# ENERGIS_Rack-PDU_1_0_1.net
KiCad netlist of a schematic drawn in EAGLE
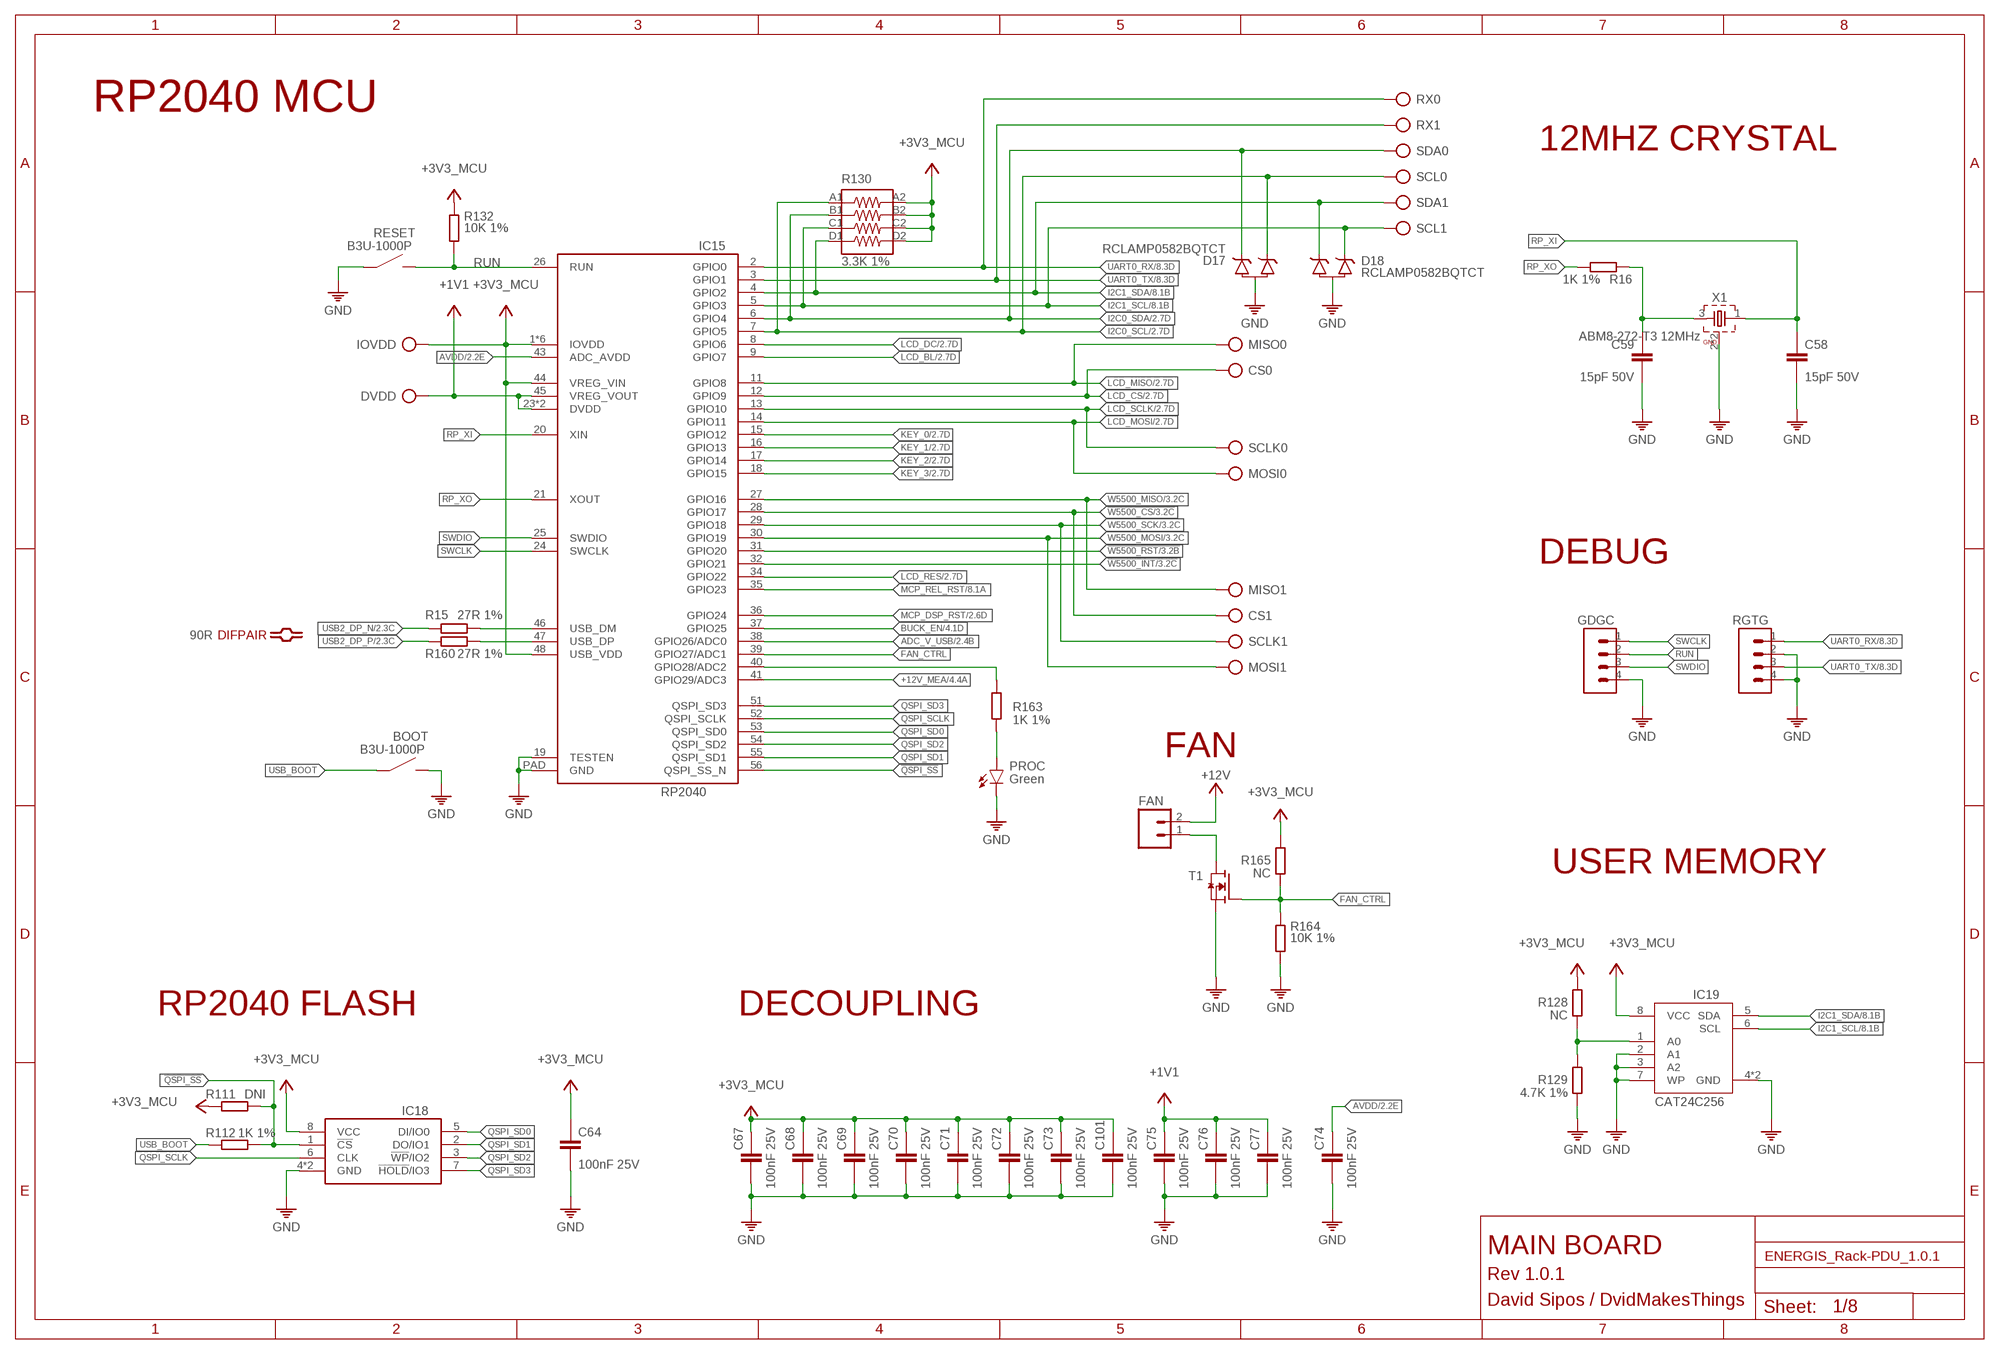
[diagram p0: schematic, sheet 1]
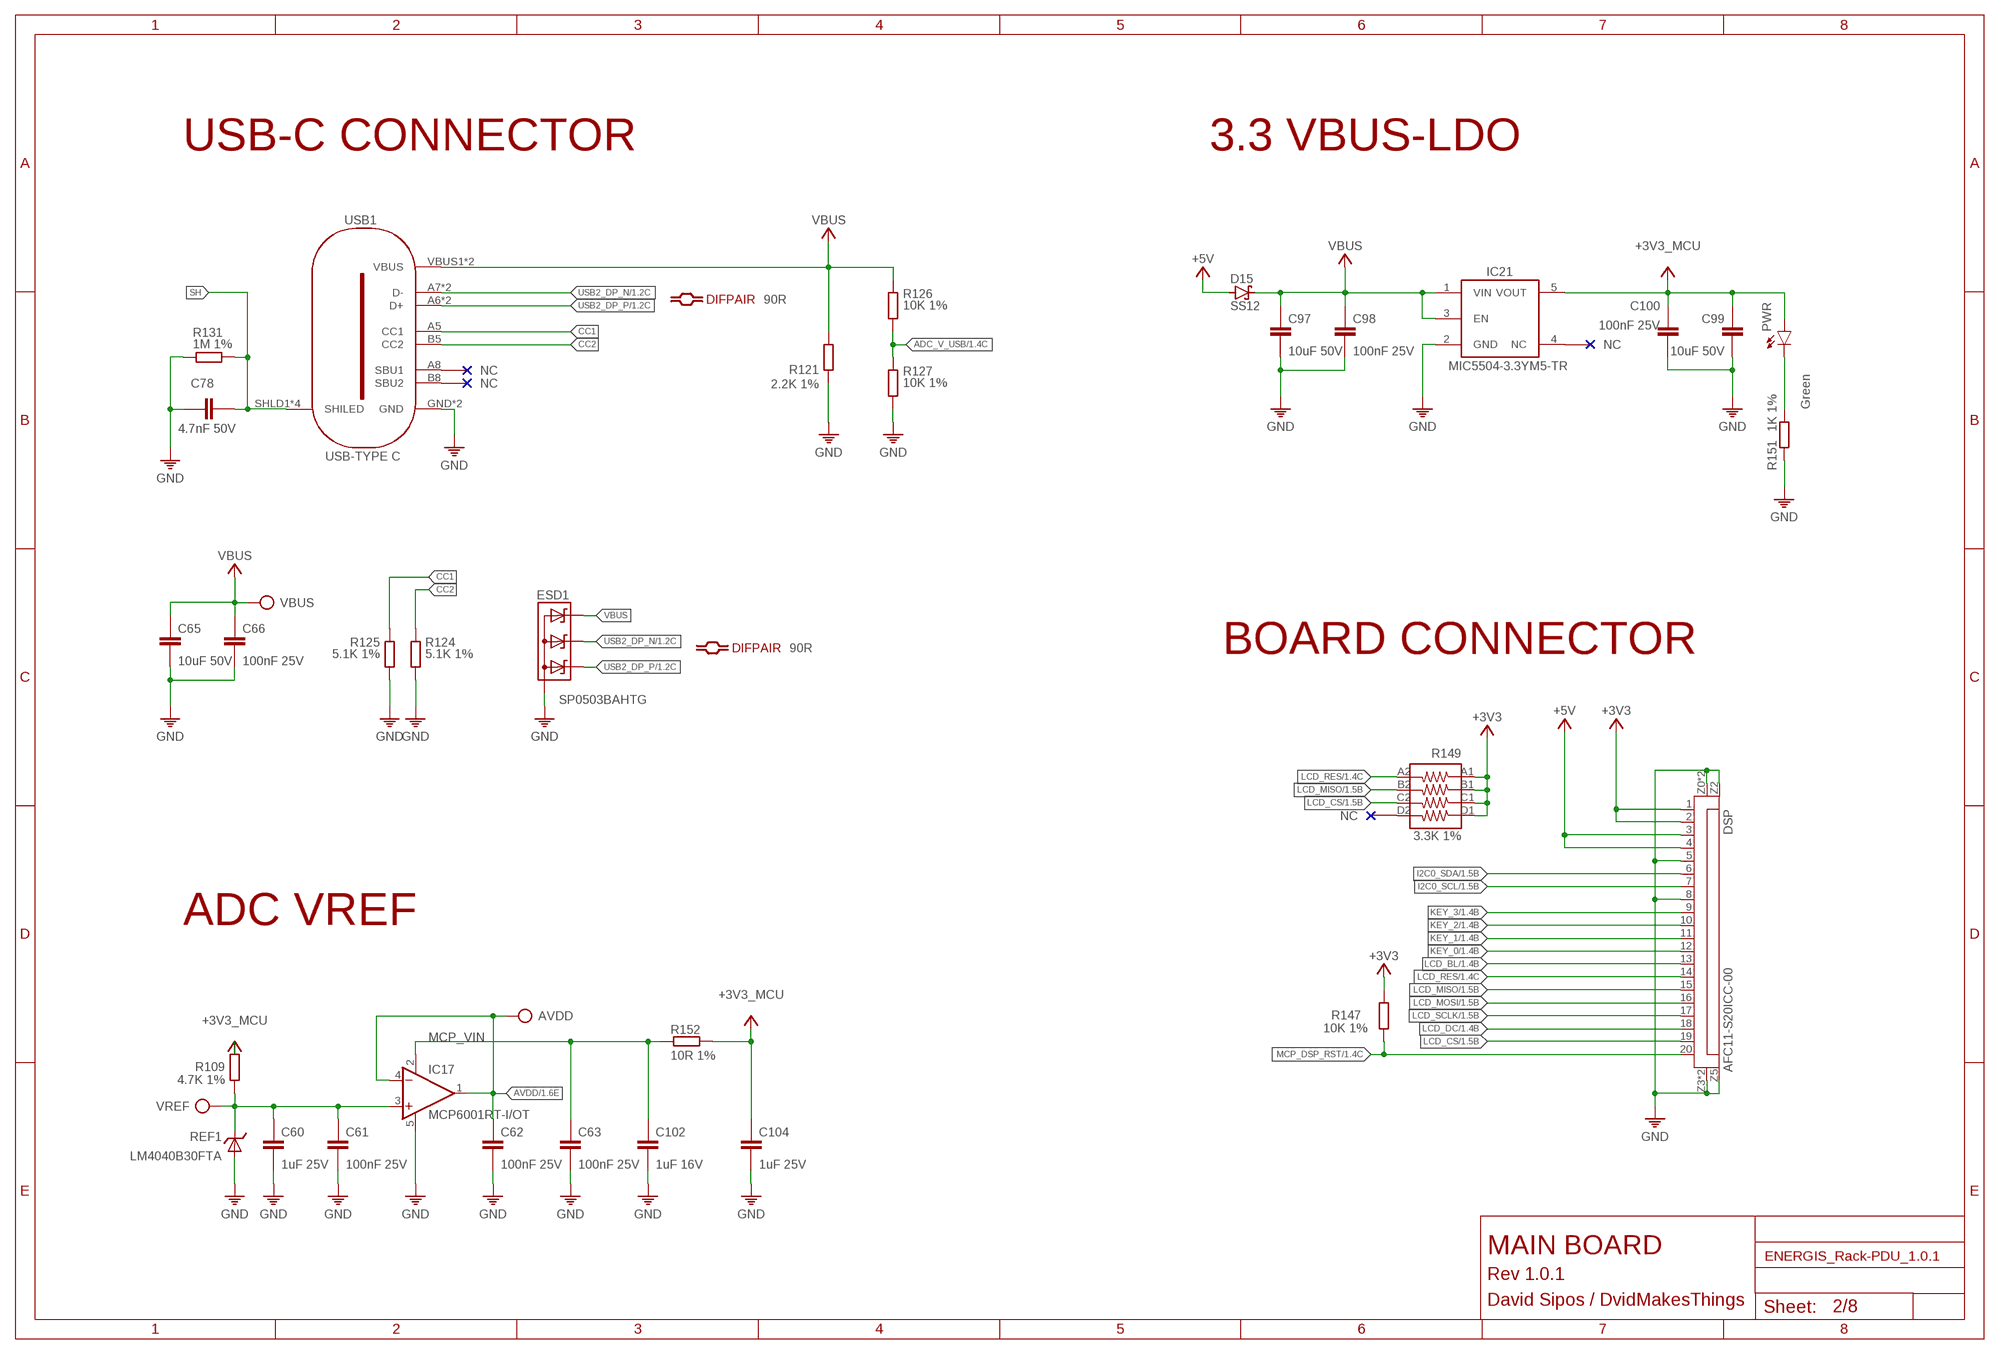
[diagram p1: schematic, sheet 2]
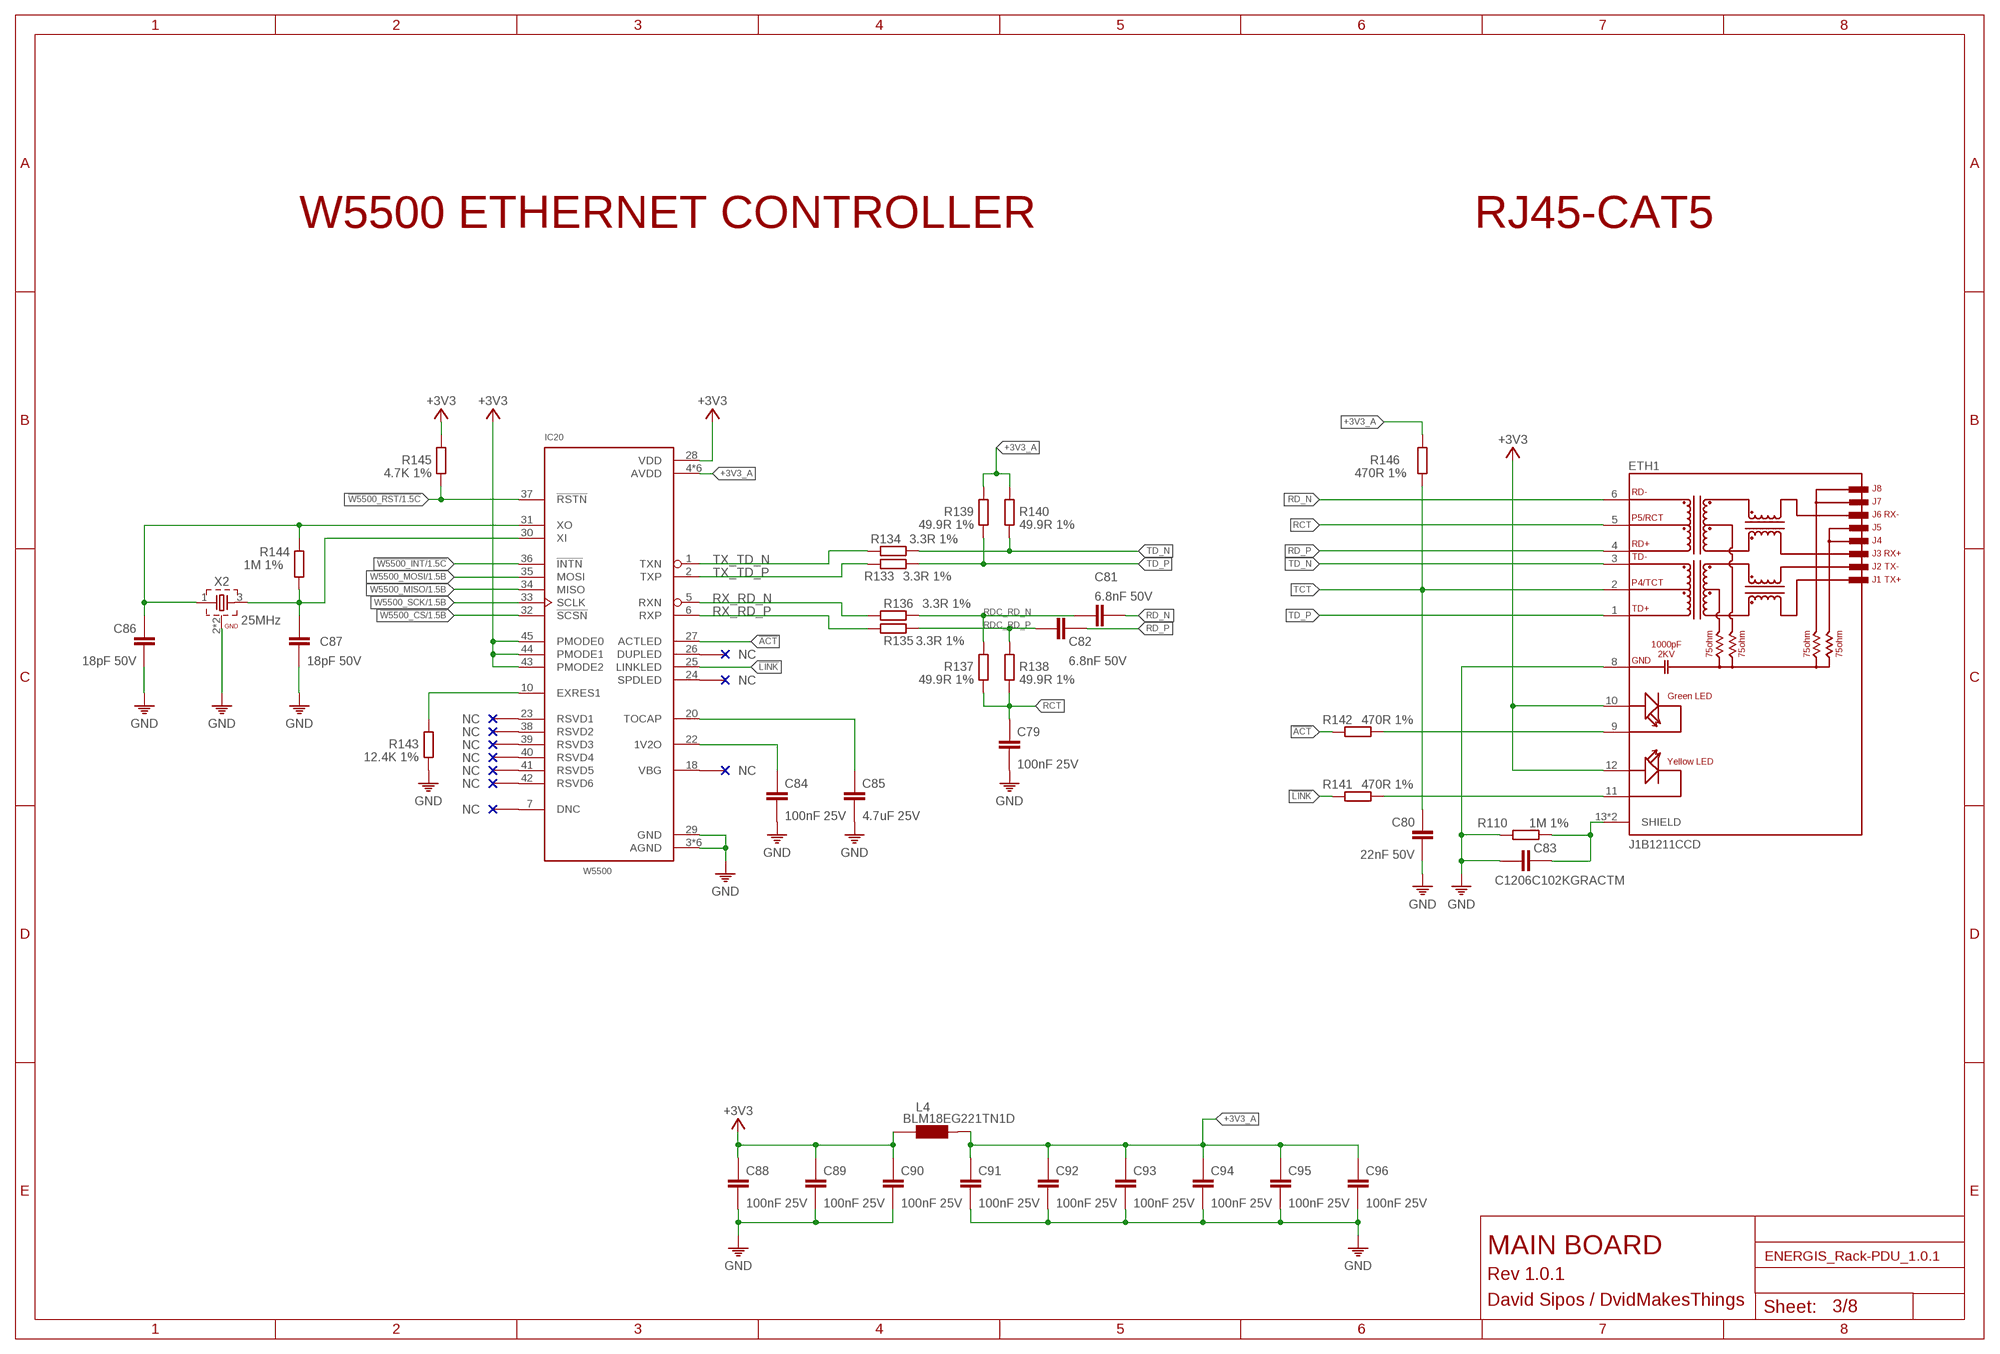
[diagram p2: schematic, sheet 3]
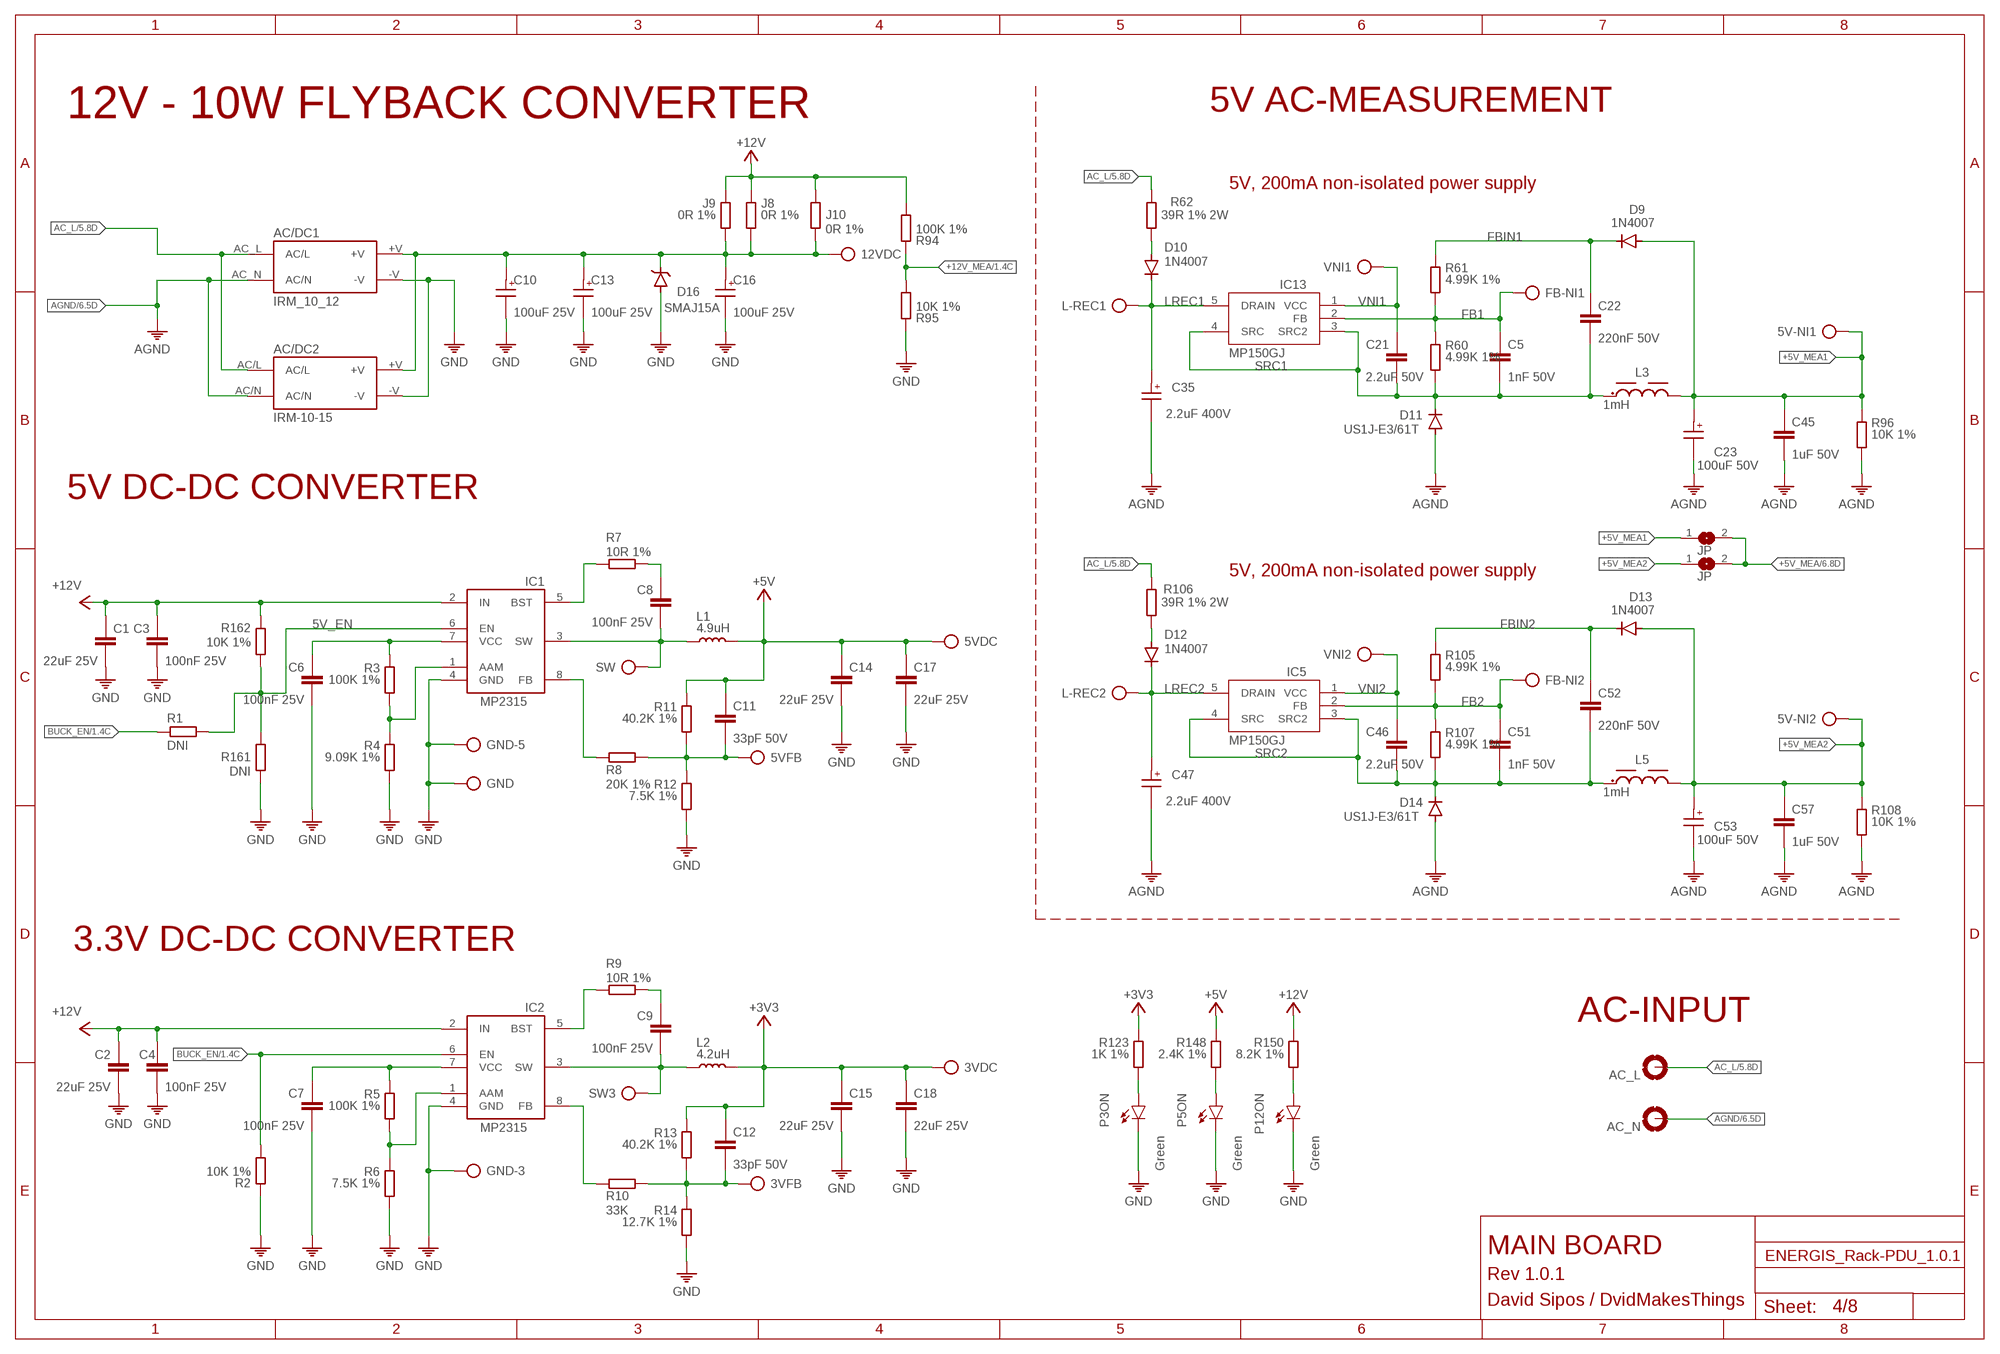
[diagram p3: schematic, sheet 4]
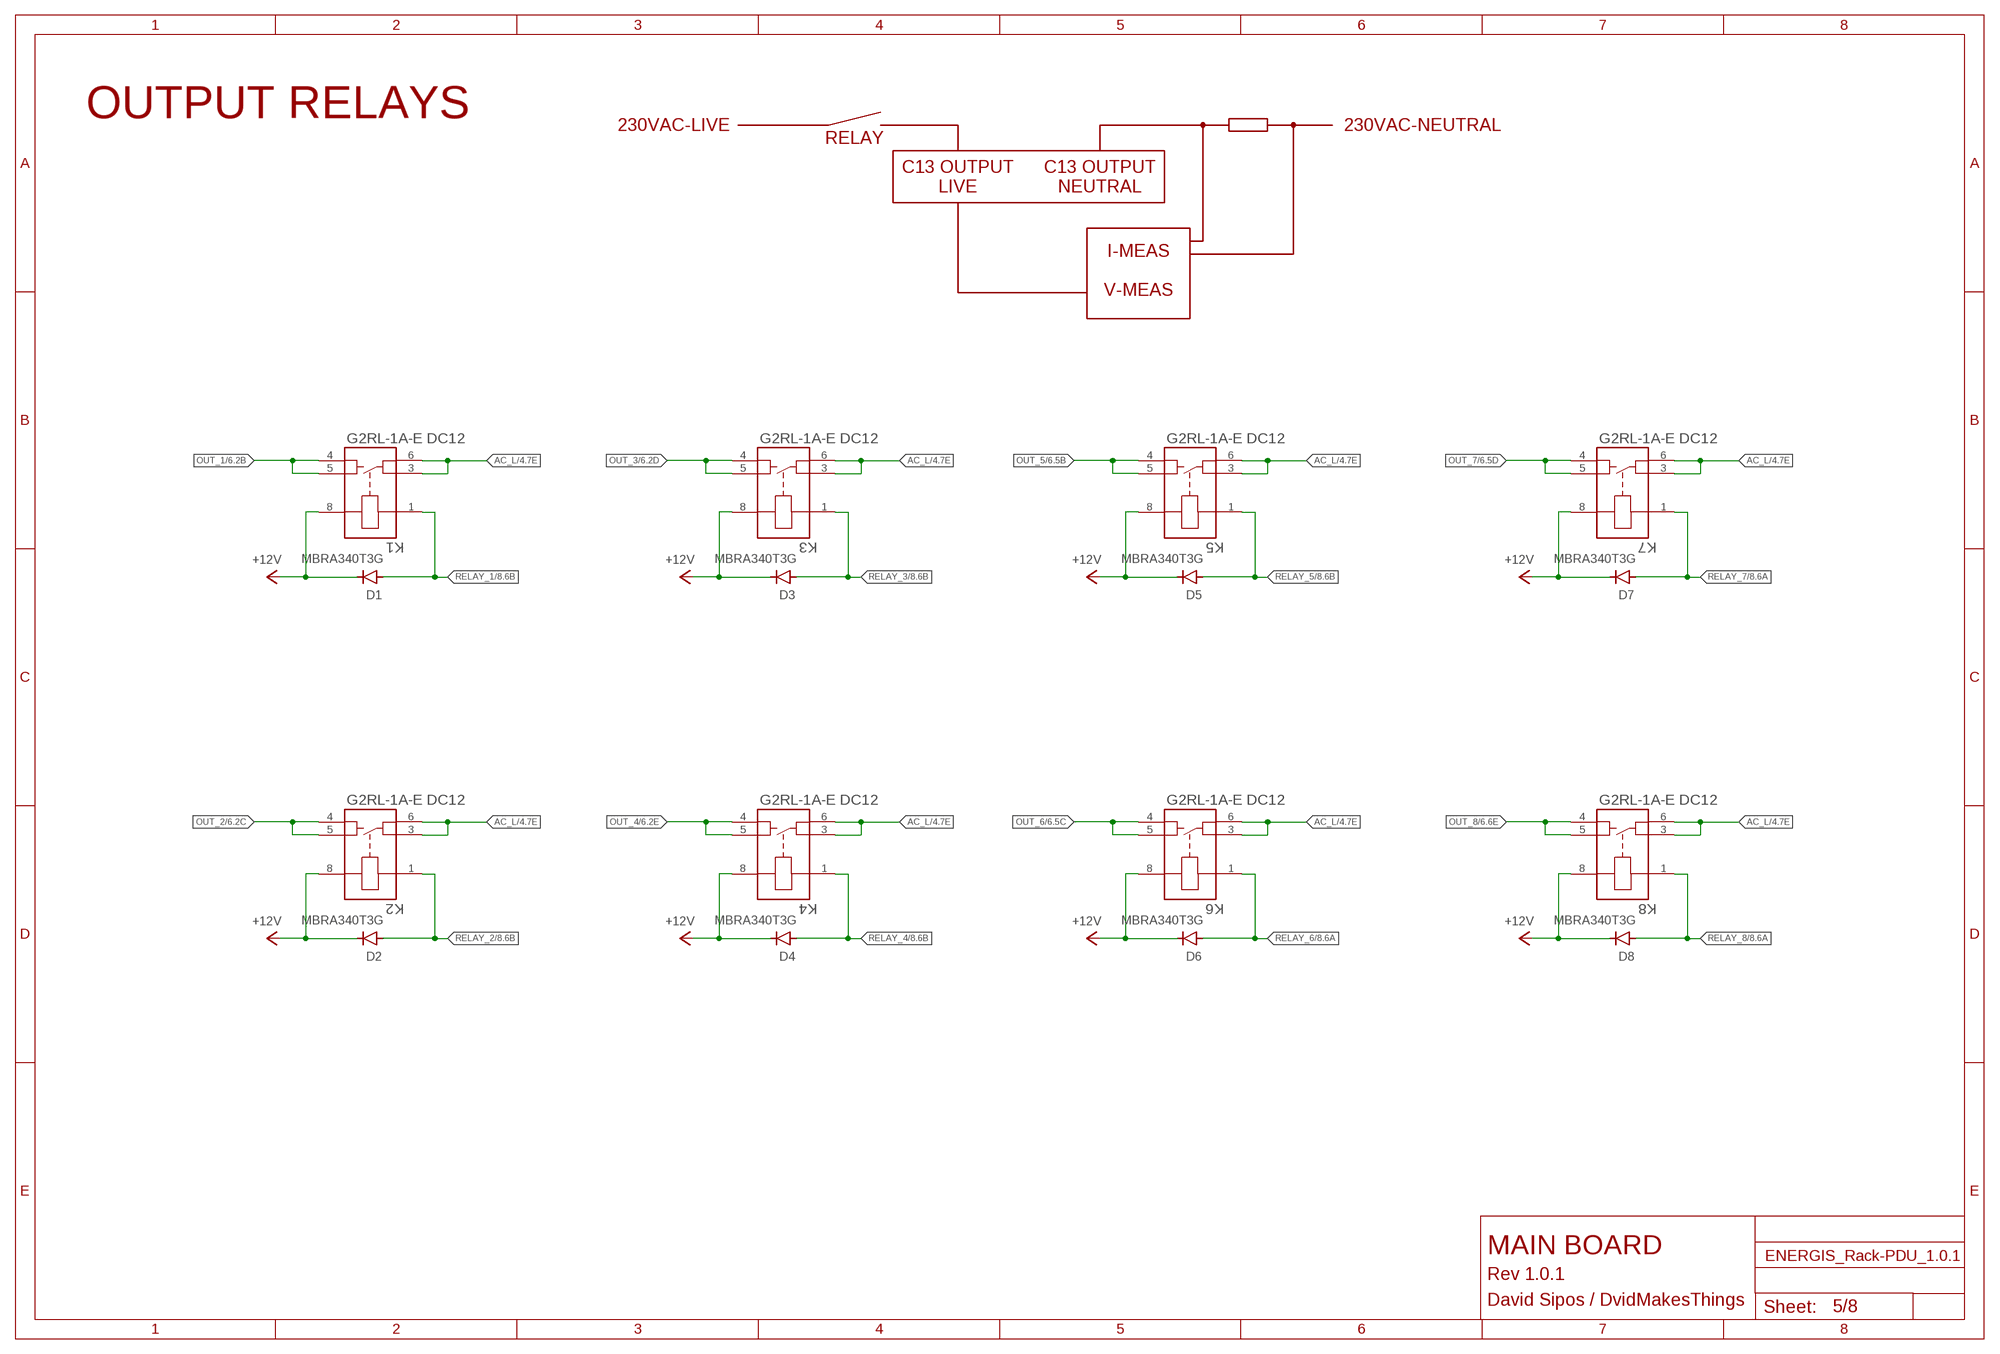
[diagram p4: schematic, sheet 5]
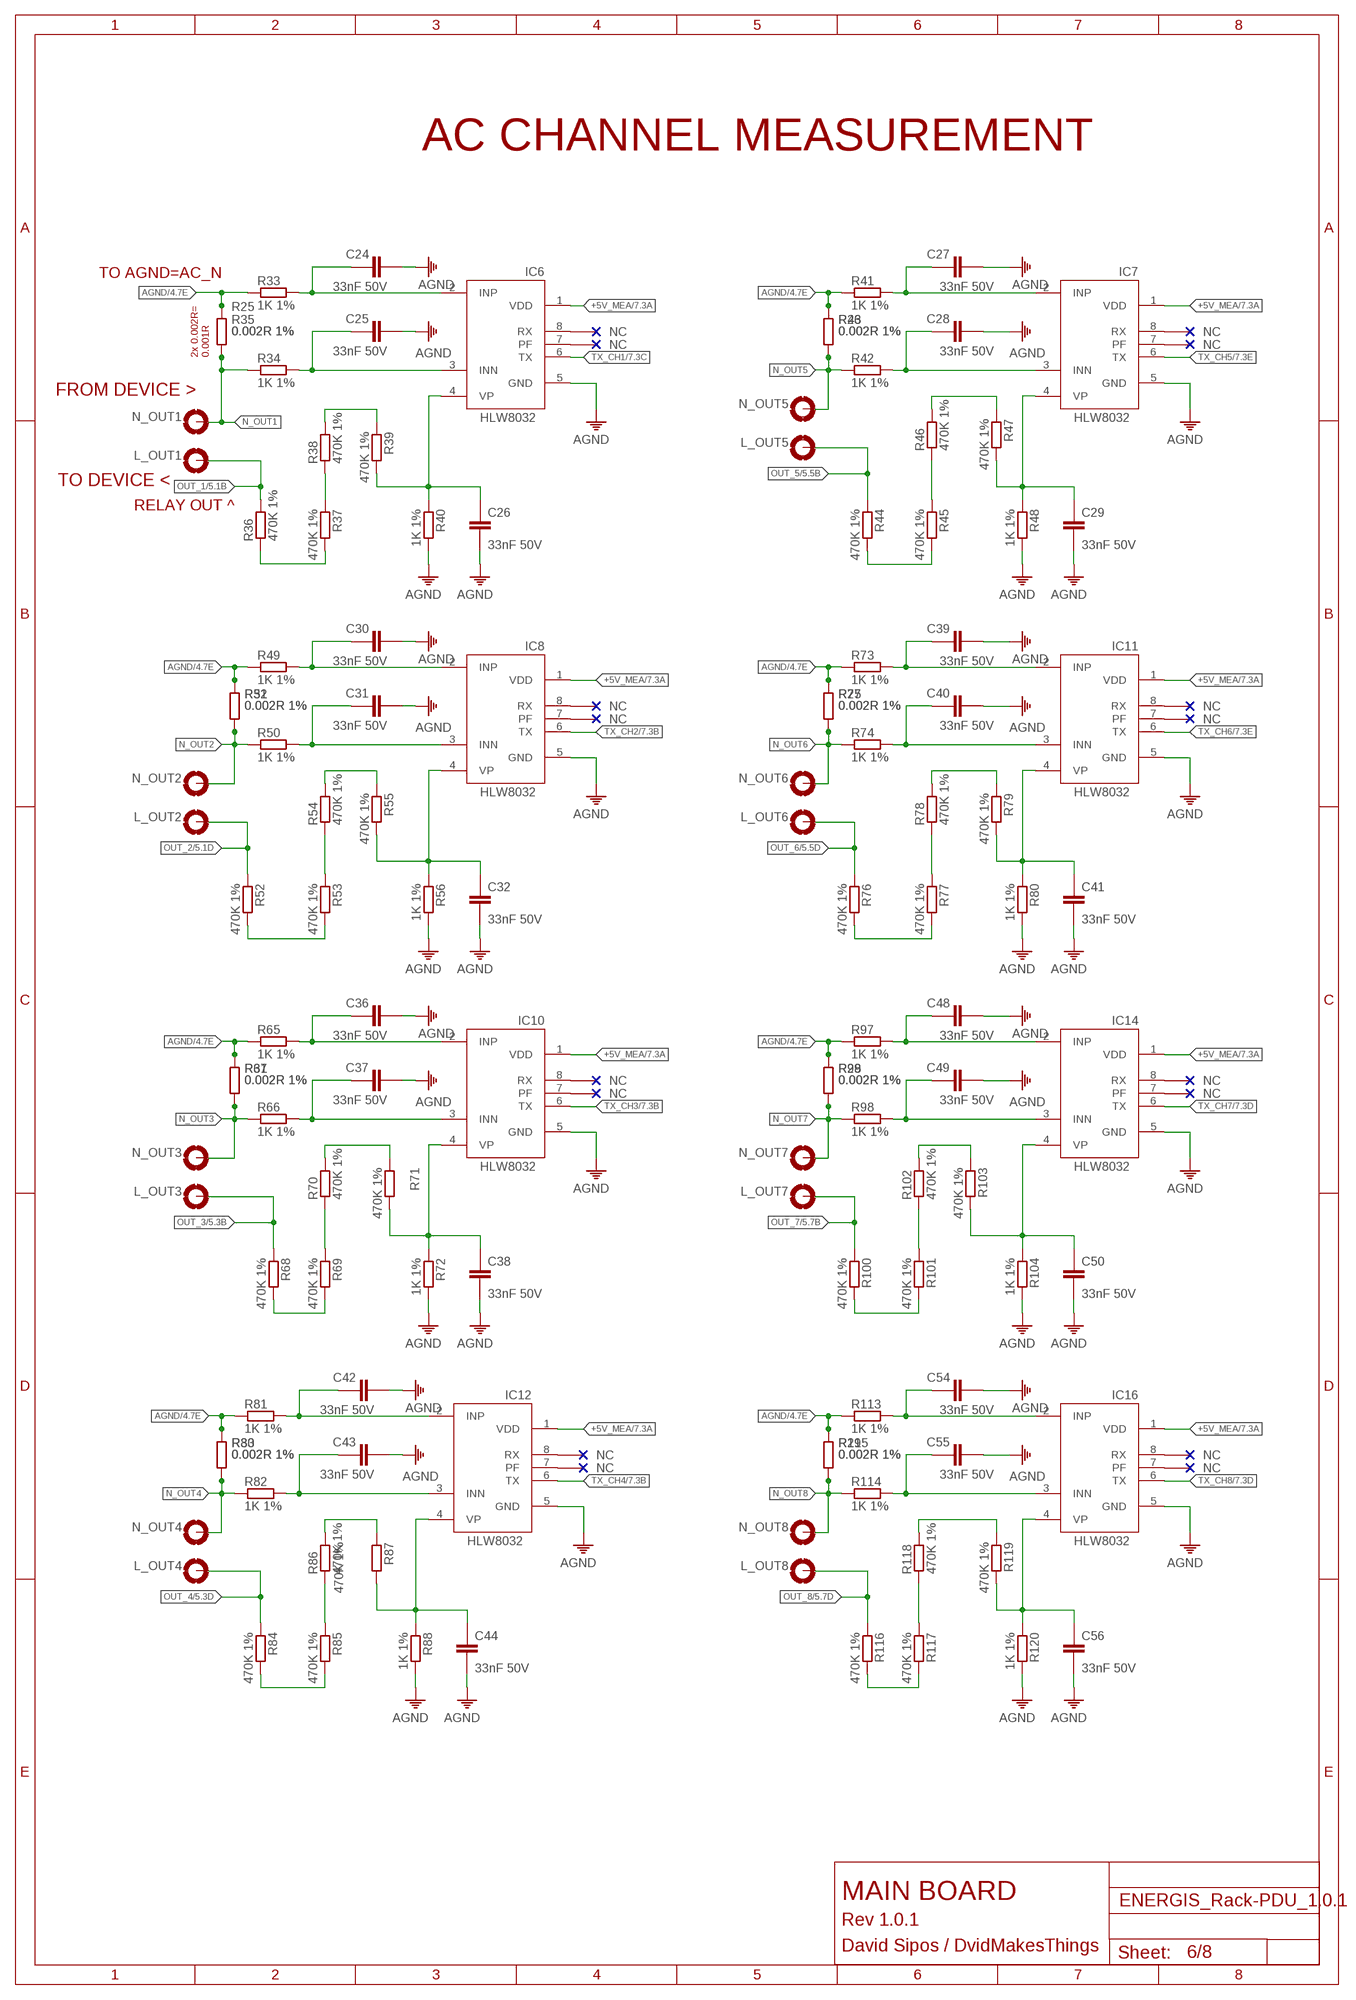
[diagram p5: schematic, sheet 6]
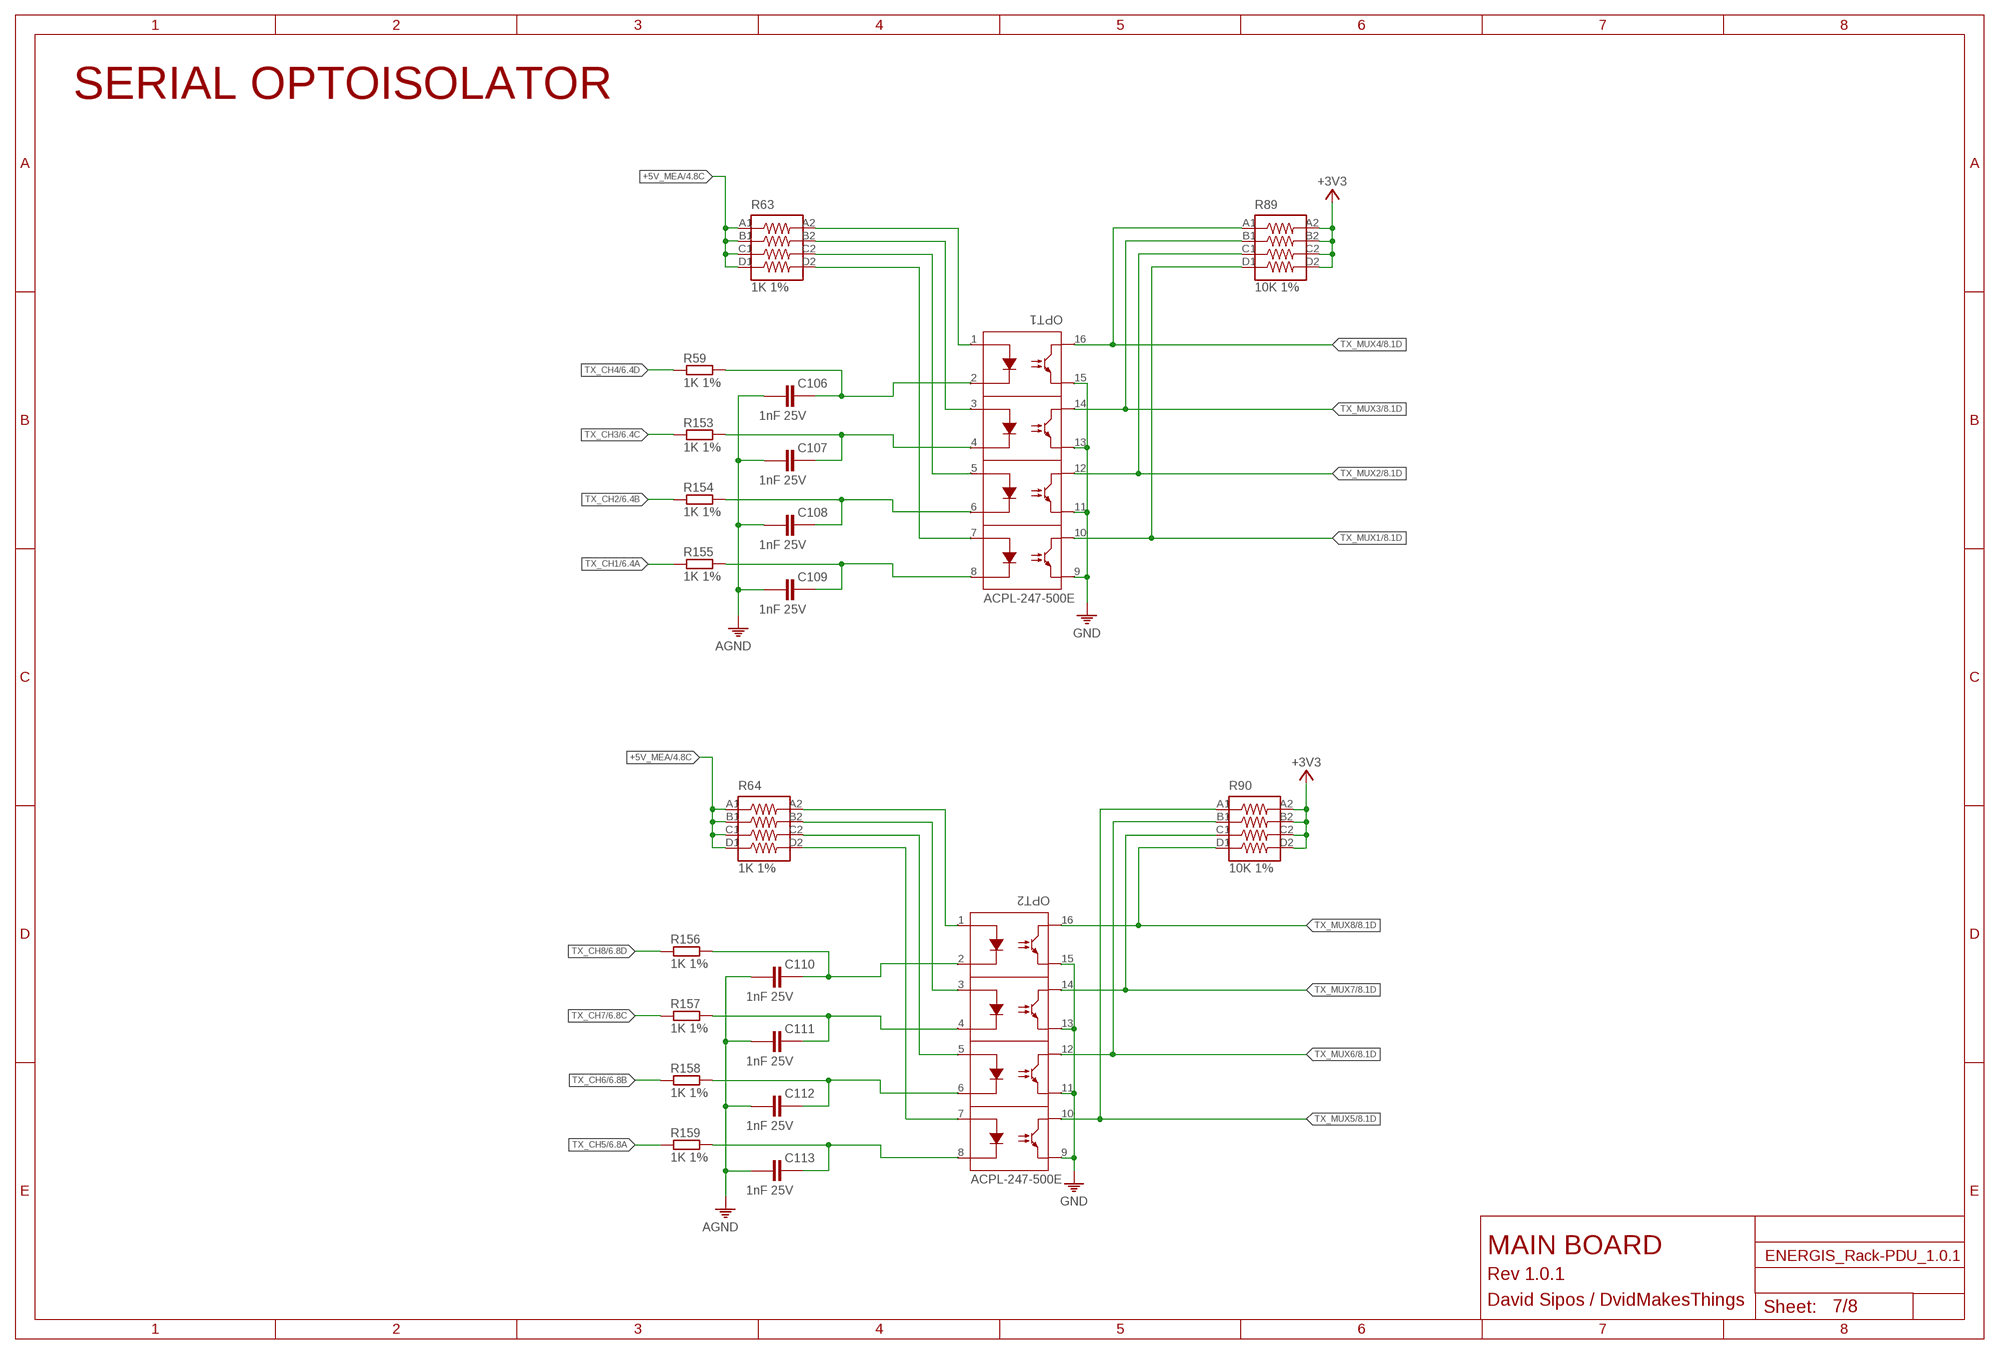
[diagram p6: schematic, sheet 7]
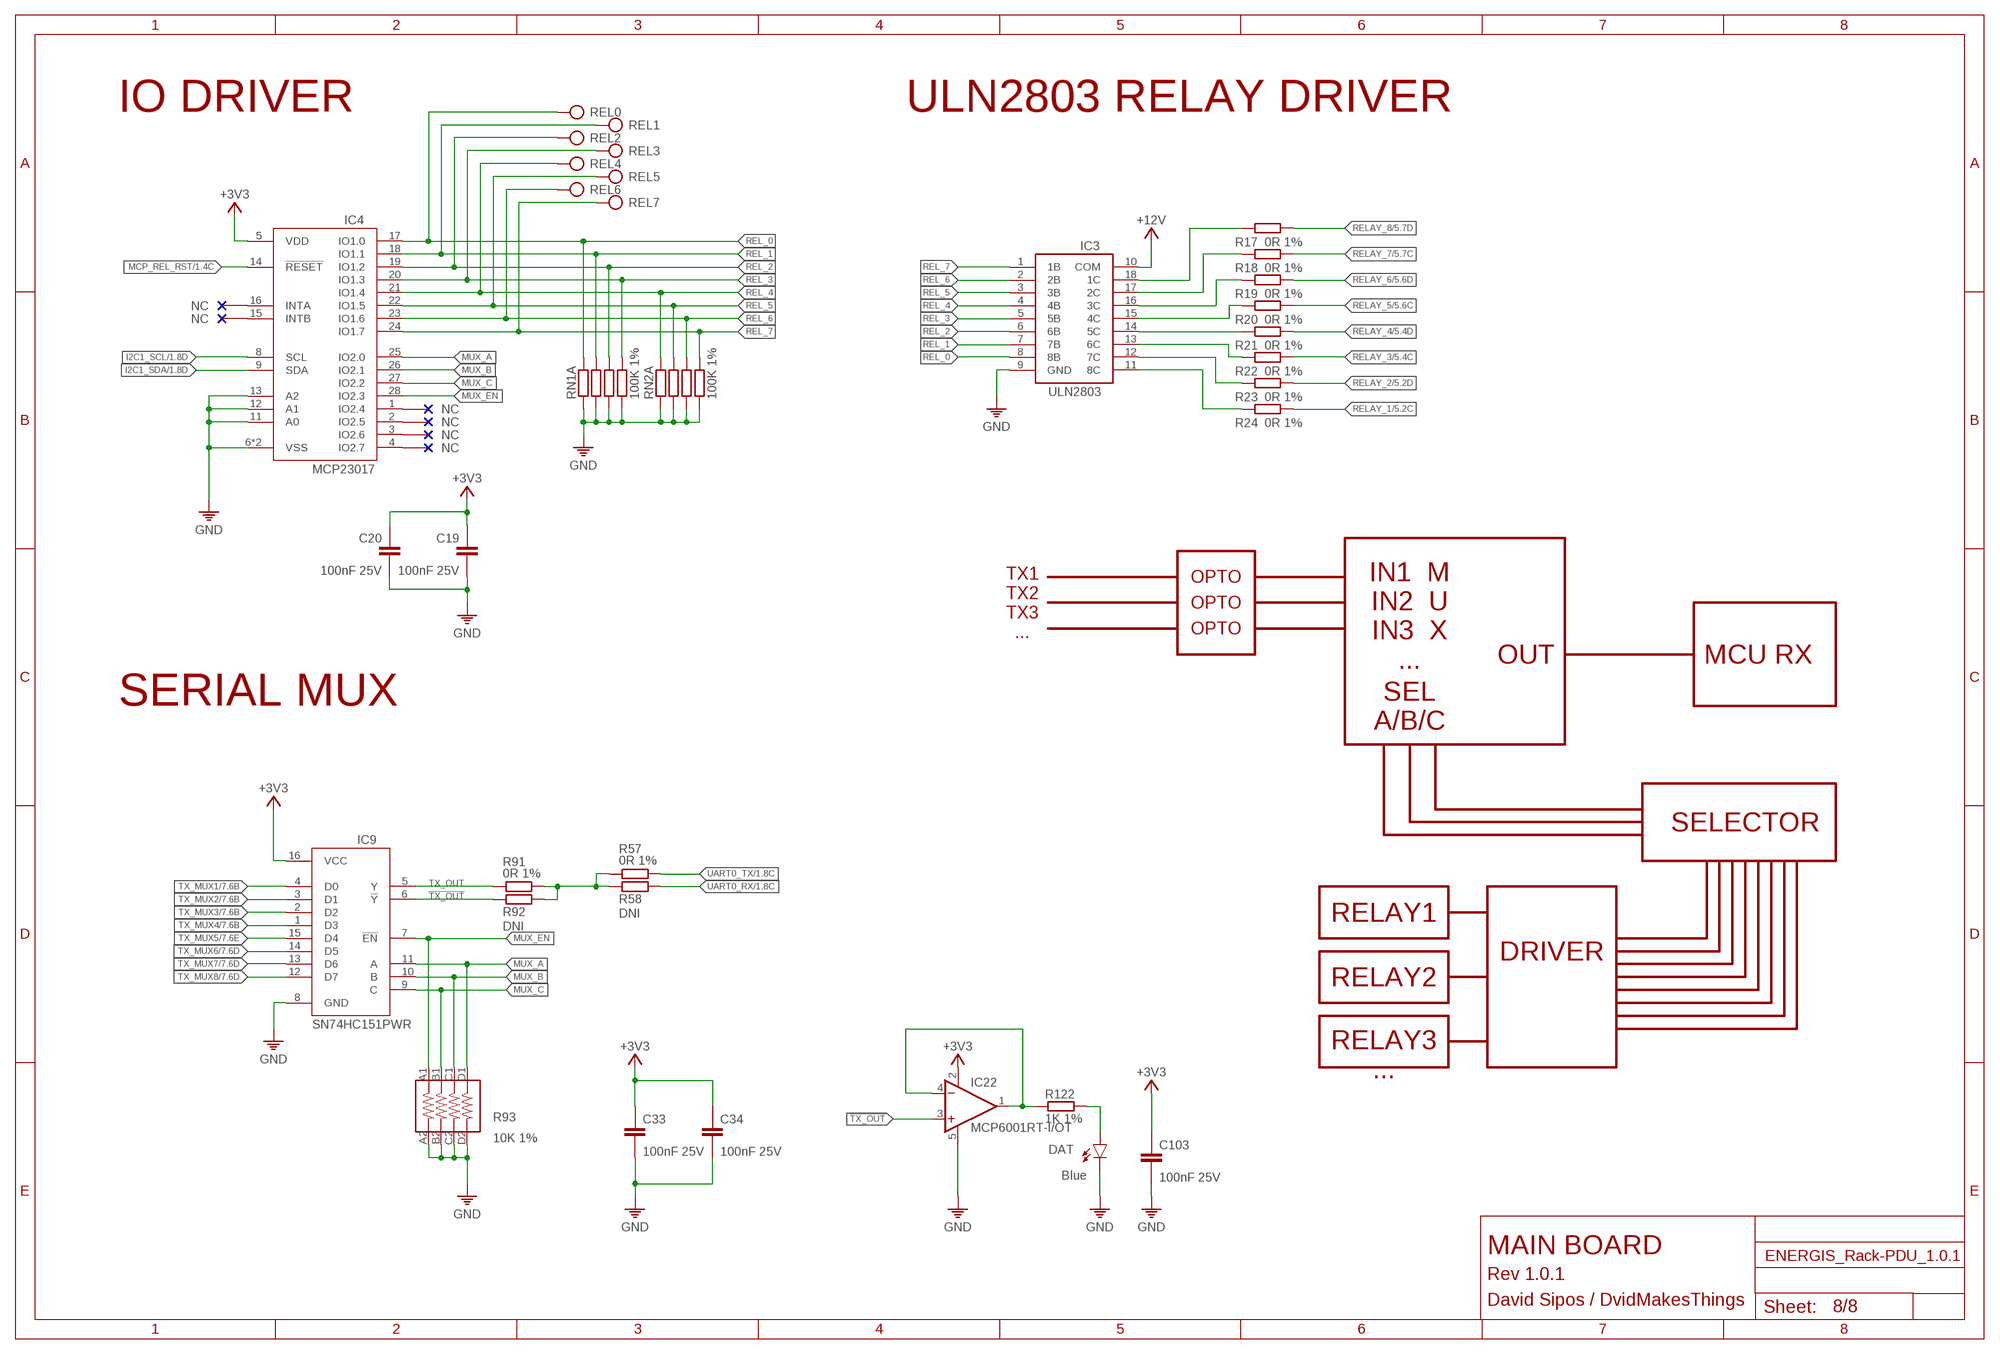
[diagram p7: schematic, sheet 8]

(export (version "E")
  (design (tool "Eeschema 10.0.6"))
  (components
    (comp (ref "BOOT")
      (value "B3U-1000P")
      (footprint "eagle-import:B3U-1000P")
      (fields (field (name "LCSC_PART") "C231329"))
      (libsource (lib "eagle-import") (part "B3U-1000P"))
    )
    (comp (ref "C58")
      (value "15pF 50V")
      (footprint "eagle-import:0201")
      (fields (field (name "LCSC_PART") "C22374851"))
      (libsource (lib "eagle-import") (part "15PF-50V0201"))
    )
    (comp (ref "C59")
      (value "15pF 50V")
      (footprint "eagle-import:0201")
      (fields (field (name "LCSC_PART") "C22374851"))
      (libsource (lib "eagle-import") (part "15PF-50V0201"))
    )
    (comp (ref "C64")
      (value "100nF 25V")
      (footprint "eagle-import:0201")
      (fields (field (name "LCSC_PART") "C76939"))
      (libsource (lib "eagle-import") (part "100NF-25V-0201"))
    )
    (comp (ref "C67")
      (value "100nF 25V")
      (footprint "eagle-import:0201")
      (fields (field (name "LCSC_PART") "C76939"))
      (libsource (lib "eagle-import") (part "100NF-25V-0201"))
    )
    (comp (ref "C68")
      (value "100nF 25V")
      (footprint "eagle-import:0201")
      (fields (field (name "LCSC_PART") "C76939"))
      (libsource (lib "eagle-import") (part "100NF-25V-0201"))
    )
    (comp (ref "C69")
      (value "100nF 25V")
      (footprint "eagle-import:0201")
      (fields (field (name "LCSC_PART") "C76939"))
      (libsource (lib "eagle-import") (part "100NF-25V-0201"))
    )
    (comp (ref "C70")
      (value "100nF 25V")
      (footprint "eagle-import:0201")
      (fields (field (name "LCSC_PART") "C76939"))
      (libsource (lib "eagle-import") (part "100NF-25V-0201"))
    )
    (comp (ref "C71")
      (value "100nF 25V")
      (footprint "eagle-import:0201")
      (fields (field (name "LCSC_PART") "C76939"))
      (libsource (lib "eagle-import") (part "100NF-25V-0201"))
    )
    (comp (ref "C72")
      (value "100nF 25V")
      (footprint "eagle-import:0201")
      (fields (field (name "LCSC_PART") "C76939"))
      (libsource (lib "eagle-import") (part "100NF-25V-0201"))
    )
    (comp (ref "C73")
      (value "100nF 25V")
      (footprint "eagle-import:0201")
      (fields (field (name "LCSC_PART") "C76939"))
      (libsource (lib "eagle-import") (part "100NF-25V-0201"))
    )
    (comp (ref "C74")
      (value "100nF 25V")
      (footprint "eagle-import:0201")
      (fields (field (name "LCSC_PART") "C76939"))
      (libsource (lib "eagle-import") (part "100NF-25V-0201"))
    )
    (comp (ref "C75")
      (value "100nF 25V")
      (footprint "eagle-import:0201")
      (fields (field (name "LCSC_PART") "C76939"))
      (libsource (lib "eagle-import") (part "100NF-25V-0201"))
    )
    (comp (ref "C76")
      (value "100nF 25V")
      (footprint "eagle-import:0201")
      (fields (field (name "LCSC_PART") "C76939"))
      (libsource (lib "eagle-import") (part "100NF-25V-0201"))
    )
    (comp (ref "C77")
      (value "100nF 25V")
      (footprint "eagle-import:0201")
      (fields (field (name "LCSC_PART") "C76939"))
      (libsource (lib "eagle-import") (part "100NF-25V-0201"))
    )
    (comp (ref "C101")
      (value "100nF 25V")
      (footprint "eagle-import:0201")
      (fields (field (name "LCSC_PART") "C76939"))
      (libsource (lib "eagle-import") (part "100NF-25V-0201"))
    )
    (comp (ref "CS0") (value "TP") (footprint "eagle-import:TP") (libsource (lib "eagle-import") (part "TP")))
    (comp (ref "CS1") (value "TP") (footprint "eagle-import:TP") (libsource (lib "eagle-import") (part "TP")))
    (comp (ref "D17")
      (value "RCLAMP0582BQTCT")
      (footprint "eagle-import:SOT-523")
      (fields (field (name "LCSC_PART") "C841193"))
      (libsource (lib "eagle-import") (part "RCLAMP0582BQTCT"))
    )
    (comp (ref "D18")
      (value "RCLAMP0582BQTCT")
      (footprint "eagle-import:SOT-523")
      (fields (field (name "LCSC_PART") "C841193"))
      (libsource (lib "eagle-import") (part "RCLAMP0582BQTCT"))
    )
    (comp (ref "DVDD")
      (value "TP")
      (footprint "eagle-import:TP")
      (libsource (lib "eagle-import") (part "TP"))
    )
    (comp (ref "FAN")
      (value "M02")
      (footprint "eagle-import:02P")
      (libsource (lib "eagle-import") (part "M02"))
    )
    (comp (ref "GDGC")
      (value "CON-1X4")
      (footprint "eagle-import:1X4")
      (libsource (lib "eagle-import") (part "CON-1X4"))
    )
    (comp (ref "IC15")
      (value "RP2040")
      (footprint "eagle-import:QFN56")
      (fields (field (name "LCSC_PART") "C2040"))
      (libsource (lib "eagle-import") (part "RP2040"))
    )
    (comp (ref "IC18")
      (value "W25Q128JVPIQ")
      (footprint "eagle-import:SON127P600X500X75-8N")
      (fields (field (name "LCSC_PART") "C190862"))
      (libsource (lib "eagle-import") (part "W25Q128JVP"))
    )
    (comp (ref "IC19")
      (value "CAT24C256HU4IGT3")
      (footprint "eagle-import:SON50P300X200X50-9T130X140N")
      (fields (field (name "LCSC_PART") "C233771"))
      (libsource (lib "eagle-import") (part "CAT24C256-HU4"))
    )
    (comp (ref "IOVDD")
      (value "TP")
      (footprint "eagle-import:TP")
      (libsource (lib "eagle-import") (part "TP"))
    )
    (comp (ref "MISO0")
      (value "TP")
      (footprint "eagle-import:TP")
      (libsource (lib "eagle-import") (part "TP"))
    )
    (comp (ref "MISO1")
      (value "TP")
      (footprint "eagle-import:TP")
      (libsource (lib "eagle-import") (part "TP"))
    )
    (comp (ref "MOSI0")
      (value "TP")
      (footprint "eagle-import:TP")
      (libsource (lib "eagle-import") (part "TP"))
    )
    (comp (ref "MOSI1")
      (value "TP")
      (footprint "eagle-import:TP")
      (libsource (lib "eagle-import") (part "TP"))
    )
    (comp (ref "PROC")
      (value "Green")
      (footprint "eagle-import:LED-0603")
      (fields (field (name "LCSC_PART") "C965804"))
      (libsource (lib "eagle-import") (part "LED-GREENLED-0603"))
    )
    (comp (ref "R15")
      (value "27R 1%")
      (footprint "eagle-import:0201")
      (fields (field (name "LCSC_PART") "C473051"))
      (libsource (lib "eagle-import") (part "27R-1%0201"))
    )
    (comp (ref "R16")
      (value "1K 1%")
      (footprint "eagle-import:0201")
      (fields (field (name "LCSC_PART") "C270365"))
      (libsource (lib "eagle-import") (part "1K-1%0201"))
    )
    (comp (ref "R111")
      (value "DNI")
      (footprint "eagle-import:R0201")
      (libsource (lib "eagle-import") (part "R0201"))
    )
    (comp (ref "R112")
      (value "1K 1%")
      (footprint "eagle-import:0402")
      (fields (field (name "LCSC_PART") "C11702"))
      (libsource (lib "eagle-import") (part "1K-1%0402"))
    )
    (comp (ref "R128")
      (value "NC")
      (footprint "eagle-import:R0201")
      (libsource (lib "eagle-import") (part "R0201"))
    )
    (comp (ref "R129")
      (value "4.7K 1%")
      (footprint "eagle-import:0201")
      (fields (field (name "LCSC_PART") "C270346"))
      (libsource (lib "eagle-import") (part "4.7K-1%0201"))
    )
    (comp (ref "R130")
      (value "3.3K 1%")
      (footprint "eagle-import:_0603X4-1206")
      (fields (field (name "LCSC_PART") "C1734380"))
      (libsource (lib "eagle-import") (part "3.3K-1%_ARRAY0603X4-1206"))
    )
    (comp (ref "R132")
      (value "10K 1%")
      (footprint "eagle-import:0402")
      (fields (field (name "LCSC_PART") "C25744"))
      (libsource (lib "eagle-import") (part "10K-1%0402"))
    )
    (comp (ref "R160")
      (value "27R 1%")
      (footprint "eagle-import:0201")
      (fields (field (name "LCSC_PART") "C473051"))
      (libsource (lib "eagle-import") (part "27R-1%0201"))
    )
    (comp (ref "R163")
      (value "1K 1%")
      (footprint "eagle-import:0402")
      (fields (field (name "LCSC_PART") "C11702"))
      (libsource (lib "eagle-import") (part "1K-1%0402"))
    )
    (comp (ref "R164")
      (value "10K 1%")
      (footprint "eagle-import:0402")
      (fields (field (name "LCSC_PART") "C25744"))
      (libsource (lib "eagle-import") (part "10K-1%0402"))
    )
    (comp (ref "R165")
      (value "NC")
      (footprint "eagle-import:R0201")
      (libsource (lib "eagle-import") (part "R0201"))
    )
    (comp (ref "RESET")
      (value "B3U-1000P")
      (footprint "eagle-import:B3U-1000P")
      (fields (field (name "LCSC_PART") "C231329"))
      (libsource (lib "eagle-import") (part "B3U-1000P"))
    )
    (comp (ref "RGTG")
      (value "CON-1X4")
      (footprint "eagle-import:1X4")
      (libsource (lib "eagle-import") (part "CON-1X4"))
    )
    (comp (ref "RX0") (value "TP") (footprint "eagle-import:TP") (libsource (lib "eagle-import") (part "TP")))
    (comp (ref "RX1") (value "TP") (footprint "eagle-import:TP") (libsource (lib "eagle-import") (part "TP")))
    (comp (ref "SCL0")
      (value "TP")
      (footprint "eagle-import:TP")
      (libsource (lib "eagle-import") (part "TP"))
    )
    (comp (ref "SCL1")
      (value "TP")
      (footprint "eagle-import:TP")
      (libsource (lib "eagle-import") (part "TP"))
    )
    (comp (ref "SCLK0")
      (value "TP")
      (footprint "eagle-import:TP")
      (libsource (lib "eagle-import") (part "TP"))
    )
    (comp (ref "SCLK1")
      (value "TP")
      (footprint "eagle-import:TP")
      (libsource (lib "eagle-import") (part "TP"))
    )
    (comp (ref "SDA0")
      (value "TP")
      (footprint "eagle-import:TP")
      (libsource (lib "eagle-import") (part "TP"))
    )
    (comp (ref "SDA1")
      (value "TP")
      (footprint "eagle-import:TP")
      (libsource (lib "eagle-import") (part "TP"))
    )
    (comp (ref "T1")
      (value "BSS138")
      (footprint "eagle-import:SOT23")
      (libsource (lib "eagle-import") (part "BSS138"))
    )
    (comp (ref "X1")
      (value "ABM8-272-T3 12MHz")
      (footprint "eagle-import:WE-XTAL_CFPX-180")
      (fields (field (name "LCSC_PART") "C20625731"))
      (libsource (lib "eagle-import") (part "CRYSTAL-3225X322512MSB4SI"))
    )
    (comp (ref "C106")
      (value "1nF 25V")
      (footprint "eagle-import:0201")
      (fields (field (name "LCSC_PART") "C7694325V"))
      (libsource (lib "eagle-import") (part "1NF-25V-0201"))
    )
    (comp (ref "C107")
      (value "1nF 25V")
      (footprint "eagle-import:0201")
      (fields (field (name "LCSC_PART") "C7694325V"))
      (libsource (lib "eagle-import") (part "1NF-25V-0201"))
    )
    (comp (ref "C108")
      (value "1nF 25V")
      (footprint "eagle-import:0201")
      (fields (field (name "LCSC_PART") "C7694325V"))
      (libsource (lib "eagle-import") (part "1NF-25V-0201"))
    )
    (comp (ref "C109")
      (value "1nF 25V")
      (footprint "eagle-import:0201")
      (fields (field (name "LCSC_PART") "C7694325V"))
      (libsource (lib "eagle-import") (part "1NF-25V-0201"))
    )
    (comp (ref "C110")
      (value "1nF 25V")
      (footprint "eagle-import:0201")
      (fields (field (name "LCSC_PART") "C7694325V"))
      (libsource (lib "eagle-import") (part "1NF-25V-0201"))
    )
    (comp (ref "C111")
      (value "1nF 25V")
      (footprint "eagle-import:0201")
      (fields (field (name "LCSC_PART") "C7694325V"))
      (libsource (lib "eagle-import") (part "1NF-25V-0201"))
    )
    (comp (ref "C112")
      (value "1nF 25V")
      (footprint "eagle-import:0201")
      (fields (field (name "LCSC_PART") "C7694325V"))
      (libsource (lib "eagle-import") (part "1NF-25V-0201"))
    )
    (comp (ref "C113")
      (value "1nF 25V")
      (footprint "eagle-import:0201")
      (fields (field (name "LCSC_PART") "C7694325V"))
      (libsource (lib "eagle-import") (part "1NF-25V-0201"))
    )
    (comp (ref "OPT1")
      (value "ACPL-247-500E")
      (footprint "eagle-import:SO16")
      (fields (field (name "LCSC_PART") "C188681"))
      (libsource (lib "eagle-import") (part "ACPL-2471"))
    )
    (comp (ref "OPT2")
      (value "ACPL-247-500E")
      (footprint "eagle-import:SO16")
      (fields (field (name "LCSC_PART") "C188681"))
      (libsource (lib "eagle-import") (part "ACPL-2471"))
    )
    (comp (ref "R59")
      (value "1K 1%")
      (footprint "eagle-import:0201")
      (fields (field (name "LCSC_PART") "C270365"))
      (libsource (lib "eagle-import") (part "1K-1%0201"))
    )
    (comp (ref "R63")
      (value "1K 1%")
      (footprint "eagle-import:_0603X4-1206")
      (fields (field (name "LCSC_PART") "C110021"))
      (libsource (lib "eagle-import") (part "1K-1%_ARRAY0603X4-1206"))
    )
    (comp (ref "R64")
      (value "1K 1%")
      (footprint "eagle-import:_0603X4-1206")
      (fields (field (name "LCSC_PART") "C110021"))
      (libsource (lib "eagle-import") (part "1K-1%_ARRAY0603X4-1206"))
    )
    (comp (ref "R89")
      (value "10K 1%")
      (footprint "eagle-import:_0603X4-1206")
      (fields (field (name "LCSC_PART") "C110924"))
      (libsource (lib "eagle-import") (part "10K-1%_ARRAY0603X4-1206"))
    )
    (comp (ref "R90")
      (value "10K 1%")
      (footprint "eagle-import:_0603X4-1206")
      (fields (field (name "LCSC_PART") "C110924"))
      (libsource (lib "eagle-import") (part "10K-1%_ARRAY0603X4-1206"))
    )
    (comp (ref "R153")
      (value "1K 1%")
      (footprint "eagle-import:0201")
      (fields (field (name "LCSC_PART") "C270365"))
      (libsource (lib "eagle-import") (part "1K-1%0201"))
    )
    (comp (ref "R154")
      (value "1K 1%")
      (footprint "eagle-import:0201")
      (fields (field (name "LCSC_PART") "C270365"))
      (libsource (lib "eagle-import") (part "1K-1%0201"))
    )
    (comp (ref "R155")
      (value "1K 1%")
      (footprint "eagle-import:0201")
      (fields (field (name "LCSC_PART") "C270365"))
      (libsource (lib "eagle-import") (part "1K-1%0201"))
    )
    (comp (ref "R156")
      (value "1K 1%")
      (footprint "eagle-import:0201")
      (fields (field (name "LCSC_PART") "C270365"))
      (libsource (lib "eagle-import") (part "1K-1%0201"))
    )
    (comp (ref "R157")
      (value "1K 1%")
      (footprint "eagle-import:0201")
      (fields (field (name "LCSC_PART") "C270365"))
      (libsource (lib "eagle-import") (part "1K-1%0201"))
    )
    (comp (ref "R158")
      (value "1K 1%")
      (footprint "eagle-import:0201")
      (fields (field (name "LCSC_PART") "C270365"))
      (libsource (lib "eagle-import") (part "1K-1%0201"))
    )
    (comp (ref "R159")
      (value "1K 1%")
      (footprint "eagle-import:0201")
      (fields (field (name "LCSC_PART") "C270365"))
      (libsource (lib "eagle-import") (part "1K-1%0201"))
    )
    (comp (ref "C79")
      (value "100nF 25V")
      (footprint "eagle-import:0402")
      (fields (field (name "LCSC_PART") "C56392"))
      (libsource (lib "eagle-import") (part "100NF-25V-0402"))
    )
    (comp (ref "C80")
      (value "22nF 50V")
      (footprint "eagle-import:0402")
      (fields (field (name "LCSC_PART") "C1532"))
      (libsource (lib "eagle-import") (part "22NF-50V0402"))
    )
    (comp (ref "C81")
      (value "6.8nF 50V")
      (footprint "eagle-import:0201")
      (fields (field (name "LCSC_PART") "C285015"))
      (libsource (lib "eagle-import") (part "6.8NF-50V0201"))
    )
    (comp (ref "C82")
      (value "6.8nF 50V")
      (footprint "eagle-import:0201")
      (fields (field (name "LCSC_PART") "C285015"))
      (libsource (lib "eagle-import") (part "6.8NF-50V0201"))
    )
    (comp (ref "C83")
      (value "C1206C102KGRACTM")
      (footprint "eagle-import:C1206")
      (libsource (lib "eagle-import") (part "C-1206"))
    )
    (comp (ref "C84")
      (value "100nF 25V")
      (footprint "eagle-import:0201")
      (fields (field (name "LCSC_PART") "C76939"))
      (libsource (lib "eagle-import") (part "100NF-25V-0201"))
    )
    (comp (ref "C85")
      (value "4.7uF 25V")
      (footprint "eagle-import:0402")
      (fields (field (name "LCSC_PART") "C22367824"))
      (libsource (lib "eagle-import") (part "4.7UF-25V0402"))
    )
    (comp (ref "C86")
      (value "18pF 50V")
      (footprint "eagle-import:0201")
      (fields (field (name "LCSC_PART") "C62164"))
      (libsource (lib "eagle-import") (part "18PF-50V-0201"))
    )
    (comp (ref "C87")
      (value "18pF 50V")
      (footprint "eagle-import:0201")
      (fields (field (name "LCSC_PART") "C62164"))
      (libsource (lib "eagle-import") (part "18PF-50V-0201"))
    )
    (comp (ref "C88")
      (value "100nF 25V")
      (footprint "eagle-import:0201")
      (fields (field (name "LCSC_PART") "C76939"))
      (libsource (lib "eagle-import") (part "100NF-25V-0201"))
    )
    (comp (ref "C89")
      (value "100nF 25V")
      (footprint "eagle-import:0201")
      (fields (field (name "LCSC_PART") "C76939"))
      (libsource (lib "eagle-import") (part "100NF-25V-0201"))
    )
    (comp (ref "C90")
      (value "100nF 25V")
      (footprint "eagle-import:0201")
      (fields (field (name "LCSC_PART") "C76939"))
      (libsource (lib "eagle-import") (part "100NF-25V-0201"))
    )
    (comp (ref "C91")
      (value "100nF 25V")
      (footprint "eagle-import:0201")
      (fields (field (name "LCSC_PART") "C76939"))
      (libsource (lib "eagle-import") (part "100NF-25V-0201"))
    )
    (comp (ref "C92")
      (value "100nF 25V")
      (footprint "eagle-import:0201")
      (fields (field (name "LCSC_PART") "C76939"))
      (libsource (lib "eagle-import") (part "100NF-25V-0201"))
    )
    (comp (ref "C93")
      (value "100nF 25V")
      (footprint "eagle-import:0201")
      (fields (field (name "LCSC_PART") "C76939"))
      (libsource (lib "eagle-import") (part "100NF-25V-0201"))
    )
    (comp (ref "C94")
      (value "100nF 25V")
      (footprint "eagle-import:0201")
      (fields (field (name "LCSC_PART") "C76939"))
      (libsource (lib "eagle-import") (part "100NF-25V-0201"))
    )
    (comp (ref "C95")
      (value "100nF 25V")
      (footprint "eagle-import:0201")
      (fields (field (name "LCSC_PART") "C76939"))
      (libsource (lib "eagle-import") (part "100NF-25V-0201"))
    )
    (comp (ref "C96")
      (value "100nF 25V")
      (footprint "eagle-import:0201")
      (fields (field (name "LCSC_PART") "C76939"))
      (libsource (lib "eagle-import") (part "100NF-25V-0201"))
    )
    (comp (ref "ETH1")
      (value "J1B1211CCD")
      (footprint "eagle-import:J1B1211CCD")
      (fields (field (name "LCSC_PART") "C910371"))
      (libsource (lib "eagle-import") (part "J1B1211CCD"))
    )
    (comp (ref "IC20")
      (value "W5500")
      (footprint "eagle-import:LQFP48")
      (fields (field (name "LCSC_PART") "C32843"))
      (libsource (lib "eagle-import") (part "W5500"))
    )
    (comp (ref "L4")
      (value "BLM18EG221TN1D")
      (footprint "eagle-import:0603")
      (fields (field (name "LCSC_PART") "C113025"))
      (libsource (lib "eagle-import") (part "BLM18EG221TN1D"))
    )
    (comp (ref "R110")
      (value "1M 1%")
      (footprint "eagle-import:1206")
      (fields (field (name "LCSC_PART") "C17927"))
      (libsource (lib "eagle-import") (part "1M-1%1206"))
    )
    (comp (ref "R133")
      (value "3.3R 1%")
      (footprint "eagle-import:0201")
      (fields (field (name "LCSC_PART") "C158547"))
      (libsource (lib "eagle-import") (part "3.3R-1%0201"))
    )
    (comp (ref "R134")
      (value "3.3R 1%")
      (footprint "eagle-import:0201")
      (fields (field (name "LCSC_PART") "C158547"))
      (libsource (lib "eagle-import") (part "3.3R-1%0201"))
    )
    (comp (ref "R135")
      (value "3.3R 1%")
      (footprint "eagle-import:0201")
      (fields (field (name "LCSC_PART") "C158547"))
      (libsource (lib "eagle-import") (part "3.3R-1%0201"))
    )
    (comp (ref "R136")
      (value "3.3R 1%")
      (footprint "eagle-import:0201")
      (fields (field (name "LCSC_PART") "C158547"))
      (libsource (lib "eagle-import") (part "3.3R-1%0201"))
    )
    (comp (ref "R137")
      (value "49.9R 1%")
      (footprint "eagle-import:0201")
      (fields (field (name "LCSC_PART") "C155744"))
      (libsource (lib "eagle-import") (part "49.9R-1%0201"))
    )
    (comp (ref "R138")
      (value "49.9R 1%")
      (footprint "eagle-import:0201")
      (fields (field (name "LCSC_PART") "C155744"))
      (libsource (lib "eagle-import") (part "49.9R-1%0201"))
    )
    (comp (ref "R139")
      (value "49.9R 1%")
      (footprint "eagle-import:0201")
      (fields (field (name "LCSC_PART") "C155744"))
      (libsource (lib "eagle-import") (part "49.9R-1%0201"))
    )
    (comp (ref "R140")
      (value "49.9R 1%")
      (footprint "eagle-import:0201")
      (fields (field (name "LCSC_PART") "C155744"))
      (libsource (lib "eagle-import") (part "49.9R-1%0201"))
    )
    (comp (ref "R141")
      (value "470R 1%")
      (footprint "eagle-import:0402")
      (fields (field (name "LCSC_PART") "C25117"))
      (libsource (lib "eagle-import") (part "470R-1%0402"))
    )
    (comp (ref "R142")
      (value "470R 1%")
      (footprint "eagle-import:0402")
      (fields (field (name "LCSC_PART") "C25117"))
      (libsource (lib "eagle-import") (part "470R-1%0402"))
    )
    (comp (ref "R143")
      (value "12.4K 1%")
      (footprint "eagle-import:R0201")
      (libsource (lib "eagle-import") (part "R0201"))
    )
    (comp (ref "R144")
      (value "1M 1%")
      (footprint "eagle-import:0201")
      (fields (field (name "LCSC_PART") "C295786"))
      (libsource (lib "eagle-import") (part "1M-1%0201"))
    )
    (comp (ref "R145")
      (value "4.7K 1%")
      (footprint "eagle-import:0201")
      (fields (field (name "LCSC_PART") "C270346"))
      (libsource (lib "eagle-import") (part "4.7K-1%0201"))
    )
    (comp (ref "R146")
      (value "470R 1%")
      (footprint "eagle-import:0402")
      (fields (field (name "LCSC_PART") "C25117"))
      (libsource (lib "eagle-import") (part "470R-1%0402"))
    )
    (comp (ref "X2")
      (value "25MHz")
      (footprint "eagle-import:WE-XTAL_CFPX-180")
      (fields (field (name "LCSC_PART") "C9006"))
      (libsource (lib "eagle-import") (part "CRYSTAL-3225X322525MOB4SI"))
    )
    (comp (ref "3VDC")
      (value "TP")
      (footprint "eagle-import:TP")
      (libsource (lib "eagle-import") (part "TP"))
    )
    (comp (ref "3VFB")
      (value "TP")
      (footprint "eagle-import:TP")
      (libsource (lib "eagle-import") (part "TP"))
    )
    (comp (ref "5V-NI1")
      (value "TP")
      (footprint "eagle-import:TP")
      (libsource (lib "eagle-import") (part "TP"))
    )
    (comp (ref "5V-NI2")
      (value "TP")
      (footprint "eagle-import:TP")
      (libsource (lib "eagle-import") (part "TP"))
    )
    (comp (ref "5VDC")
      (value "TP")
      (footprint "eagle-import:TP")
      (libsource (lib "eagle-import") (part "TP"))
    )
    (comp (ref "5VFB")
      (value "TP")
      (footprint "eagle-import:TP")
      (libsource (lib "eagle-import") (part "TP"))
    )
    (comp (ref "12VDC")
      (value "TP")
      (footprint "eagle-import:TP")
      (libsource (lib "eagle-import") (part "TP"))
    )
    (comp (ref "AC/DC1")
      (value "IRM_10_12")
      (footprint "eagle-import:IRM_10_12")
      (fields (field (name "LCSC_PART") "C20618065"))
      (libsource (lib "eagle-import") (part "IRM_10_12"))
    )
    (comp (ref "AC/DC2")
      (value "IRM-10-15")
      (footprint "eagle-import:IRM_15_12")
      (fields (field (name "LCSC_PART") "C5439799"))
      (libsource (lib "eagle-import") (part "IRM_10_12-2"))
    )
    (comp (ref "AC_L")
      (value "MOUNT-PAD-ROUND3.0")
      (footprint "eagle-import:3,0-PAD")
      (libsource (lib "eagle-import") (part "MOUNT-PAD-ROUND3.0"))
    )
    (comp (ref "AC_N")
      (value "MOUNT-PAD-ROUND3.0")
      (footprint "eagle-import:3,0-PAD")
      (libsource (lib "eagle-import") (part "MOUNT-PAD-ROUND3.0"))
    )
    (comp (ref "C1")
      (value "22uF 25V")
      (footprint "eagle-import:1206")
      (fields (field (name "LCSC_PART") "C12891"))
      (libsource (lib "eagle-import") (part "22UF-25V-1206"))
    )
    (comp (ref "C2")
      (value "22uF 25V")
      (footprint "eagle-import:1206")
      (fields (field (name "LCSC_PART") "C12891"))
      (libsource (lib "eagle-import") (part "22UF-25V-1206"))
    )
    (comp (ref "C3")
      (value "100nF 25V")
      (footprint "eagle-import:0402")
      (fields (field (name "LCSC_PART") "C56392"))
      (libsource (lib "eagle-import") (part "100NF-25V-0402"))
    )
    (comp (ref "C4")
      (value "100nF 25V")
      (footprint "eagle-import:0402")
      (fields (field (name "LCSC_PART") "C56392"))
      (libsource (lib "eagle-import") (part "100NF-25V-0402"))
    )
    (comp (ref "C5")
      (value "1nF 50V")
      (footprint "eagle-import:0603")
      (fields (field (name "LCSC_PART") "C1588"))
      (libsource (lib "eagle-import") (part "1NF-50V-0603"))
    )
    (comp (ref "C6")
      (value "100nF 25V")
      (footprint "eagle-import:0402")
      (fields (field (name "LCSC_PART") "C56392"))
      (libsource (lib "eagle-import") (part "100NF-25V-0402"))
    )
    (comp (ref "C7")
      (value "100nF 25V")
      (footprint "eagle-import:0402")
      (fields (field (name "LCSC_PART") "C56392"))
      (libsource (lib "eagle-import") (part "100NF-25V-0402"))
    )
    (comp (ref "C8")
      (value "100nF 25V")
      (footprint "eagle-import:0402")
      (fields (field (name "LCSC_PART") "C56392"))
      (libsource (lib "eagle-import") (part "100NF-25V-0402"))
    )
    (comp (ref "C9")
      (value "100nF 25V")
      (footprint "eagle-import:0402")
      (fields (field (name "LCSC_PART") "C56392"))
      (libsource (lib "eagle-import") (part "100NF-25V-0402"))
    )
    (comp (ref "C10")
      (value "100uF 25V")
      (footprint "eagle-import:6.3X7.7(DXL)")
      (fields (field (name "LCSC_PART") "C267469"))
      (libsource (lib "eagle-import") (part "100UF-25V6.3X7.7(DXL)"))
    )
    (comp (ref "C11")
      (value "33pF 50V")
      (footprint "eagle-import:0402")
      (fields (field (name "LCSC_PART") "C107005"))
      (libsource (lib "eagle-import") (part "33PF-50V0402"))
    )
    (comp (ref "C12")
      (value "33pF 50V")
      (footprint "eagle-import:0402")
      (fields (field (name "LCSC_PART") "C107005"))
      (libsource (lib "eagle-import") (part "33PF-50V0402"))
    )
    (comp (ref "C13")
      (value "100uF 25V")
      (footprint "eagle-import:6.3X7.7(DXL)")
      (fields (field (name "LCSC_PART") "C267469"))
      (libsource (lib "eagle-import") (part "100UF-25V6.3X7.7(DXL)"))
    )
    (comp (ref "C14")
      (value "22uF 25V")
      (footprint "eagle-import:1206")
      (fields (field (name "LCSC_PART") "C12891"))
      (libsource (lib "eagle-import") (part "22UF-25V-1206"))
    )
    (comp (ref "C15")
      (value "22uF 25V")
      (footprint "eagle-import:1206")
      (fields (field (name "LCSC_PART") "C12891"))
      (libsource (lib "eagle-import") (part "22UF-25V-1206"))
    )
    (comp (ref "C16")
      (value "100uF 25V")
      (footprint "eagle-import:6.3X7.7(DXL)")
      (fields (field (name "LCSC_PART") "C267469"))
      (libsource (lib "eagle-import") (part "100UF-25V6.3X7.7(DXL)"))
    )
    (comp (ref "C17")
      (value "22uF 25V")
      (footprint "eagle-import:1206")
      (fields (field (name "LCSC_PART") "C12891"))
      (libsource (lib "eagle-import") (part "22UF-25V-1206"))
    )
    (comp (ref "C18")
      (value "22uF 25V")
      (footprint "eagle-import:1206")
      (fields (field (name "LCSC_PART") "C12891"))
      (libsource (lib "eagle-import") (part "22UF-25V-1206"))
    )
    (comp (ref "C21")
      (value "2.2uF 50V")
      (footprint "eagle-import:0603")
      (fields (field (name "LCSC_PART") "C913904"))
      (libsource (lib "eagle-import") (part "2.2UF-50V0603"))
    )
    (comp (ref "C22")
      (value "220nF 50V")
      (footprint "eagle-import:0805")
      (fields (field (name "LCSC_PART") "C5378"))
      (libsource (lib "eagle-import") (part "220NF-50V0805"))
    )
    (comp (ref "C23")
      (value "100uF 50V")
      (footprint "eagle-import:6.3X7.7(DXL)")
      (fields (field (name "LCSC_PART") "C3151829"))
      (libsource (lib "eagle-import") (part "100UF-50V6.3X7.7(DXL)"))
    )
    (comp (ref "C35")
      (value "2.2uF 400V")
      (footprint "eagle-import:6.3X7.7(DXL)")
      (fields (field (name "LCSC_PART") "C3345109"))
      (libsource (lib "eagle-import") (part "2.2UF-400V6.3X7.7(DXL)"))
    )
    (comp (ref "C45")
      (value "1uF 50V")
      (footprint "eagle-import:0805")
      (fields (field (name "LCSC_PART") "C28323"))
      (libsource (lib "eagle-import") (part "1UF-50V0805"))
    )
    (comp (ref "C46")
      (value "2.2uF 50V")
      (footprint "eagle-import:0603")
      (fields (field (name "LCSC_PART") "C913904"))
      (libsource (lib "eagle-import") (part "2.2UF-50V0603"))
    )
    (comp (ref "C47")
      (value "2.2uF 400V")
      (footprint "eagle-import:6.3X7.7(DXL)")
      (fields (field (name "LCSC_PART") "C3345109"))
      (libsource (lib "eagle-import") (part "2.2UF-400V6.3X7.7(DXL)"))
    )
    (comp (ref "C51")
      (value "1nF 50V")
      (footprint "eagle-import:0603")
      (fields (field (name "LCSC_PART") "C1588"))
      (libsource (lib "eagle-import") (part "1NF-50V-0603"))
    )
    (comp (ref "C52")
      (value "220nF 50V")
      (footprint "eagle-import:0805")
      (fields (field (name "LCSC_PART") "C5378"))
      (libsource (lib "eagle-import") (part "220NF-50V0805"))
    )
    (comp (ref "C53")
      (value "100uF 50V")
      (footprint "eagle-import:6.3X7.7(DXL)")
      (fields (field (name "LCSC_PART") "C3151829"))
      (libsource (lib "eagle-import") (part "100UF-50V6.3X7.7(DXL)"))
    )
    (comp (ref "C57")
      (value "1uF 50V")
      (footprint "eagle-import:0805")
      (fields (field (name "LCSC_PART") "C28323"))
      (libsource (lib "eagle-import") (part "1UF-50V0805"))
    )
    (comp (ref "D9")
      (value "1N4007")
      (footprint "eagle-import:SMA_DO-214AC")
      (fields (field (name "LCSC_PART") "C727081"))
      (libsource (lib "eagle-import") (part "1N4007"))
    )
    (comp (ref "D10")
      (value "1N4007")
      (footprint "eagle-import:SMA_DO-214AC")
      (fields (field (name "LCSC_PART") "C727081"))
      (libsource (lib "eagle-import") (part "1N4007"))
    )
    (comp (ref "D11")
      (value "US1J-E3/61T")
      (footprint "eagle-import:SMA_DO-214AC")
      (fields (field (name "LCSC_PART") "C44763"))
      (libsource (lib "eagle-import") (part "US1J-E3/61T"))
    )
    (comp (ref "D12")
      (value "1N4007")
      (footprint "eagle-import:SMA_DO-214AC")
      (fields (field (name "LCSC_PART") "C727081"))
      (libsource (lib "eagle-import") (part "1N4007"))
    )
    (comp (ref "D13")
      (value "1N4007")
      (footprint "eagle-import:SMA_DO-214AC")
      (fields (field (name "LCSC_PART") "C727081"))
      (libsource (lib "eagle-import") (part "1N4007"))
    )
    (comp (ref "D14")
      (value "US1J-E3/61T")
      (footprint "eagle-import:SMA_DO-214AC")
      (fields (field (name "LCSC_PART") "C44763"))
      (libsource (lib "eagle-import") (part "US1J-E3/61T"))
    )
    (comp (ref "D16")
      (value "SMAJ15A")
      (footprint "eagle-import:SMA_DO-214AC")
      (fields (field (name "LCSC_PART") "C23424"))
      (libsource (lib "eagle-import") (part "SMAJ15A"))
    )
    (comp (ref "FB-NI1")
      (value "TP")
      (footprint "eagle-import:TP")
      (libsource (lib "eagle-import") (part "TP"))
    )
    (comp (ref "FB-NI2")
      (value "TP")
      (footprint "eagle-import:TP")
      (libsource (lib "eagle-import") (part "TP"))
    )
    (comp (ref "GND") (value "TP") (footprint "eagle-import:TP") (libsource (lib "eagle-import") (part "TP")))
    (comp (ref "GND-3")
      (value "TP")
      (footprint "eagle-import:TP")
      (libsource (lib "eagle-import") (part "TP"))
    )
    (comp (ref "GND-5")
      (value "TP")
      (footprint "eagle-import:TP")
      (libsource (lib "eagle-import") (part "TP"))
    )
    (comp (ref "IC1")
      (value "MP2315GJ-Z")
      (footprint "eagle-import:SOT65P280X110-8N")
      (fields (field (name "LCSC_PART") "C45889"))
      (libsource (lib "eagle-import") (part "MP2315TSOT23-8"))
    )
    (comp (ref "IC2")
      (value "MP2315GJ-Z")
      (footprint "eagle-import:SOT65P280X110-8N")
      (fields (field (name "LCSC_PART") "C45889"))
      (libsource (lib "eagle-import") (part "MP2315TSOT23-8"))
    )
    (comp (ref "IC5")
      (value "MP150GJ")
      (footprint "eagle-import:SOT23-5")
      (libsource (lib "eagle-import") (part "MP150GJ"))
    )
    (comp (ref "IC13")
      (value "MP150GJ")
      (footprint "eagle-import:SOT23-5")
      (libsource (lib "eagle-import") (part "MP150GJ"))
    )
    (comp (ref "J2") (value "JP") (footprint "eagle-import:SJ") (libsource (lib "eagle-import") (part "SJ")))
    (comp (ref "J7") (value "JP") (footprint "eagle-import:SJ") (libsource (lib "eagle-import") (part "SJ")))
    (comp (ref "J8")
      (value "0R 1%")
      (footprint "eagle-import:0805")
      (fields (field (name "LCSC_PART") "C17477"))
      (libsource (lib "eagle-import") (part "0R0805"))
    )
    (comp (ref "J9")
      (value "0R 1%")
      (footprint "eagle-import:0805")
      (fields (field (name "LCSC_PART") "C17477"))
      (libsource (lib "eagle-import") (part "0R0805"))
    )
    (comp (ref "J10")
      (value "0R 1%")
      (footprint "eagle-import:0805")
      (fields (field (name "LCSC_PART") "C17477"))
      (libsource (lib "eagle-import") (part "0R0805"))
    )
    (comp (ref "L-REC1")
      (value "TP")
      (footprint "eagle-import:TP")
      (libsource (lib "eagle-import") (part "TP"))
    )
    (comp (ref "L-REC2")
      (value "TP")
      (footprint "eagle-import:TP")
      (libsource (lib "eagle-import") (part "TP"))
    )
    (comp (ref "L1")
      (value "4.9uH")
      (footprint "eagle-import:SRR5228A")
      (libsource (lib "eagle-import") (part "L"))
    )
    (comp (ref "L2")
      (value "4.2uH")
      (footprint "eagle-import:SRR5228A")
      (libsource (lib "eagle-import") (part "L"))
    )
    (comp (ref "L3")
      (value "1mH")
      (footprint "eagle-import:L-6.6X6.6")
      (fields (field (name "LCSC_PART") "C168049"))
      (libsource (lib "eagle-import") (part "1MHL-6.6X6.6"))
    )
    (comp (ref "L5")
      (value "1mH")
      (footprint "eagle-import:L-6.6X6.6")
      (fields (field (name "LCSC_PART") "C168049"))
      (libsource (lib "eagle-import") (part "1MHL-6.6X6.6"))
    )
    (comp (ref "P3ON")
      (value "Green")
      (footprint "eagle-import:LED-0603")
      (fields (field (name "LCSC_PART") "C965804"))
      (libsource (lib "eagle-import") (part "LED-GREENLED-0603"))
    )
    (comp (ref "P5ON")
      (value "Green")
      (footprint "eagle-import:LED-0603")
      (fields (field (name "LCSC_PART") "C965804"))
      (libsource (lib "eagle-import") (part "LED-GREENLED-0603"))
    )
    (comp (ref "P12ON")
      (value "Green")
      (footprint "eagle-import:LED-0603")
      (fields (field (name "LCSC_PART") "C965804"))
      (libsource (lib "eagle-import") (part "LED-GREENLED-0603"))
    )
    (comp (ref "R1")
      (value "DNI")
      (footprint "eagle-import:0402")
      (libsource (lib "eagle-import") (part "R0402"))
    )
    (comp (ref "R2")
      (value "10K 1%")
      (footprint "eagle-import:0402")
      (fields (field (name "LCSC_PART") "C25744"))
      (libsource (lib "eagle-import") (part "10K-1%0402"))
    )
    (comp (ref "R3")
      (value "100K 1%")
      (footprint "eagle-import:0402")
      (fields (field (name "LCSC_PART") "C25741"))
      (libsource (lib "eagle-import") (part "100K-1%0402"))
    )
    (comp (ref "R4")
      (value "9.09K 1%")
      (footprint "eagle-import:0402")
      (fields (field (name "LCSC_PART") "C11549"))
      (libsource (lib "eagle-import") (part "9.09K-1%0402"))
    )
    (comp (ref "R5")
      (value "100K 1%")
      (footprint "eagle-import:0402")
      (fields (field (name "LCSC_PART") "C25741"))
      (libsource (lib "eagle-import") (part "100K-1%0402"))
    )
    (comp (ref "R6")
      (value "7.5K 1%")
      (footprint "eagle-import:0402")
      (fields (field (name "LCSC_PART") "C25918"))
      (libsource (lib "eagle-import") (part "7.5K-1%0402"))
    )
    (comp (ref "R7")
      (value "10R 1%")
      (footprint "eagle-import:0402")
      (fields (field (name "LCSC_PART") "C25077"))
      (libsource (lib "eagle-import") (part "10R-1%0402"))
    )
    (comp (ref "R8")
      (value "20K 1%")
      (footprint "eagle-import:0402")
      (fields (field (name "LCSC_PART") "C25765"))
      (libsource (lib "eagle-import") (part "20K-1%0402"))
    )
    (comp (ref "R9")
      (value "10R 1%")
      (footprint "eagle-import:0402")
      (fields (field (name "LCSC_PART") "C25077"))
      (libsource (lib "eagle-import") (part "10R-1%0402"))
    )
    (comp (ref "R10")
      (value "33K")
      (footprint "eagle-import:0402")
      (libsource (lib "eagle-import") (part "R0402"))
    )
    (comp (ref "R11")
      (value "40.2K 1%")
      (footprint "eagle-import:0402")
      (fields (field (name "LCSC_PART") "C25893"))
      (libsource (lib "eagle-import") (part "40.2K-1%0402"))
    )
    (comp (ref "R12")
      (value "7.5K 1%")
      (footprint "eagle-import:0402")
      (fields (field (name "LCSC_PART") "C25918"))
      (libsource (lib "eagle-import") (part "7.5K-1%0402"))
    )
    (comp (ref "R13")
      (value "40.2K 1%")
      (footprint "eagle-import:0402")
      (fields (field (name "LCSC_PART") "C25893"))
      (libsource (lib "eagle-import") (part "40.2K-1%0402"))
    )
    (comp (ref "R14")
      (value "12.7K 1%")
      (footprint "eagle-import:0402")
      (fields (field (name "LCSC_PART") "C25853"))
      (libsource (lib "eagle-import") (part "12.7K-1%0402"))
    )
    (comp (ref "R60")
      (value "4.99K 1%")
      (footprint "eagle-import:0603")
      (fields (field (name "LCSC_PART") "C23046"))
      (libsource (lib "eagle-import") (part "4.99K-1%0603"))
    )
    (comp (ref "R61")
      (value "4.99K 1%")
      (footprint "eagle-import:0603")
      (fields (field (name "LCSC_PART") "C23046"))
      (libsource (lib "eagle-import") (part "4.99K-1%0603"))
    )
    (comp (ref "R62")
      (value "39R 1% 2W")
      (footprint "eagle-import:2512")
      (fields (field (name "LCSC_PART") "C175263"))
      (libsource (lib "eagle-import") (part "39R-1%2512"))
    )
    (comp (ref "R94")
      (value "100K 1%")
      (footprint "eagle-import:0402")
      (fields (field (name "LCSC_PART") "C25741"))
      (libsource (lib "eagle-import") (part "100K-1%0402"))
    )
    (comp (ref "R95")
      (value "10K 1%")
      (footprint "eagle-import:0402")
      (fields (field (name "LCSC_PART") "C25744"))
      (libsource (lib "eagle-import") (part "10K-1%0402"))
    )
    (comp (ref "R96")
      (value "10K 1%")
      (footprint "eagle-import:0805")
      (fields (field (name "LCSC_PART") "C17414"))
      (libsource (lib "eagle-import") (part "10K-1%0805"))
    )
    (comp (ref "R105")
      (value "4.99K 1%")
      (footprint "eagle-import:0603")
      (fields (field (name "LCSC_PART") "C23046"))
      (libsource (lib "eagle-import") (part "4.99K-1%0603"))
    )
    (comp (ref "R106")
      (value "39R 1% 2W")
      (footprint "eagle-import:2512")
      (fields (field (name "LCSC_PART") "C175263"))
      (libsource (lib "eagle-import") (part "39R-1%2512"))
    )
    (comp (ref "R107")
      (value "4.99K 1%")
      (footprint "eagle-import:0603")
      (fields (field (name "LCSC_PART") "C23046"))
      (libsource (lib "eagle-import") (part "4.99K-1%0603"))
    )
    (comp (ref "R108")
      (value "10K 1%")
      (footprint "eagle-import:0805")
      (fields (field (name "LCSC_PART") "C17414"))
      (libsource (lib "eagle-import") (part "10K-1%0805"))
    )
    (comp (ref "R123")
      (value "1K 1%")
      (footprint "eagle-import:0402")
      (fields (field (name "LCSC_PART") "C11702"))
      (libsource (lib "eagle-import") (part "1K-1%0402"))
    )
    (comp (ref "R148")
      (value "2.4K 1%")
      (footprint "eagle-import:0402")
      (fields (field (name "LCSC_PART") "C25882"))
      (libsource (lib "eagle-import") (part "2.4K-1%0402"))
    )
    (comp (ref "R150")
      (value "8.2K 1%")
      (footprint "eagle-import:0402")
      (fields (field (name "LCSC_PART") "C25924"))
      (libsource (lib "eagle-import") (part "8.2K-1%0402"))
    )
    (comp (ref "R161")
      (value "DNI")
      (footprint "eagle-import:0402")
      (libsource (lib "eagle-import") (part "R0402"))
    )
    (comp (ref "R162")
      (value "10K 1%")
      (footprint "eagle-import:0402")
      (fields (field (name "LCSC_PART") "C25744"))
      (libsource (lib "eagle-import") (part "10K-1%0402"))
    )
    (comp (ref "SW") (value "TP") (footprint "eagle-import:TP") (libsource (lib "eagle-import") (part "TP")))
    (comp (ref "SW3") (value "TP") (footprint "eagle-import:TP") (libsource (lib "eagle-import") (part "TP")))
    (comp (ref "VNI1")
      (value "TP")
      (footprint "eagle-import:TP")
      (libsource (lib "eagle-import") (part "TP"))
    )
    (comp (ref "VNI2")
      (value "TP")
      (footprint "eagle-import:TP")
      (libsource (lib "eagle-import") (part "TP"))
    )
    (comp (ref "D1")
      (value "MBRA340T3G")
      (footprint "eagle-import:SMA_DO-214AC")
      (fields (field (name "LCSC_PART") "C26178"))
      (libsource (lib "eagle-import") (part "MBRA340T3G"))
    )
    (comp (ref "D2")
      (value "MBRA340T3G")
      (footprint "eagle-import:SMA_DO-214AC")
      (fields (field (name "LCSC_PART") "C26178"))
      (libsource (lib "eagle-import") (part "MBRA340T3G"))
    )
    (comp (ref "D3")
      (value "MBRA340T3G")
      (footprint "eagle-import:SMA_DO-214AC")
      (fields (field (name "LCSC_PART") "C26178"))
      (libsource (lib "eagle-import") (part "MBRA340T3G"))
    )
    (comp (ref "D4")
      (value "MBRA340T3G")
      (footprint "eagle-import:SMA_DO-214AC")
      (fields (field (name "LCSC_PART") "C26178"))
      (libsource (lib "eagle-import") (part "MBRA340T3G"))
    )
    (comp (ref "D5")
      (value "MBRA340T3G")
      (footprint "eagle-import:SMA_DO-214AC")
      (fields (field (name "LCSC_PART") "C26178"))
      (libsource (lib "eagle-import") (part "MBRA340T3G"))
    )
    (comp (ref "D6")
      (value "MBRA340T3G")
      (footprint "eagle-import:SMA_DO-214AC")
      (fields (field (name "LCSC_PART") "C26178"))
      (libsource (lib "eagle-import") (part "MBRA340T3G"))
    )
    (comp (ref "D7")
      (value "MBRA340T3G")
      (footprint "eagle-import:SMA_DO-214AC")
      (fields (field (name "LCSC_PART") "C26178"))
      (libsource (lib "eagle-import") (part "MBRA340T3G"))
    )
    (comp (ref "D8")
      (value "MBRA340T3G")
      (footprint "eagle-import:SMA_DO-214AC")
      (fields (field (name "LCSC_PART") "C26178"))
      (libsource (lib "eagle-import") (part "MBRA340T3G"))
    )
    (comp (ref "K1")
      (value "G2RL-1A-E DC12")
      (footprint "eagle-import:RELAY_G2RL-1A-E_DC5_OMR")
      (fields (field (name "LCSC_PART") "C1564126"))
      (libsource (lib "eagle-import") (part "G2RL-1A-E_DC12"))
    )
    (comp (ref "K2")
      (value "G2RL-1A-E DC12")
      (footprint "eagle-import:RELAY_G2RL-1A-E_DC5_OMR")
      (fields (field (name "LCSC_PART") "C1564126"))
      (libsource (lib "eagle-import") (part "G2RL-1A-E_DC12"))
    )
    (comp (ref "K3")
      (value "G2RL-1A-E DC12")
      (footprint "eagle-import:RELAY_G2RL-1A-E_DC5_OMR")
      (fields (field (name "LCSC_PART") "C1564126"))
      (libsource (lib "eagle-import") (part "G2RL-1A-E_DC12"))
    )
    (comp (ref "K4")
      (value "G2RL-1A-E DC12")
      (footprint "eagle-import:RELAY_G2RL-1A-E_DC5_OMR")
      (fields (field (name "LCSC_PART") "C1564126"))
      (libsource (lib "eagle-import") (part "G2RL-1A-E_DC12"))
    )
    (comp (ref "K5")
      (value "G2RL-1A-E DC12")
      (footprint "eagle-import:RELAY_G2RL-1A-E_DC5_OMR")
      (fields (field (name "LCSC_PART") "C1564126"))
      (libsource (lib "eagle-import") (part "G2RL-1A-E_DC12"))
    )
    (comp (ref "K6")
      (value "G2RL-1A-E DC12")
      (footprint "eagle-import:RELAY_G2RL-1A-E_DC5_OMR")
      (fields (field (name "LCSC_PART") "C1564126"))
      (libsource (lib "eagle-import") (part "G2RL-1A-E_DC12"))
    )
    (comp (ref "K7")
      (value "G2RL-1A-E DC12")
      (footprint "eagle-import:RELAY_G2RL-1A-E_DC5_OMR")
      (fields (field (name "LCSC_PART") "C1564126"))
      (libsource (lib "eagle-import") (part "G2RL-1A-E_DC12"))
    )
    (comp (ref "K8")
      (value "G2RL-1A-E DC12")
      (footprint "eagle-import:RELAY_G2RL-1A-E_DC5_OMR")
      (fields (field (name "LCSC_PART") "C1564126"))
      (libsource (lib "eagle-import") (part "G2RL-1A-E_DC12"))
    )
    (comp (ref "C19")
      (value "100nF 25V")
      (footprint "eagle-import:0402")
      (fields (field (name "LCSC_PART") "C56392"))
      (libsource (lib "eagle-import") (part "100NF-25V-0402"))
    )
    (comp (ref "C20")
      (value "100nF 25V")
      (footprint "eagle-import:0402")
      (fields (field (name "LCSC_PART") "C56392"))
      (libsource (lib "eagle-import") (part "100NF-25V-0402"))
    )
    (comp (ref "C33")
      (value "100nF 25V")
      (footprint "eagle-import:0402")
      (fields (field (name "LCSC_PART") "C56392"))
      (libsource (lib "eagle-import") (part "100NF-25V-0402"))
    )
    (comp (ref "C34")
      (value "100nF 25V")
      (footprint "eagle-import:0402")
      (fields (field (name "LCSC_PART") "C56392"))
      (libsource (lib "eagle-import") (part "100NF-25V-0402"))
    )
    (comp (ref "C103")
      (value "100nF 25V")
      (footprint "eagle-import:0201")
      (fields (field (name "LCSC_PART") "C76939"))
      (libsource (lib "eagle-import") (part "100NF-25V-0201"))
    )
    (comp (ref "DAT")
      (value "Blue")
      (footprint "eagle-import:LED-0603")
      (fields (field (name "LCSC_PART") "C965807"))
      (libsource (lib "eagle-import") (part "LED-BLUELED-0603"))
    )
    (comp (ref "IC3")
      (value "ULN2803AFWG")
      (footprint "eagle-import:SO18")
      (fields (field (name "LCSC_PART") "C845537"))
      (libsource (lib "eagle-import") (part "ULN2803"))
    )
    (comp (ref "IC4")
      (value "MCP23017T-E/ML")
      (footprint "eagle-import:QFN28[6X6]ML")
      (fields (field (name "LCSC_PART") "C629439"))
      (libsource (lib "eagle-import") (part "MCP23017-E/ML"))
    )
    (comp (ref "IC9")
      (value "SN74HC151PWR")
      (footprint "eagle-import:TSSOP16")
      (fields (field (name "LCSC_PART") "C2653837"))
      (libsource (lib "eagle-import") (part "SN74HC151PWR"))
    )
    (comp (ref "IC22")
      (value "MCP6001RT-I/OT")
      (footprint "eagle-import:SOT23-5")
      (fields (field (name "LCSC_PART") "C154973"))
      (libsource (lib "eagle-import") (part "MCP6001RT"))
    )
    (comp (ref "R17")
      (value "0R 1%")
      (footprint "eagle-import:2512")
      (fields (field (name "LCSC_PART") "C25469"))
      (libsource (lib "eagle-import") (part "0R2512"))
    )
    (comp (ref "R18")
      (value "0R 1%")
      (footprint "eagle-import:2512")
      (fields (field (name "LCSC_PART") "C25469"))
      (libsource (lib "eagle-import") (part "0R2512"))
    )
    (comp (ref "R19")
      (value "0R 1%")
      (footprint "eagle-import:2512")
      (fields (field (name "LCSC_PART") "C25469"))
      (libsource (lib "eagle-import") (part "0R2512"))
    )
    (comp (ref "R20")
      (value "0R 1%")
      (footprint "eagle-import:2512")
      (fields (field (name "LCSC_PART") "C25469"))
      (libsource (lib "eagle-import") (part "0R2512"))
    )
    (comp (ref "R21")
      (value "0R 1%")
      (footprint "eagle-import:2512")
      (fields (field (name "LCSC_PART") "C25469"))
      (libsource (lib "eagle-import") (part "0R2512"))
    )
    (comp (ref "R22")
      (value "0R 1%")
      (footprint "eagle-import:2512")
      (fields (field (name "LCSC_PART") "C25469"))
      (libsource (lib "eagle-import") (part "0R2512"))
    )
    (comp (ref "R23")
      (value "0R 1%")
      (footprint "eagle-import:2512")
      (fields (field (name "LCSC_PART") "C25469"))
      (libsource (lib "eagle-import") (part "0R2512"))
    )
    (comp (ref "R24")
      (value "0R 1%")
      (footprint "eagle-import:2512")
      (fields (field (name "LCSC_PART") "C25469"))
      (libsource (lib "eagle-import") (part "0R2512"))
    )
    (comp (ref "R57")
      (value "0R 1%")
      (footprint "eagle-import:0402")
      (fields (field (name "LCSC_PART") "C17168"))
      (libsource (lib "eagle-import") (part "0R0402"))
    )
    (comp (ref "R58")
      (value "DNI")
      (footprint "eagle-import:0402")
      (libsource (lib "eagle-import") (part "R0402"))
    )
    (comp (ref "R91")
      (value "0R 1%")
      (footprint "eagle-import:0402")
      (fields (field (name "LCSC_PART") "C17168"))
      (libsource (lib "eagle-import") (part "0R0402"))
    )
    (comp (ref "R92")
      (value "DNI")
      (footprint "eagle-import:0402")
      (libsource (lib "eagle-import") (part "R0402"))
    )
    (comp (ref "R93")
      (value "10K 1%")
      (footprint "eagle-import:_0603X4-1206")
      (fields (field (name "LCSC_PART") "C110924"))
      (libsource (lib "eagle-import") (part "10K-1%_ARRAY0603X4-1206"))
    )
    (comp (ref "R122")
      (value "1K 1%")
      (footprint "eagle-import:0402")
      (fields (field (name "LCSC_PART") "C11702"))
      (libsource (lib "eagle-import") (part "1K-1%0402"))
    )
    (comp (ref "REL0")
      (value "TP")
      (footprint "eagle-import:TP")
      (libsource (lib "eagle-import") (part "TP"))
    )
    (comp (ref "REL1")
      (value "TP")
      (footprint "eagle-import:TP")
      (libsource (lib "eagle-import") (part "TP"))
    )
    (comp (ref "REL2")
      (value "TP")
      (footprint "eagle-import:TP")
      (libsource (lib "eagle-import") (part "TP"))
    )
    (comp (ref "REL3")
      (value "TP")
      (footprint "eagle-import:TP")
      (libsource (lib "eagle-import") (part "TP"))
    )
    (comp (ref "REL4")
      (value "TP")
      (footprint "eagle-import:TP")
      (libsource (lib "eagle-import") (part "TP"))
    )
    (comp (ref "REL5")
      (value "TP")
      (footprint "eagle-import:TP")
      (libsource (lib "eagle-import") (part "TP"))
    )
    (comp (ref "REL6")
      (value "TP")
      (footprint "eagle-import:TP")
      (libsource (lib "eagle-import") (part "TP"))
    )
    (comp (ref "REL7")
      (value "TP")
      (footprint "eagle-import:TP")
      (libsource (lib "eagle-import") (part "TP"))
    )
    (comp (ref "RN1")
      (value "100K 1%")
      (footprint "eagle-import:_0603X4-1206")
      (fields (field (name "LCSC_PART") "C110374"))
      (libsource (lib "eagle-import") (part "100K-1%_ARRAY0603X4-1206"))
    )
    (comp (ref "RN2")
      (value "100K 1%")
      (footprint "eagle-import:_0603X4-1206")
      (fields (field (name "LCSC_PART") "C110374"))
      (libsource (lib "eagle-import") (part "100K-1%_ARRAY0603X4-1206"))
    )
    (comp (ref "C24")
      (value "33nF 50V")
      (footprint "eagle-import:0805")
      (fields (field (name "LCSC_PART") "C107150"))
      (libsource (lib "eagle-import") (part "33NF-50V0805"))
    )
    (comp (ref "C25")
      (value "33nF 50V")
      (footprint "eagle-import:0805")
      (fields (field (name "LCSC_PART") "C107150"))
      (libsource (lib "eagle-import") (part "33NF-50V0805"))
    )
    (comp (ref "C26")
      (value "33nF 50V")
      (footprint "eagle-import:0805")
      (fields (field (name "LCSC_PART") "C107150"))
      (libsource (lib "eagle-import") (part "33NF-50V0805"))
    )
    (comp (ref "C27")
      (value "33nF 50V")
      (footprint "eagle-import:0805")
      (fields (field (name "LCSC_PART") "C107150"))
      (libsource (lib "eagle-import") (part "33NF-50V0805"))
    )
    (comp (ref "C28")
      (value "33nF 50V")
      (footprint "eagle-import:0805")
      (fields (field (name "LCSC_PART") "C107150"))
      (libsource (lib "eagle-import") (part "33NF-50V0805"))
    )
    (comp (ref "C29")
      (value "33nF 50V")
      (footprint "eagle-import:0805")
      (fields (field (name "LCSC_PART") "C107150"))
      (libsource (lib "eagle-import") (part "33NF-50V0805"))
    )
    (comp (ref "C30")
      (value "33nF 50V")
      (footprint "eagle-import:0805")
      (fields (field (name "LCSC_PART") "C107150"))
      (libsource (lib "eagle-import") (part "33NF-50V0805"))
    )
    (comp (ref "C31")
      (value "33nF 50V")
      (footprint "eagle-import:0805")
      (fields (field (name "LCSC_PART") "C107150"))
      (libsource (lib "eagle-import") (part "33NF-50V0805"))
    )
    (comp (ref "C32")
      (value "33nF 50V")
      (footprint "eagle-import:0805")
      (fields (field (name "LCSC_PART") "C107150"))
      (libsource (lib "eagle-import") (part "33NF-50V0805"))
    )
    (comp (ref "C36")
      (value "33nF 50V")
      (footprint "eagle-import:0805")
      (fields (field (name "LCSC_PART") "C107150"))
      (libsource (lib "eagle-import") (part "33NF-50V0805"))
    )
    (comp (ref "C37")
      (value "33nF 50V")
      (footprint "eagle-import:0805")
      (fields (field (name "LCSC_PART") "C107150"))
      (libsource (lib "eagle-import") (part "33NF-50V0805"))
    )
    (comp (ref "C38")
      (value "33nF 50V")
      (footprint "eagle-import:0805")
      (fields (field (name "LCSC_PART") "C107150"))
      (libsource (lib "eagle-import") (part "33NF-50V0805"))
    )
    (comp (ref "C39")
      (value "33nF 50V")
      (footprint "eagle-import:0805")
      (fields (field (name "LCSC_PART") "C107150"))
      (libsource (lib "eagle-import") (part "33NF-50V0805"))
    )
    (comp (ref "C40")
      (value "33nF 50V")
      (footprint "eagle-import:0805")
      (fields (field (name "LCSC_PART") "C107150"))
      (libsource (lib "eagle-import") (part "33NF-50V0805"))
    )
    (comp (ref "C41")
      (value "33nF 50V")
      (footprint "eagle-import:0805")
      (fields (field (name "LCSC_PART") "C107150"))
      (libsource (lib "eagle-import") (part "33NF-50V0805"))
    )
    (comp (ref "C42")
      (value "33nF 50V")
      (footprint "eagle-import:0805")
      (fields (field (name "LCSC_PART") "C107150"))
      (libsource (lib "eagle-import") (part "33NF-50V0805"))
    )
    (comp (ref "C43")
      (value "33nF 50V")
      (footprint "eagle-import:0805")
      (fields (field (name "LCSC_PART") "C107150"))
      (libsource (lib "eagle-import") (part "33NF-50V0805"))
    )
    (comp (ref "C44")
      (value "33nF 50V")
      (footprint "eagle-import:0805")
      (fields (field (name "LCSC_PART") "C107150"))
      (libsource (lib "eagle-import") (part "33NF-50V0805"))
    )
    (comp (ref "C48")
      (value "33nF 50V")
      (footprint "eagle-import:0805")
      (fields (field (name "LCSC_PART") "C107150"))
      (libsource (lib "eagle-import") (part "33NF-50V0805"))
    )
    (comp (ref "C49")
      (value "33nF 50V")
      (footprint "eagle-import:0805")
      (fields (field (name "LCSC_PART") "C107150"))
      (libsource (lib "eagle-import") (part "33NF-50V0805"))
    )
    (comp (ref "C50")
      (value "33nF 50V")
      (footprint "eagle-import:0805")
      (fields (field (name "LCSC_PART") "C107150"))
      (libsource (lib "eagle-import") (part "33NF-50V0805"))
    )
    (comp (ref "C54")
      (value "33nF 50V")
      (footprint "eagle-import:0805")
      (fields (field (name "LCSC_PART") "C107150"))
      (libsource (lib "eagle-import") (part "33NF-50V0805"))
    )
    (comp (ref "C55")
      (value "33nF 50V")
      (footprint "eagle-import:0805")
      (fields (field (name "LCSC_PART") "C107150"))
      (libsource (lib "eagle-import") (part "33NF-50V0805"))
    )
    (comp (ref "C56")
      (value "33nF 50V")
      (footprint "eagle-import:0805")
      (fields (field (name "LCSC_PART") "C107150"))
      (libsource (lib "eagle-import") (part "33NF-50V0805"))
    )
    (comp (ref "IC6")
      (value "HLW8032")
      (footprint "eagle-import:SO8")
      (fields (field (name "LCSC_PART") "C128023"))
      (libsource (lib "eagle-import") (part "HLW8032"))
    )
    (comp (ref "IC7")
      (value "HLW8032")
      (footprint "eagle-import:SO8")
      (fields (field (name "LCSC_PART") "C128023"))
      (libsource (lib "eagle-import") (part "HLW8032"))
    )
    (comp (ref "IC8")
      (value "HLW8032")
      (footprint "eagle-import:SO8")
      (fields (field (name "LCSC_PART") "C128023"))
      (libsource (lib "eagle-import") (part "HLW8032"))
    )
    (comp (ref "IC10")
      (value "HLW8032")
      (footprint "eagle-import:SO8")
      (fields (field (name "LCSC_PART") "C128023"))
      (libsource (lib "eagle-import") (part "HLW8032"))
    )
    (comp (ref "IC11")
      (value "HLW8032")
      (footprint "eagle-import:SO8")
      (fields (field (name "LCSC_PART") "C128023"))
      (libsource (lib "eagle-import") (part "HLW8032"))
    )
    (comp (ref "IC12")
      (value "HLW8032")
      (footprint "eagle-import:SO8")
      (fields (field (name "LCSC_PART") "C128023"))
      (libsource (lib "eagle-import") (part "HLW8032"))
    )
    (comp (ref "IC14")
      (value "HLW8032")
      (footprint "eagle-import:SO8")
      (fields (field (name "LCSC_PART") "C128023"))
      (libsource (lib "eagle-import") (part "HLW8032"))
    )
    (comp (ref "IC16")
      (value "HLW8032")
      (footprint "eagle-import:SO8")
      (fields (field (name "LCSC_PART") "C128023"))
      (libsource (lib "eagle-import") (part "HLW8032"))
    )
    (comp (ref "L_OUT1")
      (value "MOUNT-PAD-ROUND2.8")
      (footprint "eagle-import:2,8-PAD")
      (libsource (lib "eagle-import") (part "MOUNT-PAD-ROUND2.8"))
    )
    (comp (ref "L_OUT2")
      (value "MOUNT-PAD-ROUND2.8")
      (footprint "eagle-import:2,8-PAD")
      (libsource (lib "eagle-import") (part "MOUNT-PAD-ROUND2.8"))
    )
    (comp (ref "L_OUT3")
      (value "MOUNT-PAD-ROUND2.8")
      (footprint "eagle-import:2,8-PAD")
      (libsource (lib "eagle-import") (part "MOUNT-PAD-ROUND2.8"))
    )
    (comp (ref "L_OUT4")
      (value "MOUNT-PAD-ROUND2.8")
      (footprint "eagle-import:2,8-PAD")
      (libsource (lib "eagle-import") (part "MOUNT-PAD-ROUND2.8"))
    )
    (comp (ref "L_OUT5")
      (value "MOUNT-PAD-ROUND2.8")
      (footprint "eagle-import:2,8-PAD")
      (libsource (lib "eagle-import") (part "MOUNT-PAD-ROUND2.8"))
    )
    (comp (ref "L_OUT6")
      (value "MOUNT-PAD-ROUND2.8")
      (footprint "eagle-import:2,8-PAD")
      (libsource (lib "eagle-import") (part "MOUNT-PAD-ROUND2.8"))
    )
    (comp (ref "L_OUT7")
      (value "MOUNT-PAD-ROUND2.8")
      (footprint "eagle-import:2,8-PAD")
      (libsource (lib "eagle-import") (part "MOUNT-PAD-ROUND2.8"))
    )
    (comp (ref "L_OUT8")
      (value "MOUNT-PAD-ROUND2.8")
      (footprint "eagle-import:2,8-PAD")
      (libsource (lib "eagle-import") (part "MOUNT-PAD-ROUND2.8"))
    )
    (comp (ref "N_OUT1")
      (value "MOUNT-PAD-ROUND2.8")
      (footprint "eagle-import:2,8-PAD")
      (libsource (lib "eagle-import") (part "MOUNT-PAD-ROUND2.8"))
    )
    (comp (ref "N_OUT2")
      (value "MOUNT-PAD-ROUND2.8")
      (footprint "eagle-import:2,8-PAD")
      (libsource (lib "eagle-import") (part "MOUNT-PAD-ROUND2.8"))
    )
    (comp (ref "N_OUT3")
      (value "MOUNT-PAD-ROUND2.8")
      (footprint "eagle-import:2,8-PAD")
      (libsource (lib "eagle-import") (part "MOUNT-PAD-ROUND2.8"))
    )
    (comp (ref "N_OUT4")
      (value "MOUNT-PAD-ROUND2.8")
      (footprint "eagle-import:2,8-PAD")
      (libsource (lib "eagle-import") (part "MOUNT-PAD-ROUND2.8"))
    )
    (comp (ref "N_OUT5")
      (value "MOUNT-PAD-ROUND2.8")
      (footprint "eagle-import:2,8-PAD")
      (libsource (lib "eagle-import") (part "MOUNT-PAD-ROUND2.8"))
    )
    (comp (ref "N_OUT6")
      (value "MOUNT-PAD-ROUND2.8")
      (footprint "eagle-import:2,8-PAD")
      (libsource (lib "eagle-import") (part "MOUNT-PAD-ROUND2.8"))
    )
    (comp (ref "N_OUT7")
      (value "MOUNT-PAD-ROUND2.8")
      (footprint "eagle-import:2,8-PAD")
      (libsource (lib "eagle-import") (part "MOUNT-PAD-ROUND2.8"))
    )
    (comp (ref "N_OUT8")
      (value "MOUNT-PAD-ROUND2.8")
      (footprint "eagle-import:2,8-PAD")
      (libsource (lib "eagle-import") (part "MOUNT-PAD-ROUND2.8"))
    )
    (comp (ref "R25")
      (value "0.002R 1%")
      (footprint "eagle-import:2512")
      (fields (field (name "LCSC_PART") "C728320"))
      (libsource (lib "eagle-import") (part "0.002R-1%2512"))
    )
    (comp (ref "R26")
      (value "0.002R 1%")
      (footprint "eagle-import:2512")
      (fields (field (name "LCSC_PART") "C728320"))
      (libsource (lib "eagle-import") (part "0.002R-1%2512"))
    )
    (comp (ref "R27")
      (value "0.002R 1%")
      (footprint "eagle-import:2512")
      (fields (field (name "LCSC_PART") "C728320"))
      (libsource (lib "eagle-import") (part "0.002R-1%2512"))
    )
    (comp (ref "R28")
      (value "0.002R 1%")
      (footprint "eagle-import:2512")
      (fields (field (name "LCSC_PART") "C728320"))
      (libsource (lib "eagle-import") (part "0.002R-1%2512"))
    )
    (comp (ref "R29")
      (value "0.002R 1%")
      (footprint "eagle-import:2512")
      (fields (field (name "LCSC_PART") "C728320"))
      (libsource (lib "eagle-import") (part "0.002R-1%2512"))
    )
    (comp (ref "R30")
      (value "0.002R 1%")
      (footprint "eagle-import:2512")
      (fields (field (name "LCSC_PART") "C728320"))
      (libsource (lib "eagle-import") (part "0.002R-1%2512"))
    )
    (comp (ref "R31")
      (value "0.002R 1%")
      (footprint "eagle-import:2512")
      (fields (field (name "LCSC_PART") "C728320"))
      (libsource (lib "eagle-import") (part "0.002R-1%2512"))
    )
    (comp (ref "R32")
      (value "0.002R 1%")
      (footprint "eagle-import:2512")
      (fields (field (name "LCSC_PART") "C728320"))
      (libsource (lib "eagle-import") (part "0.002R-1%2512"))
    )
    (comp (ref "R33")
      (value "1K 1%")
      (footprint "eagle-import:0805")
      (fields (field (name "LCSC_PART") "C17513"))
      (libsource (lib "eagle-import") (part "1K-1%0805"))
    )
    (comp (ref "R34")
      (value "1K 1%")
      (footprint "eagle-import:0805")
      (fields (field (name "LCSC_PART") "C17513"))
      (libsource (lib "eagle-import") (part "1K-1%0805"))
    )
    (comp (ref "R35")
      (value "0.002R 1%")
      (footprint "eagle-import:2512")
      (fields (field (name "LCSC_PART") "C728320"))
      (libsource (lib "eagle-import") (part "0.002R-1%2512"))
    )
    (comp (ref "R36")
      (value "470K 1%")
      (footprint "eagle-import:0805")
      (fields (field (name "LCSC_PART") "C17709"))
      (libsource (lib "eagle-import") (part "470K-1%0805"))
    )
    (comp (ref "R37")
      (value "470K 1%")
      (footprint "eagle-import:0805")
      (fields (field (name "LCSC_PART") "C17709"))
      (libsource (lib "eagle-import") (part "470K-1%0805"))
    )
    (comp (ref "R38")
      (value "470K 1%")
      (footprint "eagle-import:0805")
      (fields (field (name "LCSC_PART") "C17709"))
      (libsource (lib "eagle-import") (part "470K-1%0805"))
    )
    (comp (ref "R39")
      (value "470K 1%")
      (footprint "eagle-import:0805")
      (fields (field (name "LCSC_PART") "C17709"))
      (libsource (lib "eagle-import") (part "470K-1%0805"))
    )
    (comp (ref "R40")
      (value "1K 1%")
      (footprint "eagle-import:0805")
      (fields (field (name "LCSC_PART") "C17513"))
      (libsource (lib "eagle-import") (part "1K-1%0805"))
    )
    (comp (ref "R41")
      (value "1K 1%")
      (footprint "eagle-import:0805")
      (fields (field (name "LCSC_PART") "C17513"))
      (libsource (lib "eagle-import") (part "1K-1%0805"))
    )
    (comp (ref "R42")
      (value "1K 1%")
      (footprint "eagle-import:0805")
      (fields (field (name "LCSC_PART") "C17513"))
      (libsource (lib "eagle-import") (part "1K-1%0805"))
    )
    (comp (ref "R43")
      (value "0.002R 1%")
      (footprint "eagle-import:2512")
      (fields (field (name "LCSC_PART") "C728320"))
      (libsource (lib "eagle-import") (part "0.002R-1%2512"))
    )
    (comp (ref "R44")
      (value "470K 1%")
      (footprint "eagle-import:0805")
      (fields (field (name "LCSC_PART") "C17709"))
      (libsource (lib "eagle-import") (part "470K-1%0805"))
    )
    (comp (ref "R45")
      (value "470K 1%")
      (footprint "eagle-import:0805")
      (fields (field (name "LCSC_PART") "C17709"))
      (libsource (lib "eagle-import") (part "470K-1%0805"))
    )
    (comp (ref "R46")
      (value "470K 1%")
      (footprint "eagle-import:0805")
      (fields (field (name "LCSC_PART") "C17709"))
      (libsource (lib "eagle-import") (part "470K-1%0805"))
    )
    (comp (ref "R47")
      (value "470K 1%")
      (footprint "eagle-import:0805")
      (fields (field (name "LCSC_PART") "C17709"))
      (libsource (lib "eagle-import") (part "470K-1%0805"))
    )
    (comp (ref "R48")
      (value "1K 1%")
      (footprint "eagle-import:0805")
      (fields (field (name "LCSC_PART") "C17513"))
      (libsource (lib "eagle-import") (part "1K-1%0805"))
    )
    (comp (ref "R49")
      (value "1K 1%")
      (footprint "eagle-import:0805")
      (fields (field (name "LCSC_PART") "C17513"))
      (libsource (lib "eagle-import") (part "1K-1%0805"))
    )
    (comp (ref "R50")
      (value "1K 1%")
      (footprint "eagle-import:0805")
      (fields (field (name "LCSC_PART") "C17513"))
      (libsource (lib "eagle-import") (part "1K-1%0805"))
    )
    (comp (ref "R51")
      (value "0.002R 1%")
      (footprint "eagle-import:2512")
      (fields (field (name "LCSC_PART") "C728320"))
      (libsource (lib "eagle-import") (part "0.002R-1%2512"))
    )
    (comp (ref "R52")
      (value "470K 1%")
      (footprint "eagle-import:0805")
      (fields (field (name "LCSC_PART") "C17709"))
      (libsource (lib "eagle-import") (part "470K-1%0805"))
    )
    (comp (ref "R53")
      (value "470K 1%")
      (footprint "eagle-import:0805")
      (fields (field (name "LCSC_PART") "C17709"))
      (libsource (lib "eagle-import") (part "470K-1%0805"))
    )
    (comp (ref "R54")
      (value "470K 1%")
      (footprint "eagle-import:0805")
      (fields (field (name "LCSC_PART") "C17709"))
      (libsource (lib "eagle-import") (part "470K-1%0805"))
    )
    (comp (ref "R55")
      (value "470K 1%")
      (footprint "eagle-import:0805")
      (fields (field (name "LCSC_PART") "C17709"))
      (libsource (lib "eagle-import") (part "470K-1%0805"))
    )
    (comp (ref "R56")
      (value "1K 1%")
      (footprint "eagle-import:0805")
      (fields (field (name "LCSC_PART") "C17513"))
      (libsource (lib "eagle-import") (part "1K-1%0805"))
    )
    (comp (ref "R65")
      (value "1K 1%")
      (footprint "eagle-import:0805")
      (fields (field (name "LCSC_PART") "C17513"))
      (libsource (lib "eagle-import") (part "1K-1%0805"))
    )
    (comp (ref "R66")
      (value "1K 1%")
      (footprint "eagle-import:0805")
      (fields (field (name "LCSC_PART") "C17513"))
      (libsource (lib "eagle-import") (part "1K-1%0805"))
    )
    (comp (ref "R67")
      (value "0.002R 1%")
      (footprint "eagle-import:2512")
      (fields (field (name "LCSC_PART") "C728320"))
      (libsource (lib "eagle-import") (part "0.002R-1%2512"))
    )
    (comp (ref "R68")
      (value "470K 1%")
      (footprint "eagle-import:0805")
      (fields (field (name "LCSC_PART") "C17709"))
      (libsource (lib "eagle-import") (part "470K-1%0805"))
    )
    (comp (ref "R69")
      (value "470K 1%")
      (footprint "eagle-import:0805")
      (fields (field (name "LCSC_PART") "C17709"))
      (libsource (lib "eagle-import") (part "470K-1%0805"))
    )
    (comp (ref "R70")
      (value "470K 1%")
      (footprint "eagle-import:0805")
      (fields (field (name "LCSC_PART") "C17709"))
      (libsource (lib "eagle-import") (part "470K-1%0805"))
    )
    (comp (ref "R71")
      (value "470K 1%")
      (footprint "eagle-import:0805")
      (fields (field (name "LCSC_PART") "C17709"))
      (libsource (lib "eagle-import") (part "470K-1%0805"))
    )
    (comp (ref "R72")
      (value "1K 1%")
      (footprint "eagle-import:0805")
      (fields (field (name "LCSC_PART") "C17513"))
      (libsource (lib "eagle-import") (part "1K-1%0805"))
    )
    (comp (ref "R73")
      (value "1K 1%")
      (footprint "eagle-import:0805")
      (fields (field (name "LCSC_PART") "C17513"))
      (libsource (lib "eagle-import") (part "1K-1%0805"))
    )
    (comp (ref "R74")
      (value "1K 1%")
      (footprint "eagle-import:0805")
      (fields (field (name "LCSC_PART") "C17513"))
      (libsource (lib "eagle-import") (part "1K-1%0805"))
    )
    (comp (ref "R75")
      (value "0.002R 1%")
      (footprint "eagle-import:2512")
      (fields (field (name "LCSC_PART") "C728320"))
      (libsource (lib "eagle-import") (part "0.002R-1%2512"))
    )
    (comp (ref "R76")
      (value "470K 1%")
      (footprint "eagle-import:0805")
      (fields (field (name "LCSC_PART") "C17709"))
      (libsource (lib "eagle-import") (part "470K-1%0805"))
    )
    (comp (ref "R77")
      (value "470K 1%")
      (footprint "eagle-import:0805")
      (fields (field (name "LCSC_PART") "C17709"))
      (libsource (lib "eagle-import") (part "470K-1%0805"))
    )
    (comp (ref "R78")
      (value "470K 1%")
      (footprint "eagle-import:0805")
      (fields (field (name "LCSC_PART") "C17709"))
      (libsource (lib "eagle-import") (part "470K-1%0805"))
    )
    (comp (ref "R79")
      (value "470K 1%")
      (footprint "eagle-import:0805")
      (fields (field (name "LCSC_PART") "C17709"))
      (libsource (lib "eagle-import") (part "470K-1%0805"))
    )
    (comp (ref "R80")
      (value "1K 1%")
      (footprint "eagle-import:0805")
      (fields (field (name "LCSC_PART") "C17513"))
      (libsource (lib "eagle-import") (part "1K-1%0805"))
    )
    (comp (ref "R81")
      (value "1K 1%")
      (footprint "eagle-import:0805")
      (fields (field (name "LCSC_PART") "C17513"))
      (libsource (lib "eagle-import") (part "1K-1%0805"))
    )
    (comp (ref "R82")
      (value "1K 1%")
      (footprint "eagle-import:0805")
      (fields (field (name "LCSC_PART") "C17513"))
      (libsource (lib "eagle-import") (part "1K-1%0805"))
    )
    (comp (ref "R83")
      (value "0.002R 1%")
      (footprint "eagle-import:2512")
      (fields (field (name "LCSC_PART") "C728320"))
      (libsource (lib "eagle-import") (part "0.002R-1%2512"))
    )
    (comp (ref "R84")
      (value "470K 1%")
      (footprint "eagle-import:0805")
      (fields (field (name "LCSC_PART") "C17709"))
      (libsource (lib "eagle-import") (part "470K-1%0805"))
    )
    (comp (ref "R85")
      (value "470K 1%")
      (footprint "eagle-import:0805")
      (fields (field (name "LCSC_PART") "C17709"))
      (libsource (lib "eagle-import") (part "470K-1%0805"))
    )
    (comp (ref "R86")
      (value "470K 1%")
      (footprint "eagle-import:0805")
      (fields (field (name "LCSC_PART") "C17709"))
      (libsource (lib "eagle-import") (part "470K-1%0805"))
    )
    (comp (ref "R87")
      (value "470K 1%")
      (footprint "eagle-import:0805")
      (fields (field (name "LCSC_PART") "C17709"))
      (libsource (lib "eagle-import") (part "470K-1%0805"))
    )
    (comp (ref "R88")
      (value "1K 1%")
      (footprint "eagle-import:0805")
      (fields (field (name "LCSC_PART") "C17513"))
      (libsource (lib "eagle-import") (part "1K-1%0805"))
    )
    (comp (ref "R97")
      (value "1K 1%")
      (footprint "eagle-import:0805")
      (fields (field (name "LCSC_PART") "C17513"))
      (libsource (lib "eagle-import") (part "1K-1%0805"))
    )
    (comp (ref "R98")
      (value "1K 1%")
      (footprint "eagle-import:0805")
      (fields (field (name "LCSC_PART") "C17513"))
      (libsource (lib "eagle-import") (part "1K-1%0805"))
    )
    (comp (ref "R99")
      (value "0.002R 1%")
      (footprint "eagle-import:2512")
      (fields (field (name "LCSC_PART") "C728320"))
      (libsource (lib "eagle-import") (part "0.002R-1%2512"))
    )
    (comp (ref "R100")
      (value "470K 1%")
      (footprint "eagle-import:0805")
      (fields (field (name "LCSC_PART") "C17709"))
      (libsource (lib "eagle-import") (part "470K-1%0805"))
    )
    (comp (ref "R101")
      (value "470K 1%")
      (footprint "eagle-import:0805")
      (fields (field (name "LCSC_PART") "C17709"))
      (libsource (lib "eagle-import") (part "470K-1%0805"))
    )
    (comp (ref "R102")
      (value "470K 1%")
      (footprint "eagle-import:0805")
      (fields (field (name "LCSC_PART") "C17709"))
      (libsource (lib "eagle-import") (part "470K-1%0805"))
    )
    (comp (ref "R103")
      (value "470K 1%")
      (footprint "eagle-import:0805")
      (fields (field (name "LCSC_PART") "C17709"))
      (libsource (lib "eagle-import") (part "470K-1%0805"))
    )
    (comp (ref "R104")
      (value "1K 1%")
      (footprint "eagle-import:0805")
      (fields (field (name "LCSC_PART") "C17513"))
      (libsource (lib "eagle-import") (part "1K-1%0805"))
    )
    (comp (ref "R113")
      (value "1K 1%")
      (footprint "eagle-import:0805")
      (fields (field (name "LCSC_PART") "C17513"))
      (libsource (lib "eagle-import") (part "1K-1%0805"))
    )
    (comp (ref "R114")
      (value "1K 1%")
      (footprint "eagle-import:0805")
      (fields (field (name "LCSC_PART") "C17513"))
      (libsource (lib "eagle-import") (part "1K-1%0805"))
    )
    (comp (ref "R115")
      (value "0.002R 1%")
      (footprint "eagle-import:2512")
      (fields (field (name "LCSC_PART") "C728320"))
      (libsource (lib "eagle-import") (part "0.002R-1%2512"))
    )
    (comp (ref "R116")
      (value "470K 1%")
      (footprint "eagle-import:0805")
      (fields (field (name "LCSC_PART") "C17709"))
      (libsource (lib "eagle-import") (part "470K-1%0805"))
    )
    (comp (ref "R117")
      (value "470K 1%")
      (footprint "eagle-import:0805")
      (fields (field (name "LCSC_PART") "C17709"))
      (libsource (lib "eagle-import") (part "470K-1%0805"))
    )
    (comp (ref "R118")
      (value "470K 1%")
      (footprint "eagle-import:0805")
      (fields (field (name "LCSC_PART") "C17709"))
      (libsource (lib "eagle-import") (part "470K-1%0805"))
    )
    (comp (ref "R119")
      (value "470K 1%")
      (footprint "eagle-import:0805")
      (fields (field (name "LCSC_PART") "C17709"))
      (libsource (lib "eagle-import") (part "470K-1%0805"))
    )
    (comp (ref "R120")
      (value "1K 1%")
      (footprint "eagle-import:0805")
      (fields (field (name "LCSC_PART") "C17513"))
      (libsource (lib "eagle-import") (part "1K-1%0805"))
    )
    (comp (ref "AVDD")
      (value "TP")
      (footprint "eagle-import:TP")
      (libsource (lib "eagle-import") (part "TP"))
    )
    (comp (ref "C60")
      (value "1uF 25V")
      (footprint "eagle-import:0402")
      (fields (field (name "LCSC_PART") "C52923"))
      (libsource (lib "eagle-import") (part "1UF-25V0402"))
    )
    (comp (ref "C61")
      (value "100nF 25V")
      (footprint "eagle-import:0201")
      (fields (field (name "LCSC_PART") "C76939"))
      (libsource (lib "eagle-import") (part "100NF-25V-0201"))
    )
    (comp (ref "C62")
      (value "100nF 25V")
      (footprint "eagle-import:0201")
      (fields (field (name "LCSC_PART") "C76939"))
      (libsource (lib "eagle-import") (part "100NF-25V-0201"))
    )
    (comp (ref "C63")
      (value "100nF 25V")
      (footprint "eagle-import:0201")
      (fields (field (name "LCSC_PART") "C76939"))
      (libsource (lib "eagle-import") (part "100NF-25V-0201"))
    )
    (comp (ref "C65")
      (value "10uF 50V")
      (footprint "eagle-import:0805")
      (fields (field (name "LCSC_PART") "C440198"))
      (libsource (lib "eagle-import") (part "10UF-50V-0805"))
    )
    (comp (ref "C66")
      (value "100nF 25V")
      (footprint "eagle-import:0402")
      (fields (field (name "LCSC_PART") "C56392"))
      (libsource (lib "eagle-import") (part "100NF-25V-0402"))
    )
    (comp (ref "C78")
      (value "4.7nF 50V")
      (footprint "eagle-import:0402")
      (fields (field (name "LCSC_PART") "C1538"))
      (libsource (lib "eagle-import") (part "4.7NF-50V0402"))
    )
    (comp (ref "C97")
      (value "10uF 50V")
      (footprint "eagle-import:0805")
      (fields (field (name "LCSC_PART") "C440198"))
      (libsource (lib "eagle-import") (part "10UF-50V-0805"))
    )
    (comp (ref "C98")
      (value "100nF 25V")
      (footprint "eagle-import:0201")
      (fields (field (name "LCSC_PART") "C76939"))
      (libsource (lib "eagle-import") (part "100NF-25V-0201"))
    )
    (comp (ref "C99")
      (value "10uF 50V")
      (footprint "eagle-import:0805")
      (fields (field (name "LCSC_PART") "C440198"))
      (libsource (lib "eagle-import") (part "10UF-50V-0805"))
    )
    (comp (ref "C100")
      (value "100nF 25V")
      (footprint "eagle-import:0201")
      (fields (field (name "LCSC_PART") "C76939"))
      (libsource (lib "eagle-import") (part "100NF-25V-0201"))
    )
    (comp (ref "C102")
      (value "1uF 16V")
      (footprint "eagle-import:0201")
      (fields (field (name "LCSC_PART") "C307385"))
      (libsource (lib "eagle-import") (part "1UF-16V0201"))
    )
    (comp (ref "C104")
      (value "1uF 25V")
      (footprint "eagle-import:0402")
      (fields (field (name "LCSC_PART") "C52923"))
      (libsource (lib "eagle-import") (part "1UF-25V0402"))
    )
    (comp (ref "D15")
      (value "SS12")
      (footprint "eagle-import:SMA_DO-214AC")
      (fields (field (name "LCSC_PART") "C727049"))
      (libsource (lib "eagle-import") (part "SS12"))
    )
    (comp (ref "DSP")
      (value "AFC11-S20ICC-00")
      (footprint "eagle-import:FPC20")
      (fields (field (name "LCSC_PART") "C11073"))
      (libsource (lib "eagle-import") (part "AFC11-S20ICC-00"))
    )
    (comp (ref "ESD1")
      (value "SP0503BAHTG")
      (footprint "eagle-import:SOT143")
      (fields (field (name "LCSC_PART") "C3040626"))
      (libsource (lib "eagle-import") (part "SP0503BAHT"))
    )
    (comp (ref "IC17")
      (value "MCP6001RT-I/OT")
      (footprint "eagle-import:SOT23-5")
      (fields (field (name "LCSC_PART") "C154973"))
      (libsource (lib "eagle-import") (part "MCP6001RT"))
    )
    (comp (ref "IC21")
      (value "MIC5504-3.3YM5")
      (footprint "eagle-import:SOT23-5")
      (fields (field (name "LCSC_PART") "C41348078"))
      (libsource (lib "eagle-import") (part "MIC5504-3.3YM5-TR"))
    )
    (comp (ref "PWR")
      (value "Green")
      (footprint "eagle-import:LED-0603")
      (fields (field (name "LCSC_PART") "C965804"))
      (libsource (lib "eagle-import") (part "LED-GREENLED-0603"))
    )
    (comp (ref "R109")
      (value "4.7K 1%")
      (footprint "eagle-import:0201")
      (fields (field (name "LCSC_PART") "C270346"))
      (libsource (lib "eagle-import") (part "4.7K-1%0201"))
    )
    (comp (ref "R121")
      (value "2.2K 1%")
      (footprint "eagle-import:0201")
      (fields (field (name "LCSC_PART") "C473508"))
      (libsource (lib "eagle-import") (part "2.2K-1%0201"))
    )
    (comp (ref "R124")
      (value "5.1K 1%")
      (footprint "eagle-import:0201")
      (fields (field (name "LCSC_PART") "C274341"))
      (libsource (lib "eagle-import") (part "5.1K-1%0201"))
    )
    (comp (ref "R125")
      (value "5.1K 1%")
      (footprint "eagle-import:0201")
      (fields (field (name "LCSC_PART") "C274341"))
      (libsource (lib "eagle-import") (part "5.1K-1%0201"))
    )
    (comp (ref "R126")
      (value "10K 1%")
      (footprint "eagle-import:0201")
      (fields (field (name "LCSC_PART") "C473048"))
      (libsource (lib "eagle-import") (part "10K-1%0201"))
    )
    (comp (ref "R127")
      (value "10K 1%")
      (footprint "eagle-import:0201")
      (fields (field (name "LCSC_PART") "C473048"))
      (libsource (lib "eagle-import") (part "10K-1%0201"))
    )
    (comp (ref "R131")
      (value "1M 1%")
      (footprint "eagle-import:0402")
      (fields (field (name "LCSC_PART") "C26083"))
      (libsource (lib "eagle-import") (part "1M-1%0402"))
    )
    (comp (ref "R147")
      (value "10K 1%")
      (footprint "eagle-import:0402")
      (fields (field (name "LCSC_PART") "C25744"))
      (libsource (lib "eagle-import") (part "10K-1%0402"))
    )
    (comp (ref "R149")
      (value "3.3K 1%")
      (footprint "eagle-import:_0603X4-1206")
      (fields (field (name "LCSC_PART") "C1734380"))
      (libsource (lib "eagle-import") (part "3.3K-1%_ARRAY0603X4-1206"))
    )
    (comp (ref "R151")
      (value "1K 1%")
      (footprint "eagle-import:0402")
      (fields (field (name "LCSC_PART") "C11702"))
      (libsource (lib "eagle-import") (part "1K-1%0402"))
    )
    (comp (ref "R152")
      (value "10R 1%")
      (footprint "eagle-import:0201")
      (fields (field (name "LCSC_PART") "C270817"))
      (libsource (lib "eagle-import") (part "10R-1%0201"))
    )
    (comp (ref "REF1")
      (value "LM4040B30FTA")
      (footprint "eagle-import:SOT23")
      (fields (field (name "LCSC_PART") "C460604"))
      (libsource (lib "eagle-import") (part "LM4040BXX"))
    )
    (comp (ref "USB1")
      (value "USB-TYPE-C-018")
      (footprint "eagle-import:USB-C")
      (fields (field (name "LCSC_PART") "C2927038"))
      (libsource (lib "eagle-import") (part "USB_C-THT"))
    )
    (comp (ref "VBUS")
      (value "TP")
      (footprint "eagle-import:TP")
      (libsource (lib "eagle-import") (part "TP"))
    )
    (comp (ref "VREF")
      (value "TP")
      (footprint "eagle-import:TP")
      (libsource (lib "eagle-import") (part "TP"))
    )
  )
  (nets
    (net (code "1") (name "+1V1") (class "Default")
      (node (ref "C75") (pin "1") (pinfunction "1_1") (pintype "passive"))
      (node (ref "C76") (pin "1") (pinfunction "1_1") (pintype "passive"))
      (node (ref "C77") (pin "1") (pinfunction "1_1") (pintype "passive"))
      (node (ref "DVDD") (pin "TP") (pinfunction "P$1_TP") (pintype "bidirectional"))
      (node (ref "IC15") (pin "23") (pinfunction "DVDD_23") (pintype "bidirectional"))
      (node (ref "IC15") (pin "45") (pinfunction "VREG_VOUT_45") (pintype "bidirectional"))
      (node (ref "IC15") (pin "50") (pinfunction "DVDD_50") (pintype "bidirectional"))
    )
    (net (code "2") (name "+3V3") (class "Default")
      (node (ref "3VDC") (pin "TP") (pinfunction "P$1_TP") (pintype "bidirectional"))
      (node (ref "C103") (pin "1") (pinfunction "1_1") (pintype "passive"))
      (node (ref "C12") (pin "1") (pinfunction "1_1") (pintype "passive"))
      (node (ref "C15") (pin "1") (pinfunction "1_1") (pintype "passive"))
      (node (ref "C18") (pin "1") (pinfunction "1_1") (pintype "passive"))
      (node (ref "C19") (pin "1") (pinfunction "1_1") (pintype "passive"))
      (node (ref "C20") (pin "1") (pinfunction "1_1") (pintype "passive"))
      (node (ref "C33") (pin "1") (pinfunction "1_1") (pintype "passive"))
      (node (ref "C34") (pin "1") (pinfunction "1_1") (pintype "passive"))
      (node (ref "C88") (pin "1") (pinfunction "1_1") (pintype "passive"))
      (node (ref "C89") (pin "1") (pinfunction "1_1") (pintype "passive"))
      (node (ref "C90") (pin "1") (pinfunction "1_1") (pintype "passive"))
      (node (ref "DSP") (pin "1") (pinfunction "1_1") (pintype "bidirectional"))
      (node (ref "DSP") (pin "2") (pinfunction "2_2") (pintype "bidirectional"))
      (node (ref "ETH1") (pin "10") (pinfunction "GREEN+_10") (pintype "passive"))
      (node (ref "ETH1") (pin "12") (pinfunction "YELLOW+_12") (pintype "passive"))
      (node (ref "IC20") (pin "28") (pinfunction "VDD_28") (pintype "power_in"))
      (node (ref "IC20") (pin "43") (pinfunction "PMODE2_43") (pintype "input"))
      (node (ref "IC20") (pin "44") (pinfunction "PMODE1_44") (pintype "input"))
      (node (ref "IC20") (pin "45") (pinfunction "PMODE0_45") (pintype "input"))
      (node (ref "IC22") (pin "2") (pinfunction "V+_2") (pintype "power_in"))
      (node (ref "IC4") (pin "5") (pinfunction "VDD_5") (pintype "bidirectional"))
      (node (ref "IC9") (pin "16") (pinfunction "VCC_16") (pintype "power_in"))
      (node (ref "L2") (pin "2") (pinfunction "2_2") (pintype "passive"))
      (node (ref "L4") (pin "1") (pinfunction "1_1") (pintype "passive"))
      (node (ref "R123") (pin "1") (pinfunction "1_1") (pintype "passive"))
      (node (ref "R13") (pin "1") (pinfunction "1_1") (pintype "passive"))
      (node (ref "R145") (pin "2") (pinfunction "2_2") (pintype "passive"))
      (node (ref "R147") (pin "2") (pinfunction "2_2") (pintype "passive"))
      (node (ref "R149") (pin "A1") (pinfunction "1_A1") (pintype "passive"))
      (node (ref "R149") (pin "B1") (pinfunction "2_B1") (pintype "passive"))
      (node (ref "R149") (pin "C1") (pinfunction "3_C1") (pintype "passive"))
      (node (ref "R149") (pin "D1") (pinfunction "4_D1") (pintype "passive"))
      (node (ref "R89") (pin "A2") (pinfunction "8_A2") (pintype "passive"))
      (node (ref "R89") (pin "B2") (pinfunction "7_B2") (pintype "passive"))
      (node (ref "R89") (pin "C2") (pinfunction "6_C2") (pintype "passive"))
      (node (ref "R89") (pin "D2") (pinfunction "5_D2") (pintype "passive"))
      (node (ref "R90") (pin "A2") (pinfunction "8_A2") (pintype "passive"))
      (node (ref "R90") (pin "B2") (pinfunction "7_B2") (pintype "passive"))
      (node (ref "R90") (pin "C2") (pinfunction "6_C2") (pintype "passive"))
      (node (ref "R90") (pin "D2") (pinfunction "5_D2") (pintype "passive"))
    )
    (net (code "3") (name "+3V3_A") (class "Default")
      (node (ref "C91") (pin "1") (pinfunction "1_1") (pintype "passive"))
      (node (ref "C92") (pin "1") (pinfunction "1_1") (pintype "passive"))
      (node (ref "C93") (pin "1") (pinfunction "1_1") (pintype "passive"))
      (node (ref "C94") (pin "1") (pinfunction "1_1") (pintype "passive"))
      (node (ref "C95") (pin "1") (pinfunction "1_1") (pintype "passive"))
      (node (ref "C96") (pin "1") (pinfunction "1_1") (pintype "passive"))
      (node (ref "IC20") (pin "11") (pinfunction "AVDD_11") (pintype "power_in"))
      (node (ref "IC20") (pin "15") (pinfunction "AVDD_15") (pintype "power_in"))
      (node (ref "IC20") (pin "17") (pinfunction "AVDD_17") (pintype "power_in"))
      (node (ref "IC20") (pin "21") (pinfunction "AVDD_21") (pintype "power_in"))
      (node (ref "IC20") (pin "4") (pinfunction "AVDD_4") (pintype "power_in"))
      (node (ref "IC20") (pin "8") (pinfunction "AVDD_8") (pintype "power_in"))
      (node (ref "L4") (pin "2") (pinfunction "2_2") (pintype "passive"))
      (node (ref "R139") (pin "2") (pinfunction "2_2") (pintype "passive"))
      (node (ref "R140") (pin "2") (pinfunction "2_2") (pintype "passive"))
      (node (ref "R146") (pin "2") (pinfunction "2_2") (pintype "passive"))
    )
    (net (code "4") (name "+3V3_MCU") (class "Default")
      (node (ref "C100") (pin "1") (pinfunction "1_1") (pintype "passive"))
      (node (ref "C101") (pin "1") (pinfunction "1_1") (pintype "passive"))
      (node (ref "C104") (pin "1") (pinfunction "1_1") (pintype "passive"))
      (node (ref "C64") (pin "1") (pinfunction "1_1") (pintype "passive"))
      (node (ref "C67") (pin "1") (pinfunction "1_1") (pintype "passive"))
      (node (ref "C68") (pin "1") (pinfunction "1_1") (pintype "passive"))
      (node (ref "C69") (pin "1") (pinfunction "1_1") (pintype "passive"))
      (node (ref "C70") (pin "1") (pinfunction "1_1") (pintype "passive"))
      (node (ref "C71") (pin "1") (pinfunction "1_1") (pintype "passive"))
      (node (ref "C72") (pin "1") (pinfunction "1_1") (pintype "passive"))
      (node (ref "C73") (pin "1") (pinfunction "1_1") (pintype "passive"))
      (node (ref "C99") (pin "1") (pinfunction "1_1") (pintype "passive"))
      (node (ref "IC15") (pin "1") (pinfunction "IOVDD_1") (pintype "bidirectional"))
      (node (ref "IC15") (pin "10") (pinfunction "IOVDD_10") (pintype "bidirectional"))
      (node (ref "IC15") (pin "22") (pinfunction "IOVDD_22") (pintype "bidirectional"))
      (node (ref "IC15") (pin "33") (pinfunction "IOVDD_33") (pintype "bidirectional"))
      (node (ref "IC15") (pin "42") (pinfunction "IOVDD_42") (pintype "bidirectional"))
      (node (ref "IC15") (pin "44") (pinfunction "VREG_VIN_44") (pintype "bidirectional"))
      (node (ref "IC15") (pin "48") (pinfunction "USB_VDD_48") (pintype "bidirectional"))
      (node (ref "IC15") (pin "49") (pinfunction "IOVDD_49") (pintype "bidirectional"))
      (node (ref "IC18") (pin "8") (pinfunction "VCC_8") (pintype "power_in"))
      (node (ref "IC19") (pin "8") (pinfunction "VCC_8") (pintype "power_in"))
      (node (ref "IC21") (pin "5") (pinfunction "VOUT_5") (pintype "bidirectional"))
      (node (ref "IOVDD") (pin "TP") (pinfunction "P$1_TP") (pintype "bidirectional"))
      (node (ref "PWR") (pin "A") (pinfunction "A_A") (pintype "passive"))
      (node (ref "R109") (pin "2") (pinfunction "2_2") (pintype "passive"))
      (node (ref "R111") (pin "2") (pinfunction "2_2") (pintype "passive"))
      (node (ref "R128") (pin "2") (pinfunction "2_2") (pintype "passive"))
      (node (ref "R130") (pin "A2") (pinfunction "8_A2") (pintype "passive"))
      (node (ref "R130") (pin "B2") (pinfunction "7_B2") (pintype "passive"))
      (node (ref "R130") (pin "C2") (pinfunction "6_C2") (pintype "passive"))
      (node (ref "R130") (pin "D2") (pinfunction "5_D2") (pintype "passive"))
      (node (ref "R132") (pin "1") (pinfunction "1_1") (pintype "passive"))
      (node (ref "R152") (pin "1") (pinfunction "1_1") (pintype "passive"))
      (node (ref "R165") (pin "2") (pinfunction "2_2") (pintype "passive"))
    )
    (net (code "5") (name "+5V") (class "Default")
      (node (ref "5VDC") (pin "TP") (pinfunction "P$1_TP") (pintype "bidirectional"))
      (node (ref "C11") (pin "1") (pinfunction "1_1") (pintype "passive"))
      (node (ref "C14") (pin "1") (pinfunction "1_1") (pintype "passive"))
      (node (ref "C17") (pin "1") (pinfunction "1_1") (pintype "passive"))
      (node (ref "D15") (pin "A") (pinfunction "A_A") (pintype "passive"))
      (node (ref "DSP") (pin "3") (pinfunction "3_3") (pintype "bidirectional"))
      (node (ref "DSP") (pin "4") (pinfunction "4_4") (pintype "bidirectional"))
      (node (ref "L1") (pin "2") (pinfunction "2_2") (pintype "passive"))
      (node (ref "R11") (pin "1") (pinfunction "1_1") (pintype "passive"))
      (node (ref "R148") (pin "1") (pinfunction "1_1") (pintype "passive"))
    )
    (net (code "6") (name "+5V_MEA") (class "Default")
      (node (ref "IC10") (pin "1") (pinfunction "VDD_1") (pintype "power_in"))
      (node (ref "IC11") (pin "1") (pinfunction "VDD_1") (pintype "power_in"))
      (node (ref "IC12") (pin "1") (pinfunction "VDD_1") (pintype "power_in"))
      (node (ref "IC14") (pin "1") (pinfunction "VDD_1") (pintype "power_in"))
      (node (ref "IC16") (pin "1") (pinfunction "VDD_1") (pintype "power_in"))
      (node (ref "IC6") (pin "1") (pinfunction "VDD_1") (pintype "power_in"))
      (node (ref "IC7") (pin "1") (pinfunction "VDD_1") (pintype "power_in"))
      (node (ref "IC8") (pin "1") (pinfunction "VDD_1") (pintype "power_in"))
      (node (ref "J2") (pin "2") (pinfunction "2_2") (pintype "passive"))
      (node (ref "J7") (pin "2") (pinfunction "2_2") (pintype "passive"))
      (node (ref "R63") (pin "A1") (pinfunction "1_A1") (pintype "passive"))
      (node (ref "R63") (pin "B1") (pinfunction "2_B1") (pintype "passive"))
      (node (ref "R63") (pin "C1") (pinfunction "3_C1") (pintype "passive"))
      (node (ref "R63") (pin "D1") (pinfunction "4_D1") (pintype "passive"))
      (node (ref "R64") (pin "A1") (pinfunction "1_A1") (pintype "passive"))
      (node (ref "R64") (pin "B1") (pinfunction "2_B1") (pintype "passive"))
      (node (ref "R64") (pin "C1") (pinfunction "3_C1") (pintype "passive"))
      (node (ref "R64") (pin "D1") (pinfunction "4_D1") (pintype "passive"))
    )
    (net (code "7") (name "+5V_MEA1") (class "Default")
      (node (ref "5V-NI1") (pin "TP") (pinfunction "P$1_TP") (pintype "bidirectional"))
      (node (ref "C23") (pin "1") (pinfunction "+_1") (pintype "passive"))
      (node (ref "C45") (pin "2") (pinfunction "2_2") (pintype "passive"))
      (node (ref "D9") (pin "A") (pinfunction "A_A") (pintype "passive"))
      (node (ref "J2") (pin "1") (pinfunction "1_1") (pintype "passive"))
      (node (ref "L3") (pin "2") (pinfunction "2_2") (pintype "passive"))
      (node (ref "R96") (pin "1") (pinfunction "1_1") (pintype "passive"))
    )
    (net (code "8") (name "+5V_MEA2") (class "Default")
      (node (ref "5V-NI2") (pin "TP") (pinfunction "P$1_TP") (pintype "bidirectional"))
      (node (ref "C53") (pin "1") (pinfunction "+_1") (pintype "passive"))
      (node (ref "C57") (pin "2") (pinfunction "2_2") (pintype "passive"))
      (node (ref "D13") (pin "A") (pinfunction "A_A") (pintype "passive"))
      (node (ref "J7") (pin "1") (pinfunction "1_1") (pintype "passive"))
      (node (ref "L5") (pin "2") (pinfunction "2_2") (pintype "passive"))
      (node (ref "R108") (pin "1") (pinfunction "1_1") (pintype "passive"))
    )
    (net (code "9") (name "+12V") (class "Default")
      (node (ref "C1") (pin "1") (pinfunction "1_1") (pintype "passive"))
      (node (ref "C2") (pin "1") (pinfunction "1_1") (pintype "passive"))
      (node (ref "C3") (pin "1") (pinfunction "1_1") (pintype "passive"))
      (node (ref "C4") (pin "1") (pinfunction "1_1") (pintype "passive"))
      (node (ref "D1") (pin "C") (pinfunction "C_C") (pintype "passive"))
      (node (ref "D2") (pin "C") (pinfunction "C_C") (pintype "passive"))
      (node (ref "D3") (pin "C") (pinfunction "C_C") (pintype "passive"))
      (node (ref "D4") (pin "C") (pinfunction "C_C") (pintype "passive"))
      (node (ref "D5") (pin "C") (pinfunction "C_C") (pintype "passive"))
      (node (ref "D6") (pin "C") (pinfunction "C_C") (pintype "passive"))
      (node (ref "D7") (pin "C") (pinfunction "C_C") (pintype "passive"))
      (node (ref "D8") (pin "C") (pinfunction "C_C") (pintype "passive"))
      (node (ref "FAN") (pin "2") (pinfunction "2_2") (pintype "passive"))
      (node (ref "IC1") (pin "2") (pinfunction "IN_2") (pintype "bidirectional"))
      (node (ref "IC2") (pin "2") (pinfunction "IN_2") (pintype "bidirectional"))
      (node (ref "IC3") (pin "10") (pinfunction "COM_10") (pintype "bidirectional"))
      (node (ref "J10") (pin "1") (pinfunction "1_1") (pintype "passive"))
      (node (ref "J8") (pin "1") (pinfunction "1_1") (pintype "passive"))
      (node (ref "J9") (pin "1") (pinfunction "1_1") (pintype "passive"))
      (node (ref "K1") (pin "8") (pinfunction "8_8") (pintype "passive"))
      (node (ref "K2") (pin "8") (pinfunction "8_8") (pintype "passive"))
      (node (ref "K3") (pin "8") (pinfunction "8_8") (pintype "passive"))
      (node (ref "K4") (pin "8") (pinfunction "8_8") (pintype "passive"))
      (node (ref "K5") (pin "8") (pinfunction "8_8") (pintype "passive"))
      (node (ref "K6") (pin "8") (pinfunction "8_8") (pintype "passive"))
      (node (ref "K7") (pin "8") (pinfunction "8_8") (pintype "passive"))
      (node (ref "K8") (pin "8") (pinfunction "8_8") (pintype "passive"))
      (node (ref "R150") (pin "1") (pinfunction "1_1") (pintype "passive"))
      (node (ref "R162") (pin "2") (pinfunction "2_2") (pintype "passive"))
      (node (ref "R94") (pin "2") (pinfunction "2_2") (pintype "passive"))
    )
    (net (code "10") (name "+12V_MEA") (class "Default")
      (node (ref "IC15") (pin "41") (pinfunction "GPIO29/ADC3_41") (pintype "bidirectional"))
      (node (ref "R94") (pin "1") (pinfunction "1_1") (pintype "passive"))
      (node (ref "R95") (pin "2") (pinfunction "2_2") (pintype "passive"))
    )
    (net (code "11") (name "5V_EN") (class "Default")
      (node (ref "IC1") (pin "6") (pinfunction "EN_6") (pintype "bidirectional"))
      (node (ref "R1") (pin "1") (pinfunction "1_1") (pintype "passive"))
      (node (ref "R161") (pin "2") (pinfunction "2_2") (pintype "passive"))
      (node (ref "R162") (pin "1") (pinfunction "1_1") (pintype "passive"))
    )
    (net (code "12") (name "AC_L") (class "Default")
      (node (ref "AC/DC1") (pin "AC_L") (pinfunction "AC/L_AC_L") (pintype "input"))
      (node (ref "AC/DC2") (pin "AC/L") (pinfunction "AC/L_AC/L") (pintype "input"))
      (node (ref "AC_L") (pin "B3,0") (pinfunction "MOUNT_B3,0") (pintype "passive"))
      (node (ref "K1") (pin "3") (pinfunction "3_3") (pintype "passive"))
      (node (ref "K1") (pin "6") (pinfunction "6_6") (pintype "passive"))
      (node (ref "K2") (pin "3") (pinfunction "3_3") (pintype "passive"))
      (node (ref "K2") (pin "6") (pinfunction "6_6") (pintype "passive"))
      (node (ref "K3") (pin "3") (pinfunction "3_3") (pintype "passive"))
      (node (ref "K3") (pin "6") (pinfunction "6_6") (pintype "passive"))
      (node (ref "K4") (pin "3") (pinfunction "3_3") (pintype "passive"))
      (node (ref "K4") (pin "6") (pinfunction "6_6") (pintype "passive"))
      (node (ref "K5") (pin "3") (pinfunction "3_3") (pintype "passive"))
      (node (ref "K5") (pin "6") (pinfunction "6_6") (pintype "passive"))
      (node (ref "K6") (pin "3") (pinfunction "3_3") (pintype "passive"))
      (node (ref "K6") (pin "6") (pinfunction "6_6") (pintype "passive"))
      (node (ref "K7") (pin "3") (pinfunction "3_3") (pintype "passive"))
      (node (ref "K7") (pin "6") (pinfunction "6_6") (pintype "passive"))
      (node (ref "K8") (pin "3") (pinfunction "3_3") (pintype "passive"))
      (node (ref "K8") (pin "6") (pinfunction "6_6") (pintype "passive"))
      (node (ref "R106") (pin "1") (pinfunction "1_1") (pintype "passive"))
      (node (ref "R62") (pin "1") (pinfunction "1_1") (pintype "passive"))
    )
    (net (code "13") (name "ADC_V_USB") (class "Default")
      (node (ref "IC15") (pin "38") (pinfunction "GPIO26/ADC0_38") (pintype "bidirectional"))
      (node (ref "R126") (pin "2") (pinfunction "2_2") (pintype "passive"))
      (node (ref "R127") (pin "1") (pinfunction "1_1") (pintype "passive"))
    )
    (net (code "14") (name "AGND") (class "Default")
      (node (ref "AC/DC1") (pin "AC_N") (pinfunction "AC/N_AC_N") (pintype "input"))
      (node (ref "AC/DC2") (pin "AC/N") (pinfunction "AC/N_AC/N") (pintype "input"))
      (node (ref "AC_N") (pin "B3,0") (pinfunction "MOUNT_B3,0") (pintype "passive"))
      (node (ref "C106") (pin "2") (pinfunction "2_2") (pintype "passive"))
      (node (ref "C107") (pin "2") (pinfunction "2_2") (pintype "passive"))
      (node (ref "C108") (pin "2") (pinfunction "2_2") (pintype "passive"))
      (node (ref "C109") (pin "2") (pinfunction "2_2") (pintype "passive"))
      (node (ref "C110") (pin "2") (pinfunction "2_2") (pintype "passive"))
      (node (ref "C111") (pin "2") (pinfunction "2_2") (pintype "passive"))
      (node (ref "C112") (pin "2") (pinfunction "2_2") (pintype "passive"))
      (node (ref "C113") (pin "2") (pinfunction "2_2") (pintype "passive"))
      (node (ref "C23") (pin "2") (pinfunction "-_2") (pintype "passive"))
      (node (ref "C24") (pin "2") (pinfunction "2_2") (pintype "passive"))
      (node (ref "C25") (pin "2") (pinfunction "2_2") (pintype "passive"))
      (node (ref "C26") (pin "2") (pinfunction "2_2") (pintype "passive"))
      (node (ref "C27") (pin "2") (pinfunction "2_2") (pintype "passive"))
      (node (ref "C28") (pin "2") (pinfunction "2_2") (pintype "passive"))
      (node (ref "C29") (pin "2") (pinfunction "2_2") (pintype "passive"))
      (node (ref "C30") (pin "2") (pinfunction "2_2") (pintype "passive"))
      (node (ref "C31") (pin "2") (pinfunction "2_2") (pintype "passive"))
      (node (ref "C32") (pin "2") (pinfunction "2_2") (pintype "passive"))
      (node (ref "C35") (pin "2") (pinfunction "-_2") (pintype "passive"))
      (node (ref "C36") (pin "2") (pinfunction "2_2") (pintype "passive"))
      (node (ref "C37") (pin "2") (pinfunction "2_2") (pintype "passive"))
      (node (ref "C38") (pin "2") (pinfunction "2_2") (pintype "passive"))
      (node (ref "C39") (pin "2") (pinfunction "2_2") (pintype "passive"))
      (node (ref "C40") (pin "2") (pinfunction "2_2") (pintype "passive"))
      (node (ref "C41") (pin "2") (pinfunction "2_2") (pintype "passive"))
      (node (ref "C42") (pin "2") (pinfunction "2_2") (pintype "passive"))
      (node (ref "C43") (pin "2") (pinfunction "2_2") (pintype "passive"))
      (node (ref "C44") (pin "2") (pinfunction "2_2") (pintype "passive"))
      (node (ref "C45") (pin "1") (pinfunction "1_1") (pintype "passive"))
      (node (ref "C47") (pin "2") (pinfunction "-_2") (pintype "passive"))
      (node (ref "C48") (pin "2") (pinfunction "2_2") (pintype "passive"))
      (node (ref "C49") (pin "2") (pinfunction "2_2") (pintype "passive"))
      (node (ref "C50") (pin "2") (pinfunction "2_2") (pintype "passive"))
      (node (ref "C53") (pin "2") (pinfunction "-_2") (pintype "passive"))
      (node (ref "C54") (pin "2") (pinfunction "2_2") (pintype "passive"))
      (node (ref "C55") (pin "2") (pinfunction "2_2") (pintype "passive"))
      (node (ref "C56") (pin "2") (pinfunction "2_2") (pintype "passive"))
      (node (ref "C57") (pin "1") (pinfunction "1_1") (pintype "passive"))
      (node (ref "D11") (pin "A") (pinfunction "A_A") (pintype "passive"))
      (node (ref "D14") (pin "A") (pinfunction "A_A") (pintype "passive"))
      (node (ref "IC10") (pin "5") (pinfunction "GND_5") (pintype "power_in"))
      (node (ref "IC11") (pin "5") (pinfunction "GND_5") (pintype "power_in"))
      (node (ref "IC12") (pin "5") (pinfunction "GND_5") (pintype "power_in"))
      (node (ref "IC14") (pin "5") (pinfunction "GND_5") (pintype "power_in"))
      (node (ref "IC16") (pin "5") (pinfunction "GND_5") (pintype "power_in"))
      (node (ref "IC6") (pin "5") (pinfunction "GND_5") (pintype "power_in"))
      (node (ref "IC7") (pin "5") (pinfunction "GND_5") (pintype "power_in"))
      (node (ref "IC8") (pin "5") (pinfunction "GND_5") (pintype "power_in"))
      (node (ref "R104") (pin "2") (pinfunction "2_2") (pintype "passive"))
      (node (ref "R108") (pin "2") (pinfunction "2_2") (pintype "passive"))
      (node (ref "R113") (pin "1") (pinfunction "1_1") (pintype "passive"))
      (node (ref "R115") (pin "2") (pinfunction "2_2") (pintype "passive"))
      (node (ref "R120") (pin "2") (pinfunction "2_2") (pintype "passive"))
      (node (ref "R25") (pin "2") (pinfunction "2_2") (pintype "passive"))
      (node (ref "R26") (pin "2") (pinfunction "2_2") (pintype "passive"))
      (node (ref "R27") (pin "2") (pinfunction "2_2") (pintype "passive"))
      (node (ref "R28") (pin "2") (pinfunction "2_2") (pintype "passive"))
      (node (ref "R29") (pin "2") (pinfunction "2_2") (pintype "passive"))
      (node (ref "R30") (pin "2") (pinfunction "2_2") (pintype "passive"))
      (node (ref "R31") (pin "2") (pinfunction "2_2") (pintype "passive"))
      (node (ref "R32") (pin "2") (pinfunction "2_2") (pintype "passive"))
      (node (ref "R33") (pin "1") (pinfunction "1_1") (pintype "passive"))
      (node (ref "R35") (pin "2") (pinfunction "2_2") (pintype "passive"))
      (node (ref "R40") (pin "2") (pinfunction "2_2") (pintype "passive"))
      (node (ref "R41") (pin "1") (pinfunction "1_1") (pintype "passive"))
      (node (ref "R43") (pin "2") (pinfunction "2_2") (pintype "passive"))
      (node (ref "R48") (pin "2") (pinfunction "2_2") (pintype "passive"))
      (node (ref "R49") (pin "1") (pinfunction "1_1") (pintype "passive"))
      (node (ref "R51") (pin "2") (pinfunction "2_2") (pintype "passive"))
      (node (ref "R56") (pin "2") (pinfunction "2_2") (pintype "passive"))
      (node (ref "R65") (pin "1") (pinfunction "1_1") (pintype "passive"))
      (node (ref "R67") (pin "2") (pinfunction "2_2") (pintype "passive"))
      (node (ref "R72") (pin "2") (pinfunction "2_2") (pintype "passive"))
      (node (ref "R73") (pin "1") (pinfunction "1_1") (pintype "passive"))
      (node (ref "R75") (pin "2") (pinfunction "2_2") (pintype "passive"))
      (node (ref "R80") (pin "2") (pinfunction "2_2") (pintype "passive"))
      (node (ref "R81") (pin "1") (pinfunction "1_1") (pintype "passive"))
      (node (ref "R83") (pin "2") (pinfunction "2_2") (pintype "passive"))
      (node (ref "R88") (pin "2") (pinfunction "2_2") (pintype "passive"))
      (node (ref "R96") (pin "2") (pinfunction "2_2") (pintype "passive"))
      (node (ref "R97") (pin "1") (pinfunction "1_1") (pintype "passive"))
      (node (ref "R99") (pin "2") (pinfunction "2_2") (pintype "passive"))
    )
    (net (code "15") (name "AVDD") (class "Default")
      (node (ref "AVDD") (pin "TP") (pinfunction "P$1_TP") (pintype "bidirectional"))
      (node (ref "C62") (pin "1") (pinfunction "1_1") (pintype "passive"))
      (node (ref "C74") (pin "1") (pinfunction "1_1") (pintype "passive"))
      (node (ref "IC15") (pin "43") (pinfunction "ADC_AVDD_43") (pintype "bidirectional"))
      (node (ref "IC17") (pin "1") (pinfunction "OUT_1") (pintype "output"))
      (node (ref "IC17") (pin "4") (pinfunction "-IN_4") (pintype "input"))
    )
    (net (code "16") (name "BUCK_EN") (class "Default")
      (node (ref "IC15") (pin "37") (pinfunction "GPIO25_37") (pintype "bidirectional"))
      (node (ref "IC2") (pin "6") (pinfunction "EN_6") (pintype "bidirectional"))
      (node (ref "R1") (pin "2") (pinfunction "2_2") (pintype "passive"))
      (node (ref "R2") (pin "2") (pinfunction "2_2") (pintype "passive"))
    )
    (net (code "17") (name "CC1") (class "Default")
      (node (ref "R125") (pin "1") (pinfunction "1_1") (pintype "passive"))
      (node (ref "USB1") (pin "A5") (pinfunction "CC1_A5") (pintype "bidirectional"))
    )
    (net (code "18") (name "CC2") (class "Default")
      (node (ref "R124") (pin "1") (pinfunction "1_1") (pintype "passive"))
      (node (ref "USB1") (pin "B5") (pinfunction "CC2_B5") (pintype "bidirectional"))
    )
    (net (code "19") (name "FAN_CTRL") (class "Default")
      (node (ref "IC15") (pin "39") (pinfunction "GPIO27/ADC1_39") (pintype "bidirectional"))
      (node (ref "R164") (pin "1") (pinfunction "1_1") (pintype "passive"))
      (node (ref "R165") (pin "1") (pinfunction "1_1") (pintype "passive"))
      (node (ref "T1") (pin "1") (pinfunction "G_1") (pintype "passive"))
    )
    (net (code "20") (name "FB1") (class "Default")
      (node (ref "C5") (pin "2") (pinfunction "2_2") (pintype "passive"))
      (node (ref "FB-NI1") (pin "TP") (pinfunction "P$1_TP") (pintype "bidirectional"))
      (node (ref "IC13") (pin "2") (pinfunction "FB_2") (pintype "input"))
      (node (ref "R60") (pin "1") (pinfunction "1_1") (pintype "passive"))
      (node (ref "R61") (pin "2") (pinfunction "2_2") (pintype "passive"))
    )
    (net (code "21") (name "FB2") (class "Default")
      (node (ref "C51") (pin "2") (pinfunction "2_2") (pintype "passive"))
      (node (ref "FB-NI2") (pin "TP") (pinfunction "P$1_TP") (pintype "bidirectional"))
      (node (ref "IC5") (pin "2") (pinfunction "FB_2") (pintype "input"))
      (node (ref "R105") (pin "2") (pinfunction "2_2") (pintype "passive"))
      (node (ref "R107") (pin "1") (pinfunction "1_1") (pintype "passive"))
    )
    (net (code "22") (name "FBIN1") (class "Default")
      (node (ref "C22") (pin "2") (pinfunction "2_2") (pintype "passive"))
      (node (ref "D9") (pin "C") (pinfunction "C_C") (pintype "passive"))
      (node (ref "R61") (pin "1") (pinfunction "1_1") (pintype "passive"))
    )
    (net (code "23") (name "FBIN2") (class "Default")
      (node (ref "C52") (pin "2") (pinfunction "2_2") (pintype "passive"))
      (node (ref "D13") (pin "C") (pinfunction "C_C") (pintype "passive"))
      (node (ref "R105") (pin "1") (pinfunction "1_1") (pintype "passive"))
    )
    (net (code "24") (name "GND") (class "Default")
      (node (ref "AC/DC1") (pin "-V") (pinfunction "-V_-V") (pintype "output"))
      (node (ref "AC/DC2") (pin "-V") (pinfunction "-V_-V") (pintype "output"))
      (node (ref "BOOT") (pin "2") (pinfunction "P$2_2") (pintype "bidirectional"))
      (node (ref "C1") (pin "2") (pinfunction "2_2") (pintype "passive"))
      (node (ref "C10") (pin "2") (pinfunction "-_2") (pintype "passive"))
      (node (ref "C100") (pin "2") (pinfunction "2_2") (pintype "passive"))
      (node (ref "C101") (pin "2") (pinfunction "2_2") (pintype "passive"))
      (node (ref "C102") (pin "2") (pinfunction "2_2") (pintype "passive"))
      (node (ref "C103") (pin "2") (pinfunction "2_2") (pintype "passive"))
      (node (ref "C104") (pin "2") (pinfunction "2_2") (pintype "passive"))
      (node (ref "C13") (pin "2") (pinfunction "-_2") (pintype "passive"))
      (node (ref "C14") (pin "2") (pinfunction "2_2") (pintype "passive"))
      (node (ref "C15") (pin "2") (pinfunction "2_2") (pintype "passive"))
      (node (ref "C16") (pin "2") (pinfunction "-_2") (pintype "passive"))
      (node (ref "C17") (pin "2") (pinfunction "2_2") (pintype "passive"))
      (node (ref "C18") (pin "2") (pinfunction "2_2") (pintype "passive"))
      (node (ref "C19") (pin "2") (pinfunction "2_2") (pintype "passive"))
      (node (ref "C2") (pin "2") (pinfunction "2_2") (pintype "passive"))
      (node (ref "C20") (pin "2") (pinfunction "2_2") (pintype "passive"))
      (node (ref "C3") (pin "2") (pinfunction "2_2") (pintype "passive"))
      (node (ref "C33") (pin "2") (pinfunction "2_2") (pintype "passive"))
      (node (ref "C34") (pin "2") (pinfunction "2_2") (pintype "passive"))
      (node (ref "C4") (pin "2") (pinfunction "2_2") (pintype "passive"))
      (node (ref "C58") (pin "2") (pinfunction "2_2") (pintype "passive"))
      (node (ref "C59") (pin "2") (pinfunction "2_2") (pintype "passive"))
      (node (ref "C6") (pin "2") (pinfunction "2_2") (pintype "passive"))
      (node (ref "C60") (pin "2") (pinfunction "2_2") (pintype "passive"))
      (node (ref "C61") (pin "2") (pinfunction "2_2") (pintype "passive"))
      (node (ref "C62") (pin "2") (pinfunction "2_2") (pintype "passive"))
      (node (ref "C63") (pin "2") (pinfunction "2_2") (pintype "passive"))
      (node (ref "C64") (pin "2") (pinfunction "2_2") (pintype "passive"))
      (node (ref "C65") (pin "2") (pinfunction "2_2") (pintype "passive"))
      (node (ref "C66") (pin "2") (pinfunction "2_2") (pintype "passive"))
      (node (ref "C67") (pin "2") (pinfunction "2_2") (pintype "passive"))
      (node (ref "C68") (pin "2") (pinfunction "2_2") (pintype "passive"))
      (node (ref "C69") (pin "2") (pinfunction "2_2") (pintype "passive"))
      (node (ref "C7") (pin "2") (pinfunction "2_2") (pintype "passive"))
      (node (ref "C70") (pin "2") (pinfunction "2_2") (pintype "passive"))
      (node (ref "C71") (pin "2") (pinfunction "2_2") (pintype "passive"))
      (node (ref "C72") (pin "2") (pinfunction "2_2") (pintype "passive"))
      (node (ref "C73") (pin "2") (pinfunction "2_2") (pintype "passive"))
      (node (ref "C74") (pin "2") (pinfunction "2_2") (pintype "passive"))
      (node (ref "C75") (pin "2") (pinfunction "2_2") (pintype "passive"))
      (node (ref "C76") (pin "2") (pinfunction "2_2") (pintype "passive"))
      (node (ref "C77") (pin "2") (pinfunction "2_2") (pintype "passive"))
      (node (ref "C78") (pin "2") (pinfunction "2_2") (pintype "passive"))
      (node (ref "C79") (pin "2") (pinfunction "2_2") (pintype "passive"))
      (node (ref "C80") (pin "2") (pinfunction "2_2") (pintype "passive"))
      (node (ref "C83") (pin "1") (pinfunction "1_1") (pintype "passive"))
      (node (ref "C84") (pin "2") (pinfunction "2_2") (pintype "passive"))
      (node (ref "C85") (pin "2") (pinfunction "2_2") (pintype "passive"))
      (node (ref "C86") (pin "2") (pinfunction "2_2") (pintype "passive"))
      (node (ref "C87") (pin "2") (pinfunction "2_2") (pintype "passive"))
      (node (ref "C88") (pin "2") (pinfunction "2_2") (pintype "passive"))
      (node (ref "C89") (pin "2") (pinfunction "2_2") (pintype "passive"))
      (node (ref "C90") (pin "2") (pinfunction "2_2") (pintype "passive"))
      (node (ref "C91") (pin "2") (pinfunction "2_2") (pintype "passive"))
      (node (ref "C92") (pin "2") (pinfunction "2_2") (pintype "passive"))
      (node (ref "C93") (pin "2") (pinfunction "2_2") (pintype "passive"))
      (node (ref "C94") (pin "2") (pinfunction "2_2") (pintype "passive"))
      (node (ref "C95") (pin "2") (pinfunction "2_2") (pintype "passive"))
      (node (ref "C96") (pin "2") (pinfunction "2_2") (pintype "passive"))
      (node (ref "C97") (pin "2") (pinfunction "2_2") (pintype "passive"))
      (node (ref "C98") (pin "2") (pinfunction "2_2") (pintype "passive"))
      (node (ref "C99") (pin "2") (pinfunction "2_2") (pintype "passive"))
      (node (ref "D16") (pin "A") (pinfunction "A_A") (pintype "passive"))
      (node (ref "D17") (pin "3") (pinfunction "3_3") (pintype "bidirectional"))
      (node (ref "D18") (pin "3") (pinfunction "3_3") (pintype "bidirectional"))
      (node (ref "DAT") (pin "C") (pinfunction "C_C") (pintype "passive"))
      (node (ref "DSP") (pin "5") (pinfunction "5_5") (pintype "bidirectional"))
      (node (ref "DSP") (pin "8") (pinfunction "8_8") (pintype "bidirectional"))
      (node (ref "DSP") (pin "Z0") (pinfunction "Z1_Z0") (pintype "bidirectional"))
      (node (ref "DSP") (pin "Z1") (pinfunction "Z1_Z1") (pintype "bidirectional"))
      (node (ref "DSP") (pin "Z2") (pinfunction "Z2_Z2") (pintype "bidirectional"))
      (node (ref "DSP") (pin "Z3") (pinfunction "Z3_Z3") (pintype "bidirectional"))
      (node (ref "DSP") (pin "Z4") (pinfunction "Z3_Z4") (pintype "bidirectional"))
      (node (ref "DSP") (pin "Z5") (pinfunction "Z4_Z5") (pintype "bidirectional"))
      (node (ref "ESD1") (pin "1") (pinfunction "A_1") (pintype "bidirectional"))
      (node (ref "ETH1") (pin "8") (pinfunction "GND_8") (pintype "power_in"))
      (node (ref "GDGC") (pin "4") (pinfunction "P$4_4") (pintype "bidirectional"))
      (node (ref "GND") (pin "TP") (pinfunction "P$1_TP") (pintype "bidirectional"))
      (node (ref "GND-3") (pin "TP") (pinfunction "P$1_TP") (pintype "bidirectional"))
      (node (ref "GND-5") (pin "TP") (pinfunction "P$1_TP") (pintype "bidirectional"))
      (node (ref "IC1") (pin "4") (pinfunction "GND_4") (pintype "bidirectional"))
      (node (ref "IC15") (pin "19") (pinfunction "TESTEN_19") (pintype "bidirectional"))
      (node (ref "IC15") (pin "PAD") (pinfunction "GND_PAD") (pintype "bidirectional"))
      (node (ref "IC17") (pin "5") (pinfunction "V-_5") (pintype "power_in"))
      (node (ref "IC18") (pin "4") (pinfunction "GND_4") (pintype "power_in"))
      (node (ref "IC18") (pin "PAD") (pinfunction "GND_PAD") (pintype "power_in"))
      (node (ref "IC19") (pin "2") (pinfunction "A1_2") (pintype "bidirectional"))
      (node (ref "IC19") (pin "3") (pinfunction "A2_3") (pintype "bidirectional"))
      (node (ref "IC19") (pin "4") (pinfunction "GND_4") (pintype "power_in"))
      (node (ref "IC19") (pin "7") (pinfunction "WP_7") (pintype "bidirectional"))
      (node (ref "IC19") (pin "9") (pinfunction "GND_9") (pintype "power_in"))
      (node (ref "IC2") (pin "4") (pinfunction "GND_4") (pintype "bidirectional"))
      (node (ref "IC20") (pin "14") (pinfunction "AGND_14") (pintype "power_in"))
      (node (ref "IC20") (pin "16") (pinfunction "AGND_16") (pintype "power_in"))
      (node (ref "IC20") (pin "19") (pinfunction "AGND_19") (pintype "power_in"))
      (node (ref "IC20") (pin "29") (pinfunction "GND_29") (pintype "passive"))
      (node (ref "IC20") (pin "3") (pinfunction "AGND_3") (pintype "power_in"))
      (node (ref "IC20") (pin "48") (pinfunction "AGND_48") (pintype "power_in"))
      (node (ref "IC20") (pin "9") (pinfunction "AGND_9") (pintype "power_in"))
      (node (ref "IC21") (pin "2") (pinfunction "GND_2") (pintype "bidirectional"))
      (node (ref "IC22") (pin "5") (pinfunction "V-_5") (pintype "power_in"))
      (node (ref "IC3") (pin "9") (pinfunction "GND_9") (pintype "bidirectional"))
      (node (ref "IC4") (pin "11") (pinfunction "A0_11") (pintype "bidirectional"))
      (node (ref "IC4") (pin "12") (pinfunction "A1_12") (pintype "bidirectional"))
      (node (ref "IC4") (pin "13") (pinfunction "A2_13") (pintype "bidirectional"))
      (node (ref "IC4") (pin "6") (pinfunction "VSS_6") (pintype "bidirectional"))
      (node (ref "IC4") (pin "PAD") (pinfunction "VSS_PAD") (pintype "bidirectional"))
      (node (ref "IC9") (pin "8") (pinfunction "GND_8") (pintype "power_in"))
      (node (ref "OPT1") (pin "11") (pinfunction "11_11") (pintype "passive"))
      (node (ref "OPT1") (pin "13") (pinfunction "13_13") (pintype "passive"))
      (node (ref "OPT1") (pin "15") (pinfunction "15_15") (pintype "passive"))
      (node (ref "OPT1") (pin "9") (pinfunction "9_9") (pintype "passive"))
      (node (ref "OPT2") (pin "11") (pinfunction "11_11") (pintype "passive"))
      (node (ref "OPT2") (pin "13") (pinfunction "13_13") (pintype "passive"))
      (node (ref "OPT2") (pin "15") (pinfunction "15_15") (pintype "passive"))
      (node (ref "OPT2") (pin "9") (pinfunction "9_9") (pintype "passive"))
      (node (ref "P12ON") (pin "C") (pinfunction "C_C") (pintype "passive"))
      (node (ref "P3ON") (pin "C") (pinfunction "C_C") (pintype "passive"))
      (node (ref "P5ON") (pin "C") (pinfunction "C_C") (pintype "passive"))
      (node (ref "PROC") (pin "C") (pinfunction "C_C") (pintype "passive"))
      (node (ref "R110") (pin "1") (pinfunction "1_1") (pintype "passive"))
      (node (ref "R12") (pin "2") (pinfunction "2_2") (pintype "passive"))
      (node (ref "R121") (pin "2") (pinfunction "2_2") (pintype "passive"))
      (node (ref "R124") (pin "2") (pinfunction "2_2") (pintype "passive"))
      (node (ref "R125") (pin "2") (pinfunction "2_2") (pintype "passive"))
      (node (ref "R127") (pin "2") (pinfunction "2_2") (pintype "passive"))
      (node (ref "R129") (pin "1") (pinfunction "1_1") (pintype "passive"))
      (node (ref "R131") (pin "2") (pinfunction "2_2") (pintype "passive"))
      (node (ref "R14") (pin "2") (pinfunction "2_2") (pintype "passive"))
      (node (ref "R143") (pin "1") (pinfunction "1_1") (pintype "passive"))
      (node (ref "R151") (pin "1") (pinfunction "1_1") (pintype "passive"))
      (node (ref "R161") (pin "1") (pinfunction "1_1") (pintype "passive"))
      (node (ref "R164") (pin "2") (pinfunction "2_2") (pintype "passive"))
      (node (ref "R2") (pin "1") (pinfunction "1_1") (pintype "passive"))
      (node (ref "R4") (pin "2") (pinfunction "2_2") (pintype "passive"))
      (node (ref "R6") (pin "2") (pinfunction "2_2") (pintype "passive"))
      (node (ref "R93") (pin "A2") (pinfunction "8_A2") (pintype "passive"))
      (node (ref "R93") (pin "B2") (pinfunction "7_B2") (pintype "passive"))
      (node (ref "R93") (pin "C2") (pinfunction "6_C2") (pintype "passive"))
      (node (ref "R93") (pin "D2") (pinfunction "5_D2") (pintype "passive"))
      (node (ref "R95") (pin "1") (pinfunction "1_1") (pintype "passive"))
      (node (ref "REF1") (pin "2") (pinfunction "A_2") (pintype "passive"))
      (node (ref "REF1") (pin "3") (pinfunction "A_3") (pintype "passive"))
      (node (ref "RESET") (pin "1") (pinfunction "P$1_1") (pintype "bidirectional"))
      (node (ref "RGTG") (pin "2") (pinfunction "P$2_2") (pintype "bidirectional"))
      (node (ref "RGTG") (pin "4") (pinfunction "P$4_4") (pintype "bidirectional"))
      (node (ref "RN1") (pin "A1") (pinfunction "1_A1") (pintype "passive"))
      (node (ref "RN1") (pin "B1") (pinfunction "1_B1") (pintype "passive"))
      (node (ref "RN1") (pin "C1") (pinfunction "1_C1") (pintype "passive"))
      (node (ref "RN1") (pin "D1") (pinfunction "1_D1") (pintype "passive"))
      (node (ref "RN2") (pin "A1") (pinfunction "1_A1") (pintype "passive"))
      (node (ref "RN2") (pin "B1") (pinfunction "1_B1") (pintype "passive"))
      (node (ref "RN2") (pin "C1") (pinfunction "1_C1") (pintype "passive"))
      (node (ref "RN2") (pin "D1") (pinfunction "1_D1") (pintype "passive"))
      (node (ref "T1") (pin "2") (pinfunction "S_2") (pintype "passive"))
      (node (ref "USB1") (pin "GND") (pinfunction "GND_GND") (pintype "power_in"))
      (node (ref "USB1") (pin "GND2") (pinfunction "GND_GND2") (pintype "power_in"))
      (node (ref "X1") (pin "2") (pinfunction "GND_2") (pintype "passive"))
      (node (ref "X1") (pin "4") (pinfunction "GND_4") (pintype "passive"))
      (node (ref "X2") (pin "2") (pinfunction "GND_2") (pintype "passive"))
      (node (ref "X2") (pin "4") (pinfunction "GND_4") (pintype "passive"))
    )
    (net (code "25") (name "I2C0_SCL") (class "Default")
      (node (ref "D17") (pin "1") (pinfunction "1_1") (pintype "bidirectional"))
      (node (ref "DSP") (pin "7") (pinfunction "7_7") (pintype "bidirectional"))
      (node (ref "IC15") (pin "7") (pinfunction "GPIO5_7") (pintype "bidirectional"))
      (node (ref "R130") (pin "A1") (pinfunction "1_A1") (pintype "passive"))
      (node (ref "SCL0") (pin "TP") (pinfunction "P$1_TP") (pintype "bidirectional"))
    )
    (net (code "26") (name "I2C0_SDA") (class "Default")
      (node (ref "D17") (pin "2") (pinfunction "2_2") (pintype "bidirectional"))
      (node (ref "DSP") (pin "6") (pinfunction "6_6") (pintype "bidirectional"))
      (node (ref "IC15") (pin "6") (pinfunction "GPIO4_6") (pintype "bidirectional"))
      (node (ref "R130") (pin "B1") (pinfunction "2_B1") (pintype "passive"))
      (node (ref "SDA0") (pin "TP") (pinfunction "P$1_TP") (pintype "bidirectional"))
    )
    (net (code "27") (name "I2C1_SCL") (class "Default")
      (node (ref "D18") (pin "1") (pinfunction "1_1") (pintype "bidirectional"))
      (node (ref "IC15") (pin "5") (pinfunction "GPIO3_5") (pintype "bidirectional"))
      (node (ref "IC19") (pin "6") (pinfunction "SCL_6") (pintype "bidirectional"))
      (node (ref "IC4") (pin "8") (pinfunction "SCL_8") (pintype "bidirectional"))
      (node (ref "R130") (pin "C1") (pinfunction "3_C1") (pintype "passive"))
      (node (ref "SCL1") (pin "TP") (pinfunction "P$1_TP") (pintype "bidirectional"))
    )
    (net (code "28") (name "I2C1_SDA") (class "Default")
      (node (ref "D18") (pin "2") (pinfunction "2_2") (pintype "bidirectional"))
      (node (ref "IC15") (pin "4") (pinfunction "GPIO2_4") (pintype "bidirectional"))
      (node (ref "IC19") (pin "5") (pinfunction "SDA_5") (pintype "bidirectional"))
      (node (ref "IC4") (pin "9") (pinfunction "SDA_9") (pintype "bidirectional"))
      (node (ref "R130") (pin "D1") (pinfunction "4_D1") (pintype "passive"))
      (node (ref "SDA1") (pin "TP") (pinfunction "P$1_TP") (pintype "bidirectional"))
    )
    (net (code "29") (name "KEY_0") (class "Default")
      (node (ref "DSP") (pin "12") (pinfunction "12_12") (pintype "bidirectional"))
      (node (ref "IC15") (pin "15") (pinfunction "GPIO12_15") (pintype "bidirectional"))
    )
    (net (code "30") (name "KEY_1") (class "Default")
      (node (ref "DSP") (pin "11") (pinfunction "11_11") (pintype "bidirectional"))
      (node (ref "IC15") (pin "16") (pinfunction "GPIO13_16") (pintype "bidirectional"))
    )
    (net (code "31") (name "KEY_2") (class "Default")
      (node (ref "DSP") (pin "10") (pinfunction "10_10") (pintype "bidirectional"))
      (node (ref "IC15") (pin "17") (pinfunction "GPIO14_17") (pintype "bidirectional"))
    )
    (net (code "32") (name "KEY_3") (class "Default")
      (node (ref "DSP") (pin "9") (pinfunction "9_9") (pintype "bidirectional"))
      (node (ref "IC15") (pin "18") (pinfunction "GPIO15_18") (pintype "bidirectional"))
    )
    (net (code "33") (name "LCD_BL") (class "Default")
      (node (ref "DSP") (pin "13") (pinfunction "13_13") (pintype "bidirectional"))
      (node (ref "IC15") (pin "9") (pinfunction "GPIO7_9") (pintype "bidirectional"))
    )
    (net (code "34") (name "LCD_CS") (class "Default")
      (node (ref "CS0") (pin "TP") (pinfunction "P$1_TP") (pintype "bidirectional"))
      (node (ref "DSP") (pin "19") (pinfunction "19_19") (pintype "bidirectional"))
      (node (ref "IC15") (pin "12") (pinfunction "GPIO9_12") (pintype "bidirectional"))
      (node (ref "R149") (pin "C2") (pinfunction "6_C2") (pintype "passive"))
    )
    (net (code "35") (name "LCD_DC") (class "Default")
      (node (ref "DSP") (pin "18") (pinfunction "18_18") (pintype "bidirectional"))
      (node (ref "IC15") (pin "8") (pinfunction "GPIO6_8") (pintype "bidirectional"))
    )
    (net (code "36") (name "LCD_MISO") (class "Default")
      (node (ref "DSP") (pin "15") (pinfunction "15_15") (pintype "bidirectional"))
      (node (ref "IC15") (pin "11") (pinfunction "GPIO8_11") (pintype "bidirectional"))
      (node (ref "MISO0") (pin "TP") (pinfunction "P$1_TP") (pintype "bidirectional"))
      (node (ref "R149") (pin "B2") (pinfunction "7_B2") (pintype "passive"))
    )
    (net (code "37") (name "LCD_MOSI") (class "Default")
      (node (ref "DSP") (pin "16") (pinfunction "16_16") (pintype "bidirectional"))
      (node (ref "IC15") (pin "14") (pinfunction "GPIO11_14") (pintype "bidirectional"))
      (node (ref "MOSI0") (pin "TP") (pinfunction "P$1_TP") (pintype "bidirectional"))
    )
    (net (code "38") (name "LCD_RES") (class "Default")
      (node (ref "DSP") (pin "14") (pinfunction "14_14") (pintype "bidirectional"))
      (node (ref "IC15") (pin "34") (pinfunction "GPIO22_34") (pintype "bidirectional"))
      (node (ref "R149") (pin "A2") (pinfunction "8_A2") (pintype "passive"))
    )
    (net (code "39") (name "LCD_SCLK") (class "Default")
      (node (ref "DSP") (pin "17") (pinfunction "17_17") (pintype "bidirectional"))
      (node (ref "IC15") (pin "13") (pinfunction "GPIO10_13") (pintype "bidirectional"))
      (node (ref "SCLK0") (pin "TP") (pinfunction "P$1_TP") (pintype "bidirectional"))
    )
    (net (code "40") (name "LREC1") (class "Default")
      (node (ref "C35") (pin "1") (pinfunction "+_1") (pintype "passive"))
      (node (ref "D10") (pin "C") (pinfunction "C_C") (pintype "passive"))
      (node (ref "IC13") (pin "5") (pinfunction "DRAIN_5") (pintype "input"))
      (node (ref "L-REC1") (pin "TP") (pinfunction "P$1_TP") (pintype "bidirectional"))
    )
    (net (code "41") (name "LREC2") (class "Default")
      (node (ref "C47") (pin "1") (pinfunction "+_1") (pintype "passive"))
      (node (ref "D12") (pin "C") (pinfunction "C_C") (pintype "passive"))
      (node (ref "IC5") (pin "5") (pinfunction "DRAIN_5") (pintype "input"))
      (node (ref "L-REC2") (pin "TP") (pinfunction "P$1_TP") (pintype "bidirectional"))
    )
    (net (code "42") (name "MCP_DSP_RST") (class "Default")
      (node (ref "DSP") (pin "20") (pinfunction "20_20") (pintype "bidirectional"))
      (node (ref "IC15") (pin "36") (pinfunction "GPIO24_36") (pintype "bidirectional"))
      (node (ref "R147") (pin "1") (pinfunction "1_1") (pintype "passive"))
    )
    (net (code "43") (name "MCP_REL_RST") (class "Default")
      (node (ref "IC15") (pin "35") (pinfunction "GPIO23_35") (pintype "bidirectional"))
      (node (ref "IC4") (pin "14") (pinfunction "~{RESET}_14") (pintype "bidirectional"))
    )
    (net (code "44") (name "MCP_VIN") (class "Default")
      (node (ref "C102") (pin "1") (pinfunction "1_1") (pintype "passive"))
      (node (ref "C63") (pin "1") (pinfunction "1_1") (pintype "passive"))
      (node (ref "IC17") (pin "2") (pinfunction "V+_2") (pintype "power_in"))
      (node (ref "R152") (pin "2") (pinfunction "2_2") (pintype "passive"))
    )
    (net (code "45") (name "MUX_A") (class "Default")
      (node (ref "IC4") (pin "25") (pinfunction "IO2.0_25") (pintype "bidirectional"))
      (node (ref "IC9") (pin "11") (pinfunction "A_11") (pintype "input"))
      (node (ref "R93") (pin "D1") (pinfunction "4_D1") (pintype "passive"))
    )
    (net (code "46") (name "MUX_B") (class "Default")
      (node (ref "IC4") (pin "26") (pinfunction "IO2.1_26") (pintype "bidirectional"))
      (node (ref "IC9") (pin "10") (pinfunction "B_10") (pintype "input"))
      (node (ref "R93") (pin "C1") (pinfunction "3_C1") (pintype "passive"))
    )
    (net (code "47") (name "MUX_C") (class "Default")
      (node (ref "IC4") (pin "27") (pinfunction "IO2.2_27") (pintype "bidirectional"))
      (node (ref "IC9") (pin "9") (pinfunction "C_9") (pintype "input"))
      (node (ref "R93") (pin "B1") (pinfunction "2_B1") (pintype "passive"))
    )
    (net (code "48") (name "MUX_EN") (class "Default")
      (node (ref "IC4") (pin "28") (pinfunction "IO2.3_28") (pintype "bidirectional"))
      (node (ref "IC9") (pin "7") (pinfunction "~{EN}_7") (pintype "input"))
      (node (ref "R93") (pin "A1") (pinfunction "1_A1") (pintype "passive"))
    )
    (net (code "49") (name "N_OUT1") (class "Default")
      (node (ref "N_OUT1") (pin "B2,8") (pinfunction "MOUNT_B2,8") (pintype "passive"))
      (node (ref "R25") (pin "1") (pinfunction "1_1") (pintype "passive"))
      (node (ref "R34") (pin "1") (pinfunction "1_1") (pintype "passive"))
      (node (ref "R35") (pin "1") (pinfunction "1_1") (pintype "passive"))
    )
    (net (code "50") (name "N_OUT2") (class "Default")
      (node (ref "N_OUT2") (pin "B2,8") (pinfunction "MOUNT_B2,8") (pintype "passive"))
      (node (ref "R32") (pin "1") (pinfunction "1_1") (pintype "passive"))
      (node (ref "R50") (pin "1") (pinfunction "1_1") (pintype "passive"))
      (node (ref "R51") (pin "1") (pinfunction "1_1") (pintype "passive"))
    )
    (net (code "51") (name "N_OUT3") (class "Default")
      (node (ref "N_OUT3") (pin "B2,8") (pinfunction "MOUNT_B2,8") (pintype "passive"))
      (node (ref "R31") (pin "1") (pinfunction "1_1") (pintype "passive"))
      (node (ref "R66") (pin "1") (pinfunction "1_1") (pintype "passive"))
      (node (ref "R67") (pin "1") (pinfunction "1_1") (pintype "passive"))
    )
    (net (code "52") (name "N_OUT4") (class "Default")
      (node (ref "N_OUT4") (pin "B2,8") (pinfunction "MOUNT_B2,8") (pintype "passive"))
      (node (ref "R30") (pin "1") (pinfunction "1_1") (pintype "passive"))
      (node (ref "R82") (pin "1") (pinfunction "1_1") (pintype "passive"))
      (node (ref "R83") (pin "1") (pinfunction "1_1") (pintype "passive"))
    )
    (net (code "53") (name "N_OUT5") (class "Default")
      (node (ref "N_OUT5") (pin "B2,8") (pinfunction "MOUNT_B2,8") (pintype "passive"))
      (node (ref "R26") (pin "1") (pinfunction "1_1") (pintype "passive"))
      (node (ref "R42") (pin "1") (pinfunction "1_1") (pintype "passive"))
      (node (ref "R43") (pin "1") (pinfunction "1_1") (pintype "passive"))
    )
    (net (code "54") (name "N_OUT6") (class "Default")
      (node (ref "N_OUT6") (pin "B2,8") (pinfunction "MOUNT_B2,8") (pintype "passive"))
      (node (ref "R27") (pin "1") (pinfunction "1_1") (pintype "passive"))
      (node (ref "R74") (pin "1") (pinfunction "1_1") (pintype "passive"))
      (node (ref "R75") (pin "1") (pinfunction "1_1") (pintype "passive"))
    )
    (net (code "55") (name "N_OUT7") (class "Default")
      (node (ref "N_OUT7") (pin "B2,8") (pinfunction "MOUNT_B2,8") (pintype "passive"))
      (node (ref "R28") (pin "1") (pinfunction "1_1") (pintype "passive"))
      (node (ref "R98") (pin "1") (pinfunction "1_1") (pintype "passive"))
      (node (ref "R99") (pin "1") (pinfunction "1_1") (pintype "passive"))
    )
    (net (code "56") (name "N_OUT8") (class "Default")
      (node (ref "N_OUT8") (pin "B2,8") (pinfunction "MOUNT_B2,8") (pintype "passive"))
      (node (ref "R114") (pin "1") (pinfunction "1_1") (pintype "passive"))
      (node (ref "R115") (pin "1") (pinfunction "1_1") (pintype "passive"))
      (node (ref "R29") (pin "1") (pinfunction "1_1") (pintype "passive"))
    )
    (net (code "57") (name "Net-(3VFB-P$1)") (class "Default")
      (node (ref "3VFB") (pin "TP") (pinfunction "P$1_TP") (pintype "bidirectional"))
      (node (ref "C12") (pin "2") (pinfunction "2_2") (pintype "passive"))
      (node (ref "R10") (pin "2") (pinfunction "2_2") (pintype "passive"))
      (node (ref "R13") (pin "2") (pinfunction "2_2") (pintype "passive"))
      (node (ref "R14") (pin "1") (pinfunction "1_1") (pintype "passive"))
    )
    (net (code "58") (name "Net-(5VFB-P$1)") (class "Default")
      (node (ref "5VFB") (pin "TP") (pinfunction "P$1_TP") (pintype "bidirectional"))
      (node (ref "C11") (pin "2") (pinfunction "2_2") (pintype "passive"))
      (node (ref "R11") (pin "2") (pinfunction "2_2") (pintype "passive"))
      (node (ref "R12") (pin "1") (pinfunction "1_1") (pintype "passive"))
      (node (ref "R8") (pin "2") (pinfunction "2_2") (pintype "passive"))
    )
    (net (code "59") (name "Net-(12VDC-P$1)") (class "Default")
      (node (ref "12VDC") (pin "TP") (pinfunction "P$1_TP") (pintype "bidirectional"))
      (node (ref "AC/DC1") (pin "+V") (pinfunction "+V_+V") (pintype "output"))
      (node (ref "AC/DC2") (pin "+V") (pinfunction "+V_+V") (pintype "output"))
      (node (ref "C10") (pin "1") (pinfunction "+_1") (pintype "passive"))
      (node (ref "C13") (pin "1") (pinfunction "+_1") (pintype "passive"))
      (node (ref "C16") (pin "1") (pinfunction "+_1") (pintype "passive"))
      (node (ref "D16") (pin "C") (pinfunction "C_C") (pintype "passive"))
      (node (ref "J10") (pin "2") (pinfunction "2_2") (pintype "passive"))
      (node (ref "J8") (pin "2") (pinfunction "2_2") (pintype "passive"))
      (node (ref "J9") (pin "2") (pinfunction "2_2") (pintype "passive"))
    )
    (net (code "60") (name "Net-(C8-Pad1)") (class "Default")
      (node (ref "C8") (pin "1") (pinfunction "1_1") (pintype "passive"))
      (node (ref "R7") (pin "1") (pinfunction "1_1") (pintype "passive"))
    )
    (net (code "61") (name "Net-(C9-Pad1)") (class "Default")
      (node (ref "C9") (pin "1") (pinfunction "1_1") (pintype "passive"))
      (node (ref "R9") (pin "1") (pinfunction "1_1") (pintype "passive"))
    )
    (net (code "62") (name "Net-(C106-Pad1)") (class "Default")
      (node (ref "C106") (pin "1") (pinfunction "1_1") (pintype "passive"))
      (node (ref "OPT1") (pin "2") (pinfunction "2_2") (pintype "passive"))
      (node (ref "R59") (pin "2") (pinfunction "2_2") (pintype "passive"))
    )
    (net (code "63") (name "Net-(C107-Pad1)") (class "Default")
      (node (ref "C107") (pin "1") (pinfunction "1_1") (pintype "passive"))
      (node (ref "OPT1") (pin "4") (pinfunction "4_4") (pintype "passive"))
      (node (ref "R153") (pin "2") (pinfunction "2_2") (pintype "passive"))
    )
    (net (code "64") (name "Net-(C108-Pad1)") (class "Default")
      (node (ref "C108") (pin "1") (pinfunction "1_1") (pintype "passive"))
      (node (ref "OPT1") (pin "6") (pinfunction "6_6") (pintype "passive"))
      (node (ref "R154") (pin "2") (pinfunction "2_2") (pintype "passive"))
    )
    (net (code "65") (name "Net-(C109-Pad1)") (class "Default")
      (node (ref "C109") (pin "1") (pinfunction "1_1") (pintype "passive"))
      (node (ref "OPT1") (pin "8") (pinfunction "8_8") (pintype "passive"))
      (node (ref "R155") (pin "2") (pinfunction "2_2") (pintype "passive"))
    )
    (net (code "66") (name "Net-(C110-Pad1)") (class "Default")
      (node (ref "C110") (pin "1") (pinfunction "1_1") (pintype "passive"))
      (node (ref "OPT2") (pin "2") (pinfunction "2_2") (pintype "passive"))
      (node (ref "R156") (pin "2") (pinfunction "2_2") (pintype "passive"))
    )
    (net (code "67") (name "Net-(C111-Pad1)") (class "Default")
      (node (ref "C111") (pin "1") (pinfunction "1_1") (pintype "passive"))
      (node (ref "OPT2") (pin "4") (pinfunction "4_4") (pintype "passive"))
      (node (ref "R157") (pin "2") (pinfunction "2_2") (pintype "passive"))
    )
    (net (code "68") (name "Net-(C112-Pad1)") (class "Default")
      (node (ref "C112") (pin "1") (pinfunction "1_1") (pintype "passive"))
      (node (ref "OPT2") (pin "6") (pinfunction "6_6") (pintype "passive"))
      (node (ref "R158") (pin "2") (pinfunction "2_2") (pintype "passive"))
    )
    (net (code "69") (name "Net-(C113-Pad1)") (class "Default")
      (node (ref "C113") (pin "1") (pinfunction "1_1") (pintype "passive"))
      (node (ref "OPT2") (pin "8") (pinfunction "8_8") (pintype "passive"))
      (node (ref "R159") (pin "2") (pinfunction "2_2") (pintype "passive"))
    )
    (net (code "70") (name "Net-(D10-PadA)") (class "Default")
      (node (ref "D10") (pin "A") (pinfunction "A_A") (pintype "passive"))
      (node (ref "R62") (pin "2") (pinfunction "2_2") (pintype "passive"))
    )
    (net (code "71") (name "Net-(D12-PadA)") (class "Default")
      (node (ref "D12") (pin "A") (pinfunction "A_A") (pintype "passive"))
      (node (ref "R106") (pin "2") (pinfunction "2_2") (pintype "passive"))
    )
    (net (code "72") (name "Net-(DAT-PadA)") (class "Default")
      (node (ref "DAT") (pin "A") (pinfunction "A_A") (pintype "passive"))
      (node (ref "R122") (pin "2") (pinfunction "2_2") (pintype "passive"))
    )
    (net (code "73") (name "Net-(ETH1-GREEN-)") (class "Default")
      (node (ref "ETH1") (pin "9") (pinfunction "GREEN-_9") (pintype "passive"))
      (node (ref "R142") (pin "2") (pinfunction "2_2") (pintype "passive"))
    )
    (net (code "74") (name "Net-(ETH1-YELLOW-)") (class "Default")
      (node (ref "ETH1") (pin "11") (pinfunction "YELLOW-_11") (pintype "passive"))
      (node (ref "R141") (pin "2") (pinfunction "2_2") (pintype "passive"))
    )
    (net (code "75") (name "Net-(IC1-AAM)") (class "Default")
      (node (ref "IC1") (pin "1") (pinfunction "AAM_1") (pintype "bidirectional"))
      (node (ref "R3") (pin "2") (pinfunction "2_2") (pintype "passive"))
      (node (ref "R4") (pin "1") (pinfunction "1_1") (pintype "passive"))
    )
    (net (code "76") (name "Net-(IC1-BST)") (class "Default")
      (node (ref "IC1") (pin "5") (pinfunction "BST_5") (pintype "bidirectional"))
      (node (ref "R7") (pin "2") (pinfunction "2_2") (pintype "passive"))
    )
    (net (code "77") (name "Net-(IC1-FB)") (class "Default")
      (node (ref "IC1") (pin "8") (pinfunction "FB_8") (pintype "bidirectional"))
      (node (ref "R8") (pin "1") (pinfunction "1_1") (pintype "passive"))
    )
    (net (code "78") (name "Net-(IC1-SW)") (class "Default")
      (node (ref "C8") (pin "2") (pinfunction "2_2") (pintype "passive"))
      (node (ref "IC1") (pin "3") (pinfunction "SW_3") (pintype "bidirectional"))
      (node (ref "L1") (pin "1") (pinfunction "1_1") (pintype "passive"))
      (node (ref "SW") (pin "TP") (pinfunction "P$1_TP") (pintype "bidirectional"))
    )
    (net (code "79") (name "Net-(IC1-VCC)") (class "Default")
      (node (ref "C6") (pin "1") (pinfunction "1_1") (pintype "passive"))
      (node (ref "IC1") (pin "7") (pinfunction "VCC_7") (pintype "bidirectional"))
      (node (ref "R3") (pin "1") (pinfunction "1_1") (pintype "passive"))
    )
    (net (code "80") (name "Net-(IC2-AAM)") (class "Default")
      (node (ref "IC2") (pin "1") (pinfunction "AAM_1") (pintype "bidirectional"))
      (node (ref "R5") (pin "2") (pinfunction "2_2") (pintype "passive"))
      (node (ref "R6") (pin "1") (pinfunction "1_1") (pintype "passive"))
    )
    (net (code "81") (name "Net-(IC2-BST)") (class "Default")
      (node (ref "IC2") (pin "5") (pinfunction "BST_5") (pintype "bidirectional"))
      (node (ref "R9") (pin "2") (pinfunction "2_2") (pintype "passive"))
    )
    (net (code "82") (name "Net-(IC2-FB)") (class "Default")
      (node (ref "IC2") (pin "8") (pinfunction "FB_8") (pintype "bidirectional"))
      (node (ref "R10") (pin "1") (pinfunction "1_1") (pintype "passive"))
    )
    (net (code "83") (name "Net-(IC2-SW)") (class "Default")
      (node (ref "C9") (pin "2") (pinfunction "2_2") (pintype "passive"))
      (node (ref "IC2") (pin "3") (pinfunction "SW_3") (pintype "bidirectional"))
      (node (ref "L2") (pin "1") (pinfunction "1_1") (pintype "passive"))
      (node (ref "SW3") (pin "TP") (pinfunction "P$1_TP") (pintype "bidirectional"))
    )
    (net (code "84") (name "Net-(IC2-VCC)") (class "Default")
      (node (ref "C7") (pin "1") (pinfunction "1_1") (pintype "passive"))
      (node (ref "IC2") (pin "7") (pinfunction "VCC_7") (pintype "bidirectional"))
      (node (ref "R5") (pin "1") (pinfunction "1_1") (pintype "passive"))
    )
    (net (code "85") (name "Net-(IC3-1C)") (class "Default")
      (node (ref "IC3") (pin "18") (pinfunction "1C_18") (pintype "bidirectional"))
      (node (ref "R17") (pin "1") (pinfunction "1_1") (pintype "passive"))
    )
    (net (code "86") (name "Net-(IC3-2C)") (class "Default")
      (node (ref "IC3") (pin "17") (pinfunction "2C_17") (pintype "bidirectional"))
      (node (ref "R18") (pin "1") (pinfunction "1_1") (pintype "passive"))
    )
    (net (code "87") (name "Net-(IC3-3C)") (class "Default")
      (node (ref "IC3") (pin "16") (pinfunction "3C_16") (pintype "bidirectional"))
      (node (ref "R19") (pin "1") (pinfunction "1_1") (pintype "passive"))
    )
    (net (code "88") (name "Net-(IC3-4C)") (class "Default")
      (node (ref "IC3") (pin "15") (pinfunction "4C_15") (pintype "bidirectional"))
      (node (ref "R20") (pin "1") (pinfunction "1_1") (pintype "passive"))
    )
    (net (code "89") (name "Net-(IC3-5C)") (class "Default")
      (node (ref "IC3") (pin "14") (pinfunction "5C_14") (pintype "bidirectional"))
      (node (ref "R21") (pin "1") (pinfunction "1_1") (pintype "passive"))
    )
    (net (code "90") (name "Net-(IC3-6C)") (class "Default")
      (node (ref "IC3") (pin "13") (pinfunction "6C_13") (pintype "bidirectional"))
      (node (ref "R22") (pin "1") (pinfunction "1_1") (pintype "passive"))
    )
    (net (code "91") (name "Net-(IC3-7C)") (class "Default")
      (node (ref "IC3") (pin "12") (pinfunction "7C_12") (pintype "bidirectional"))
      (node (ref "R23") (pin "1") (pinfunction "1_1") (pintype "passive"))
    )
    (net (code "92") (name "Net-(IC3-8C)") (class "Default")
      (node (ref "IC3") (pin "11") (pinfunction "8C_11") (pintype "bidirectional"))
      (node (ref "R24") (pin "1") (pinfunction "1_1") (pintype "passive"))
    )
    (net (code "93") (name "Net-(IC6-INN)") (class "Default")
      (node (ref "C25") (pin "1") (pinfunction "1_1") (pintype "passive"))
      (node (ref "IC6") (pin "3") (pinfunction "INN_3") (pintype "input"))
      (node (ref "R34") (pin "2") (pinfunction "2_2") (pintype "passive"))
    )
    (net (code "94") (name "Net-(IC6-INP)") (class "Default")
      (node (ref "C24") (pin "1") (pinfunction "1_1") (pintype "passive"))
      (node (ref "IC6") (pin "2") (pinfunction "INP_2") (pintype "input"))
      (node (ref "R33") (pin "2") (pinfunction "2_2") (pintype "passive"))
    )
    (net (code "95") (name "Net-(IC6-VP)") (class "Default")
      (node (ref "C26") (pin "1") (pinfunction "1_1") (pintype "passive"))
      (node (ref "IC6") (pin "4") (pinfunction "VP_4") (pintype "input"))
      (node (ref "R39") (pin "2") (pinfunction "2_2") (pintype "passive"))
      (node (ref "R40") (pin "1") (pinfunction "1_1") (pintype "passive"))
    )
    (net (code "96") (name "Net-(IC7-INN)") (class "Default")
      (node (ref "C28") (pin "1") (pinfunction "1_1") (pintype "passive"))
      (node (ref "IC7") (pin "3") (pinfunction "INN_3") (pintype "input"))
      (node (ref "R42") (pin "2") (pinfunction "2_2") (pintype "passive"))
    )
    (net (code "97") (name "Net-(IC7-INP)") (class "Default")
      (node (ref "C27") (pin "1") (pinfunction "1_1") (pintype "passive"))
      (node (ref "IC7") (pin "2") (pinfunction "INP_2") (pintype "input"))
      (node (ref "R41") (pin "2") (pinfunction "2_2") (pintype "passive"))
    )
    (net (code "98") (name "Net-(IC7-VP)") (class "Default")
      (node (ref "C29") (pin "1") (pinfunction "1_1") (pintype "passive"))
      (node (ref "IC7") (pin "4") (pinfunction "VP_4") (pintype "input"))
      (node (ref "R47") (pin "2") (pinfunction "2_2") (pintype "passive"))
      (node (ref "R48") (pin "1") (pinfunction "1_1") (pintype "passive"))
    )
    (net (code "99") (name "Net-(IC8-INN)") (class "Default")
      (node (ref "C31") (pin "1") (pinfunction "1_1") (pintype "passive"))
      (node (ref "IC8") (pin "3") (pinfunction "INN_3") (pintype "input"))
      (node (ref "R50") (pin "2") (pinfunction "2_2") (pintype "passive"))
    )
    (net (code "100") (name "Net-(IC8-INP)") (class "Default")
      (node (ref "C30") (pin "1") (pinfunction "1_1") (pintype "passive"))
      (node (ref "IC8") (pin "2") (pinfunction "INP_2") (pintype "input"))
      (node (ref "R49") (pin "2") (pinfunction "2_2") (pintype "passive"))
    )
    (net (code "101") (name "Net-(IC8-VP)") (class "Default")
      (node (ref "C32") (pin "1") (pinfunction "1_1") (pintype "passive"))
      (node (ref "IC8") (pin "4") (pinfunction "VP_4") (pintype "input"))
      (node (ref "R55") (pin "2") (pinfunction "2_2") (pintype "passive"))
      (node (ref "R56") (pin "1") (pinfunction "1_1") (pintype "passive"))
    )
    (net (code "102") (name "Net-(IC10-INN)") (class "Default")
      (node (ref "C37") (pin "1") (pinfunction "1_1") (pintype "passive"))
      (node (ref "IC10") (pin "3") (pinfunction "INN_3") (pintype "input"))
      (node (ref "R66") (pin "2") (pinfunction "2_2") (pintype "passive"))
    )
    (net (code "103") (name "Net-(IC10-INP)") (class "Default")
      (node (ref "C36") (pin "1") (pinfunction "1_1") (pintype "passive"))
      (node (ref "IC10") (pin "2") (pinfunction "INP_2") (pintype "input"))
      (node (ref "R65") (pin "2") (pinfunction "2_2") (pintype "passive"))
    )
    (net (code "104") (name "Net-(IC10-VP)") (class "Default")
      (node (ref "C38") (pin "1") (pinfunction "1_1") (pintype "passive"))
      (node (ref "IC10") (pin "4") (pinfunction "VP_4") (pintype "input"))
      (node (ref "R71") (pin "2") (pinfunction "2_2") (pintype "passive"))
      (node (ref "R72") (pin "1") (pinfunction "1_1") (pintype "passive"))
    )
    (net (code "105") (name "Net-(IC11-INN)") (class "Default")
      (node (ref "C40") (pin "1") (pinfunction "1_1") (pintype "passive"))
      (node (ref "IC11") (pin "3") (pinfunction "INN_3") (pintype "input"))
      (node (ref "R74") (pin "2") (pinfunction "2_2") (pintype "passive"))
    )
    (net (code "106") (name "Net-(IC11-INP)") (class "Default")
      (node (ref "C39") (pin "1") (pinfunction "1_1") (pintype "passive"))
      (node (ref "IC11") (pin "2") (pinfunction "INP_2") (pintype "input"))
      (node (ref "R73") (pin "2") (pinfunction "2_2") (pintype "passive"))
    )
    (net (code "107") (name "Net-(IC11-VP)") (class "Default")
      (node (ref "C41") (pin "1") (pinfunction "1_1") (pintype "passive"))
      (node (ref "IC11") (pin "4") (pinfunction "VP_4") (pintype "input"))
      (node (ref "R79") (pin "2") (pinfunction "2_2") (pintype "passive"))
      (node (ref "R80") (pin "1") (pinfunction "1_1") (pintype "passive"))
    )
    (net (code "108") (name "Net-(IC12-INN)") (class "Default")
      (node (ref "C43") (pin "1") (pinfunction "1_1") (pintype "passive"))
      (node (ref "IC12") (pin "3") (pinfunction "INN_3") (pintype "input"))
      (node (ref "R82") (pin "2") (pinfunction "2_2") (pintype "passive"))
    )
    (net (code "109") (name "Net-(IC12-INP)") (class "Default")
      (node (ref "C42") (pin "1") (pinfunction "1_1") (pintype "passive"))
      (node (ref "IC12") (pin "2") (pinfunction "INP_2") (pintype "input"))
      (node (ref "R81") (pin "2") (pinfunction "2_2") (pintype "passive"))
    )
    (net (code "110") (name "Net-(IC12-VP)") (class "Default")
      (node (ref "C44") (pin "1") (pinfunction "1_1") (pintype "passive"))
      (node (ref "IC12") (pin "4") (pinfunction "VP_4") (pintype "input"))
      (node (ref "R87") (pin "2") (pinfunction "2_2") (pintype "passive"))
      (node (ref "R88") (pin "1") (pinfunction "1_1") (pintype "passive"))
    )
    (net (code "111") (name "Net-(IC14-INN)") (class "Default")
      (node (ref "C49") (pin "1") (pinfunction "1_1") (pintype "passive"))
      (node (ref "IC14") (pin "3") (pinfunction "INN_3") (pintype "input"))
      (node (ref "R98") (pin "2") (pinfunction "2_2") (pintype "passive"))
    )
    (net (code "112") (name "Net-(IC14-INP)") (class "Default")
      (node (ref "C48") (pin "1") (pinfunction "1_1") (pintype "passive"))
      (node (ref "IC14") (pin "2") (pinfunction "INP_2") (pintype "input"))
      (node (ref "R97") (pin "2") (pinfunction "2_2") (pintype "passive"))
    )
    (net (code "113") (name "Net-(IC14-VP)") (class "Default")
      (node (ref "C50") (pin "1") (pinfunction "1_1") (pintype "passive"))
      (node (ref "IC14") (pin "4") (pinfunction "VP_4") (pintype "input"))
      (node (ref "R103") (pin "2") (pinfunction "2_2") (pintype "passive"))
      (node (ref "R104") (pin "1") (pinfunction "1_1") (pintype "passive"))
    )
    (net (code "114") (name "Net-(IC15-GPIO28{slash}ADC2)") (class "Default")
      (node (ref "IC15") (pin "40") (pinfunction "GPIO28/ADC2_40") (pintype "bidirectional"))
      (node (ref "R163") (pin "2") (pinfunction "2_2") (pintype "passive"))
    )
    (net (code "115") (name "Net-(IC15-USB_DM)") (class "Default")
      (node (ref "IC15") (pin "46") (pinfunction "USB_DM_46") (pintype "bidirectional"))
      (node (ref "R15") (pin "2") (pinfunction "2_2") (pintype "passive"))
    )
    (net (code "116") (name "Net-(IC15-USB_DP)") (class "Default")
      (node (ref "IC15") (pin "47") (pinfunction "USB_DP_47") (pintype "bidirectional"))
      (node (ref "R160") (pin "2") (pinfunction "2_2") (pintype "passive"))
    )
    (net (code "117") (name "Net-(IC16-INN)") (class "Default")
      (node (ref "C55") (pin "1") (pinfunction "1_1") (pintype "passive"))
      (node (ref "IC16") (pin "3") (pinfunction "INN_3") (pintype "input"))
      (node (ref "R114") (pin "2") (pinfunction "2_2") (pintype "passive"))
    )
    (net (code "118") (name "Net-(IC16-INP)") (class "Default")
      (node (ref "C54") (pin "1") (pinfunction "1_1") (pintype "passive"))
      (node (ref "IC16") (pin "2") (pinfunction "INP_2") (pintype "input"))
      (node (ref "R113") (pin "2") (pinfunction "2_2") (pintype "passive"))
    )
    (net (code "119") (name "Net-(IC16-VP)") (class "Default")
      (node (ref "C56") (pin "1") (pinfunction "1_1") (pintype "passive"))
      (node (ref "IC16") (pin "4") (pinfunction "VP_4") (pintype "input"))
      (node (ref "R119") (pin "2") (pinfunction "2_2") (pintype "passive"))
      (node (ref "R120") (pin "1") (pinfunction "1_1") (pintype "passive"))
    )
    (net (code "120") (name "Net-(IC17-+IN)") (class "Default")
      (node (ref "C60") (pin "1") (pinfunction "1_1") (pintype "passive"))
      (node (ref "C61") (pin "1") (pinfunction "1_1") (pintype "passive"))
      (node (ref "IC17") (pin "3") (pinfunction "+IN_3") (pintype "input"))
      (node (ref "R109") (pin "1") (pinfunction "1_1") (pintype "passive"))
      (node (ref "REF1") (pin "1") (pinfunction "C_1") (pintype "passive"))
      (node (ref "VREF") (pin "TP") (pinfunction "P$1_TP") (pintype "bidirectional"))
    )
    (net (code "121") (name "Net-(IC19-A0)") (class "Default")
      (node (ref "IC19") (pin "1") (pinfunction "A0_1") (pintype "bidirectional"))
      (node (ref "R128") (pin "1") (pinfunction "1_1") (pintype "passive"))
      (node (ref "R129") (pin "2") (pinfunction "2_2") (pintype "passive"))
    )
    (net (code "122") (name "Net-(IC20-1V2O)") (class "Default")
      (node (ref "C84") (pin "1") (pinfunction "1_1") (pintype "passive"))
      (node (ref "IC20") (pin "22") (pinfunction "1V2O_22") (pintype "output"))
    )
    (net (code "123") (name "Net-(IC20-EXRES1)") (class "Default")
      (node (ref "IC20") (pin "10") (pinfunction "EXRES1_10") (pintype "bidirectional"))
      (node (ref "R143") (pin "2") (pinfunction "2_2") (pintype "passive"))
    )
    (net (code "124") (name "Net-(IC20-TOCAP)") (class "Default")
      (node (ref "C85") (pin "1") (pinfunction "1_1") (pintype "passive"))
      (node (ref "IC20") (pin "20") (pinfunction "TOCAP_20") (pintype "output"))
    )
    (net (code "125") (name "Net-(IC20-XI)") (class "Default")
      (node (ref "C87") (pin "1") (pinfunction "1_1") (pintype "passive"))
      (node (ref "IC20") (pin "30") (pinfunction "XI_30") (pintype "input"))
      (node (ref "R144") (pin "1") (pinfunction "1_1") (pintype "passive"))
      (node (ref "X2") (pin "3") (pinfunction "2_3") (pintype "passive"))
    )
    (net (code "126") (name "Net-(IC20-XO)") (class "Default")
      (node (ref "C86") (pin "1") (pinfunction "1_1") (pintype "passive"))
      (node (ref "IC20") (pin "31") (pinfunction "XO_31") (pintype "output"))
      (node (ref "R144") (pin "2") (pinfunction "2_2") (pintype "passive"))
      (node (ref "X2") (pin "1") (pinfunction "1_1") (pintype "passive"))
    )
    (net (code "127") (name "Net-(IC22--IN)") (class "Default")
      (node (ref "IC22") (pin "1") (pinfunction "OUT_1") (pintype "output"))
      (node (ref "IC22") (pin "4") (pinfunction "-IN_4") (pintype "input"))
      (node (ref "R122") (pin "1") (pinfunction "1_1") (pintype "passive"))
    )
    (net (code "128") (name "Net-(P3ON-PadA)") (class "Default")
      (node (ref "P3ON") (pin "A") (pinfunction "A_A") (pintype "passive"))
      (node (ref "R123") (pin "2") (pinfunction "2_2") (pintype "passive"))
    )
    (net (code "129") (name "Net-(P5ON-PadA)") (class "Default")
      (node (ref "P5ON") (pin "A") (pinfunction "A_A") (pintype "passive"))
      (node (ref "R148") (pin "2") (pinfunction "2_2") (pintype "passive"))
    )
    (net (code "130") (name "Net-(P12ON-PadA)") (class "Default")
      (node (ref "P12ON") (pin "A") (pinfunction "A_A") (pintype "passive"))
      (node (ref "R150") (pin "2") (pinfunction "2_2") (pintype "passive"))
    )
    (net (code "131") (name "Net-(PROC-PadA)") (class "Default")
      (node (ref "PROC") (pin "A") (pinfunction "A_A") (pintype "passive"))
      (node (ref "R163") (pin "1") (pinfunction "1_1") (pintype "passive"))
    )
    (net (code "132") (name "Net-(PWR-PadC)") (class "Default")
      (node (ref "PWR") (pin "C") (pinfunction "C_C") (pintype "passive"))
      (node (ref "R151") (pin "2") (pinfunction "2_2") (pintype "passive"))
    )
    (net (code "133") (name "Net-(R36-Pad1)") (class "Default")
      (node (ref "R36") (pin "1") (pinfunction "1_1") (pintype "passive"))
      (node (ref "R37") (pin "2") (pinfunction "2_2") (pintype "passive"))
    )
    (net (code "134") (name "Net-(R37-Pad1)") (class "Default")
      (node (ref "R37") (pin "1") (pinfunction "1_1") (pintype "passive"))
      (node (ref "R38") (pin "1") (pinfunction "1_1") (pintype "passive"))
    )
    (net (code "135") (name "Net-(R38-Pad2)") (class "Default")
      (node (ref "R38") (pin "2") (pinfunction "2_2") (pintype "passive"))
      (node (ref "R39") (pin "1") (pinfunction "1_1") (pintype "passive"))
    )
    (net (code "136") (name "Net-(R44-Pad2)") (class "Default")
      (node (ref "R44") (pin "2") (pinfunction "2_2") (pintype "passive"))
      (node (ref "R45") (pin "2") (pinfunction "2_2") (pintype "passive"))
    )
    (net (code "137") (name "Net-(R45-Pad1)") (class "Default")
      (node (ref "R45") (pin "1") (pinfunction "1_1") (pintype "passive"))
      (node (ref "R46") (pin "1") (pinfunction "1_1") (pintype "passive"))
    )
    (net (code "138") (name "Net-(R46-Pad2)") (class "Default")
      (node (ref "R46") (pin "2") (pinfunction "2_2") (pintype "passive"))
      (node (ref "R47") (pin "1") (pinfunction "1_1") (pintype "passive"))
    )
    (net (code "139") (name "Net-(R52-Pad2)") (class "Default")
      (node (ref "R52") (pin "2") (pinfunction "2_2") (pintype "passive"))
      (node (ref "R53") (pin "2") (pinfunction "2_2") (pintype "passive"))
    )
    (net (code "140") (name "Net-(R53-Pad1)") (class "Default")
      (node (ref "R53") (pin "1") (pinfunction "1_1") (pintype "passive"))
      (node (ref "R54") (pin "1") (pinfunction "1_1") (pintype "passive"))
    )
    (net (code "141") (name "Net-(R54-Pad2)") (class "Default")
      (node (ref "R54") (pin "2") (pinfunction "2_2") (pintype "passive"))
      (node (ref "R55") (pin "1") (pinfunction "1_1") (pintype "passive"))
    )
    (net (code "142") (name "Net-(R57-Pad1)") (class "Default")
      (node (ref "R57") (pin "1") (pinfunction "1_1") (pintype "passive"))
      (node (ref "R58") (pin "1") (pinfunction "1_1") (pintype "passive"))
      (node (ref "R91") (pin "2") (pinfunction "2_2") (pintype "passive"))
      (node (ref "R92") (pin "2") (pinfunction "2_2") (pintype "passive"))
    )
    (net (code "143") (name "Net-(R63-5)") (class "Default")
      (node (ref "OPT1") (pin "7") (pinfunction "7_7") (pintype "passive"))
      (node (ref "R63") (pin "D2") (pinfunction "5_D2") (pintype "passive"))
    )
    (net (code "144") (name "Net-(R63-6)") (class "Default")
      (node (ref "OPT1") (pin "5") (pinfunction "5_5") (pintype "passive"))
      (node (ref "R63") (pin "C2") (pinfunction "6_C2") (pintype "passive"))
    )
    (net (code "145") (name "Net-(R63-7)") (class "Default")
      (node (ref "OPT1") (pin "3") (pinfunction "3_3") (pintype "passive"))
      (node (ref "R63") (pin "B2") (pinfunction "7_B2") (pintype "passive"))
    )
    (net (code "146") (name "Net-(R63-8)") (class "Default")
      (node (ref "OPT1") (pin "1") (pinfunction "1_1") (pintype "passive"))
      (node (ref "R63") (pin "A2") (pinfunction "8_A2") (pintype "passive"))
    )
    (net (code "147") (name "Net-(R64-5)") (class "Default")
      (node (ref "OPT2") (pin "7") (pinfunction "7_7") (pintype "passive"))
      (node (ref "R64") (pin "D2") (pinfunction "5_D2") (pintype "passive"))
    )
    (net (code "148") (name "Net-(R64-6)") (class "Default")
      (node (ref "OPT2") (pin "5") (pinfunction "5_5") (pintype "passive"))
      (node (ref "R64") (pin "C2") (pinfunction "6_C2") (pintype "passive"))
    )
    (net (code "149") (name "Net-(R64-7)") (class "Default")
      (node (ref "OPT2") (pin "3") (pinfunction "3_3") (pintype "passive"))
      (node (ref "R64") (pin "B2") (pinfunction "7_B2") (pintype "passive"))
    )
    (net (code "150") (name "Net-(R64-8)") (class "Default")
      (node (ref "OPT2") (pin "1") (pinfunction "1_1") (pintype "passive"))
      (node (ref "R64") (pin "A2") (pinfunction "8_A2") (pintype "passive"))
    )
    (net (code "151") (name "Net-(R68-Pad2)") (class "Default")
      (node (ref "R68") (pin "2") (pinfunction "2_2") (pintype "passive"))
      (node (ref "R69") (pin "2") (pinfunction "2_2") (pintype "passive"))
    )
    (net (code "152") (name "Net-(R69-Pad1)") (class "Default")
      (node (ref "R69") (pin "1") (pinfunction "1_1") (pintype "passive"))
      (node (ref "R70") (pin "1") (pinfunction "1_1") (pintype "passive"))
    )
    (net (code "153") (name "Net-(R70-Pad2)") (class "Default")
      (node (ref "R70") (pin "2") (pinfunction "2_2") (pintype "passive"))
      (node (ref "R71") (pin "1") (pinfunction "1_1") (pintype "passive"))
    )
    (net (code "154") (name "Net-(R76-Pad2)") (class "Default")
      (node (ref "R76") (pin "2") (pinfunction "2_2") (pintype "passive"))
      (node (ref "R77") (pin "2") (pinfunction "2_2") (pintype "passive"))
    )
    (net (code "155") (name "Net-(R77-Pad1)") (class "Default")
      (node (ref "R77") (pin "1") (pinfunction "1_1") (pintype "passive"))
      (node (ref "R78") (pin "1") (pinfunction "1_1") (pintype "passive"))
    )
    (net (code "156") (name "Net-(R78-Pad2)") (class "Default")
      (node (ref "R78") (pin "2") (pinfunction "2_2") (pintype "passive"))
      (node (ref "R79") (pin "1") (pinfunction "1_1") (pintype "passive"))
    )
    (net (code "157") (name "Net-(R84-Pad2)") (class "Default")
      (node (ref "R84") (pin "2") (pinfunction "2_2") (pintype "passive"))
      (node (ref "R85") (pin "2") (pinfunction "2_2") (pintype "passive"))
    )
    (net (code "158") (name "Net-(R85-Pad1)") (class "Default")
      (node (ref "R85") (pin "1") (pinfunction "1_1") (pintype "passive"))
      (node (ref "R86") (pin "1") (pinfunction "1_1") (pintype "passive"))
    )
    (net (code "159") (name "Net-(R86-Pad2)") (class "Default")
      (node (ref "R86") (pin "2") (pinfunction "2_2") (pintype "passive"))
      (node (ref "R87") (pin "1") (pinfunction "1_1") (pintype "passive"))
    )
    (net (code "160") (name "Net-(R100-Pad2)") (class "Default")
      (node (ref "R100") (pin "2") (pinfunction "2_2") (pintype "passive"))
      (node (ref "R101") (pin "2") (pinfunction "2_2") (pintype "passive"))
    )
    (net (code "161") (name "Net-(R101-Pad1)") (class "Default")
      (node (ref "R101") (pin "1") (pinfunction "1_1") (pintype "passive"))
      (node (ref "R102") (pin "1") (pinfunction "1_1") (pintype "passive"))
    )
    (net (code "162") (name "Net-(R102-Pad2)") (class "Default")
      (node (ref "R102") (pin "2") (pinfunction "2_2") (pintype "passive"))
      (node (ref "R103") (pin "1") (pinfunction "1_1") (pintype "passive"))
    )
    (net (code "163") (name "Net-(R116-Pad2)") (class "Default")
      (node (ref "R116") (pin "2") (pinfunction "2_2") (pintype "passive"))
      (node (ref "R117") (pin "2") (pinfunction "2_2") (pintype "passive"))
    )
    (net (code "164") (name "Net-(R117-Pad1)") (class "Default")
      (node (ref "R117") (pin "1") (pinfunction "1_1") (pintype "passive"))
      (node (ref "R118") (pin "1") (pinfunction "1_1") (pintype "passive"))
    )
    (net (code "165") (name "Net-(R118-Pad2)") (class "Default")
      (node (ref "R118") (pin "2") (pinfunction "2_2") (pintype "passive"))
      (node (ref "R119") (pin "1") (pinfunction "1_1") (pintype "passive"))
    )
    (net (code "166") (name "Net-(T1-D)") (class "Default")
      (node (ref "FAN") (pin "1") (pinfunction "1_1") (pintype "passive"))
      (node (ref "T1") (pin "3") (pinfunction "D_3") (pintype "passive"))
    )
    (net (code "167") (name "Net-(X1-2)") (class "Default")
      (node (ref "C59") (pin "1") (pinfunction "1_1") (pintype "passive"))
      (node (ref "R16") (pin "1") (pinfunction "1_1") (pintype "passive"))
      (node (ref "X1") (pin "3") (pinfunction "2_3") (pintype "passive"))
    )
    (net (code "168") (name "OUT_1") (class "Default")
      (node (ref "K1") (pin "4") (pinfunction "4_4") (pintype "passive"))
      (node (ref "K1") (pin "5") (pinfunction "5_5") (pintype "passive"))
      (node (ref "L_OUT1") (pin "B2,8") (pinfunction "MOUNT_B2,8") (pintype "passive"))
      (node (ref "R36") (pin "2") (pinfunction "2_2") (pintype "passive"))
    )
    (net (code "169") (name "OUT_2") (class "Default")
      (node (ref "K2") (pin "4") (pinfunction "4_4") (pintype "passive"))
      (node (ref "K2") (pin "5") (pinfunction "5_5") (pintype "passive"))
      (node (ref "L_OUT2") (pin "B2,8") (pinfunction "MOUNT_B2,8") (pintype "passive"))
      (node (ref "R52") (pin "1") (pinfunction "1_1") (pintype "passive"))
    )
    (net (code "170") (name "OUT_3") (class "Default")
      (node (ref "K3") (pin "4") (pinfunction "4_4") (pintype "passive"))
      (node (ref "K3") (pin "5") (pinfunction "5_5") (pintype "passive"))
      (node (ref "L_OUT3") (pin "B2,8") (pinfunction "MOUNT_B2,8") (pintype "passive"))
      (node (ref "R68") (pin "1") (pinfunction "1_1") (pintype "passive"))
    )
    (net (code "171") (name "OUT_4") (class "Default")
      (node (ref "K4") (pin "4") (pinfunction "4_4") (pintype "passive"))
      (node (ref "K4") (pin "5") (pinfunction "5_5") (pintype "passive"))
      (node (ref "L_OUT4") (pin "B2,8") (pinfunction "MOUNT_B2,8") (pintype "passive"))
      (node (ref "R84") (pin "1") (pinfunction "1_1") (pintype "passive"))
    )
    (net (code "172") (name "OUT_5") (class "Default")
      (node (ref "K5") (pin "4") (pinfunction "4_4") (pintype "passive"))
      (node (ref "K5") (pin "5") (pinfunction "5_5") (pintype "passive"))
      (node (ref "L_OUT5") (pin "B2,8") (pinfunction "MOUNT_B2,8") (pintype "passive"))
      (node (ref "R44") (pin "1") (pinfunction "1_1") (pintype "passive"))
    )
    (net (code "173") (name "OUT_6") (class "Default")
      (node (ref "K6") (pin "4") (pinfunction "4_4") (pintype "passive"))
      (node (ref "K6") (pin "5") (pinfunction "5_5") (pintype "passive"))
      (node (ref "L_OUT6") (pin "B2,8") (pinfunction "MOUNT_B2,8") (pintype "passive"))
      (node (ref "R76") (pin "1") (pinfunction "1_1") (pintype "passive"))
    )
    (net (code "174") (name "OUT_7") (class "Default")
      (node (ref "K7") (pin "4") (pinfunction "4_4") (pintype "passive"))
      (node (ref "K7") (pin "5") (pinfunction "5_5") (pintype "passive"))
      (node (ref "L_OUT7") (pin "B2,8") (pinfunction "MOUNT_B2,8") (pintype "passive"))
      (node (ref "R100") (pin "1") (pinfunction "1_1") (pintype "passive"))
    )
    (net (code "175") (name "OUT_8") (class "Default")
      (node (ref "K8") (pin "4") (pinfunction "4_4") (pintype "passive"))
      (node (ref "K8") (pin "5") (pinfunction "5_5") (pintype "passive"))
      (node (ref "L_OUT8") (pin "B2,8") (pinfunction "MOUNT_B2,8") (pintype "passive"))
      (node (ref "R116") (pin "1") (pinfunction "1_1") (pintype "passive"))
    )
    (net (code "176") (name "QSPI_SCLK") (class "Default")
      (node (ref "IC15") (pin "52") (pinfunction "QSPI_SCLK_52") (pintype "bidirectional"))
      (node (ref "IC18") (pin "6") (pinfunction "CLK_6") (pintype "bidirectional"))
    )
    (net (code "177") (name "QSPI_SD0") (class "Default")
      (node (ref "IC15") (pin "53") (pinfunction "QSPI_SD0_53") (pintype "bidirectional"))
      (node (ref "IC18") (pin "5") (pinfunction "DI/IO0_5") (pintype "bidirectional"))
    )
    (net (code "178") (name "QSPI_SD1") (class "Default")
      (node (ref "IC15") (pin "55") (pinfunction "QSPI_SD1_55") (pintype "bidirectional"))
      (node (ref "IC18") (pin "2") (pinfunction "DO/IO1_2") (pintype "bidirectional"))
    )
    (net (code "179") (name "QSPI_SD2") (class "Default")
      (node (ref "IC15") (pin "54") (pinfunction "QSPI_SD2_54") (pintype "bidirectional"))
      (node (ref "IC18") (pin "3") (pinfunction "~{WP}/IO2_3") (pintype "bidirectional"))
    )
    (net (code "180") (name "QSPI_SD3") (class "Default")
      (node (ref "IC15") (pin "51") (pinfunction "QSPI_SD3_51") (pintype "bidirectional"))
      (node (ref "IC18") (pin "7") (pinfunction "~{HOLD}/IO3_7") (pintype "bidirectional"))
    )
    (net (code "181") (name "RCT") (class "Default")
      (node (ref "C79") (pin "1") (pinfunction "1_1") (pintype "passive"))
      (node (ref "ETH1") (pin "5") (pinfunction "P5/RCT_5") (pintype "passive"))
      (node (ref "R137") (pin "1") (pinfunction "1_1") (pintype "passive"))
      (node (ref "R138") (pin "1") (pinfunction "1_1") (pintype "passive"))
    )
    (net (code "182") (name "RDC_RD_N") (class "Default")
      (node (ref "C81") (pin "1") (pinfunction "1_1") (pintype "passive"))
      (node (ref "R136") (pin "2") (pinfunction "2_2") (pintype "passive"))
      (node (ref "R137") (pin "2") (pinfunction "2_2") (pintype "passive"))
    )
    (net (code "183") (name "RDC_RD_P") (class "Default")
      (node (ref "C82") (pin "1") (pinfunction "1_1") (pintype "passive"))
      (node (ref "R135") (pin "2") (pinfunction "2_2") (pintype "passive"))
      (node (ref "R138") (pin "2") (pinfunction "2_2") (pintype "passive"))
    )
    (net (code "184") (name "RD_N") (class "Default")
      (node (ref "C81") (pin "2") (pinfunction "2_2") (pintype "passive"))
      (node (ref "ETH1") (pin "6") (pinfunction "RD-_6") (pintype "passive"))
    )
    (net (code "185") (name "RD_P") (class "Default")
      (node (ref "C82") (pin "2") (pinfunction "2_2") (pintype "passive"))
      (node (ref "ETH1") (pin "4") (pinfunction "RD+_4") (pintype "passive"))
    )
    (net (code "186") (name "RELAY_1") (class "Default")
      (node (ref "D1") (pin "A") (pinfunction "A_A") (pintype "passive"))
      (node (ref "K1") (pin "1") (pinfunction "1_1") (pintype "passive"))
      (node (ref "R24") (pin "2") (pinfunction "2_2") (pintype "passive"))
    )
    (net (code "187") (name "RELAY_2") (class "Default")
      (node (ref "D2") (pin "A") (pinfunction "A_A") (pintype "passive"))
      (node (ref "K2") (pin "1") (pinfunction "1_1") (pintype "passive"))
      (node (ref "R23") (pin "2") (pinfunction "2_2") (pintype "passive"))
    )
    (net (code "188") (name "RELAY_3") (class "Default")
      (node (ref "D3") (pin "A") (pinfunction "A_A") (pintype "passive"))
      (node (ref "K3") (pin "1") (pinfunction "1_1") (pintype "passive"))
      (node (ref "R22") (pin "2") (pinfunction "2_2") (pintype "passive"))
    )
    (net (code "189") (name "RELAY_4") (class "Default")
      (node (ref "D4") (pin "A") (pinfunction "A_A") (pintype "passive"))
      (node (ref "K4") (pin "1") (pinfunction "1_1") (pintype "passive"))
      (node (ref "R21") (pin "2") (pinfunction "2_2") (pintype "passive"))
    )
    (net (code "190") (name "RELAY_5") (class "Default")
      (node (ref "D5") (pin "A") (pinfunction "A_A") (pintype "passive"))
      (node (ref "K5") (pin "1") (pinfunction "1_1") (pintype "passive"))
      (node (ref "R20") (pin "2") (pinfunction "2_2") (pintype "passive"))
    )
    (net (code "191") (name "RELAY_6") (class "Default")
      (node (ref "D6") (pin "A") (pinfunction "A_A") (pintype "passive"))
      (node (ref "K6") (pin "1") (pinfunction "1_1") (pintype "passive"))
      (node (ref "R19") (pin "2") (pinfunction "2_2") (pintype "passive"))
    )
    (net (code "192") (name "RELAY_7") (class "Default")
      (node (ref "D7") (pin "A") (pinfunction "A_A") (pintype "passive"))
      (node (ref "K7") (pin "1") (pinfunction "1_1") (pintype "passive"))
      (node (ref "R18") (pin "2") (pinfunction "2_2") (pintype "passive"))
    )
    (net (code "193") (name "RELAY_8") (class "Default")
      (node (ref "D8") (pin "A") (pinfunction "A_A") (pintype "passive"))
      (node (ref "K8") (pin "1") (pinfunction "1_1") (pintype "passive"))
      (node (ref "R17") (pin "2") (pinfunction "2_2") (pintype "passive"))
    )
    (net (code "194") (name "REL_0") (class "Default")
      (node (ref "IC3") (pin "8") (pinfunction "8B_8") (pintype "bidirectional"))
      (node (ref "IC4") (pin "17") (pinfunction "IO1.0_17") (pintype "bidirectional"))
      (node (ref "REL0") (pin "TP") (pinfunction "P$1_TP") (pintype "bidirectional"))
      (node (ref "RN1") (pin "A2") (pinfunction "2_A2") (pintype "passive"))
    )
    (net (code "195") (name "REL_1") (class "Default")
      (node (ref "IC3") (pin "7") (pinfunction "7B_7") (pintype "bidirectional"))
      (node (ref "IC4") (pin "18") (pinfunction "IO1.1_18") (pintype "bidirectional"))
      (node (ref "REL1") (pin "TP") (pinfunction "P$1_TP") (pintype "bidirectional"))
      (node (ref "RN1") (pin "B2") (pinfunction "2_B2") (pintype "passive"))
    )
    (net (code "196") (name "REL_2") (class "Default")
      (node (ref "IC3") (pin "6") (pinfunction "6B_6") (pintype "bidirectional"))
      (node (ref "IC4") (pin "19") (pinfunction "IO1.2_19") (pintype "bidirectional"))
      (node (ref "REL2") (pin "TP") (pinfunction "P$1_TP") (pintype "bidirectional"))
      (node (ref "RN1") (pin "C2") (pinfunction "2_C2") (pintype "passive"))
    )
    (net (code "197") (name "REL_3") (class "Default")
      (node (ref "IC3") (pin "5") (pinfunction "5B_5") (pintype "bidirectional"))
      (node (ref "IC4") (pin "20") (pinfunction "IO1.3_20") (pintype "bidirectional"))
      (node (ref "REL3") (pin "TP") (pinfunction "P$1_TP") (pintype "bidirectional"))
      (node (ref "RN1") (pin "D2") (pinfunction "2_D2") (pintype "passive"))
    )
    (net (code "198") (name "REL_4") (class "Default")
      (node (ref "IC3") (pin "4") (pinfunction "4B_4") (pintype "bidirectional"))
      (node (ref "IC4") (pin "21") (pinfunction "IO1.4_21") (pintype "bidirectional"))
      (node (ref "REL4") (pin "TP") (pinfunction "P$1_TP") (pintype "bidirectional"))
      (node (ref "RN2") (pin "A2") (pinfunction "2_A2") (pintype "passive"))
    )
    (net (code "199") (name "REL_5") (class "Default")
      (node (ref "IC3") (pin "3") (pinfunction "3B_3") (pintype "bidirectional"))
      (node (ref "IC4") (pin "22") (pinfunction "IO1.5_22") (pintype "bidirectional"))
      (node (ref "REL5") (pin "TP") (pinfunction "P$1_TP") (pintype "bidirectional"))
      (node (ref "RN2") (pin "B2") (pinfunction "2_B2") (pintype "passive"))
    )
    (net (code "200") (name "REL_6") (class "Default")
      (node (ref "IC3") (pin "2") (pinfunction "2B_2") (pintype "bidirectional"))
      (node (ref "IC4") (pin "23") (pinfunction "IO1.6_23") (pintype "bidirectional"))
      (node (ref "REL6") (pin "TP") (pinfunction "P$1_TP") (pintype "bidirectional"))
      (node (ref "RN2") (pin "C2") (pinfunction "2_C2") (pintype "passive"))
    )
    (net (code "201") (name "REL_7") (class "Default")
      (node (ref "IC3") (pin "1") (pinfunction "1B_1") (pintype "bidirectional"))
      (node (ref "IC4") (pin "24") (pinfunction "IO1.7_24") (pintype "bidirectional"))
      (node (ref "REL7") (pin "TP") (pinfunction "P$1_TP") (pintype "bidirectional"))
      (node (ref "RN2") (pin "D2") (pinfunction "2_D2") (pintype "passive"))
    )
    (net (code "202") (name "RP_XI") (class "Default")
      (node (ref "C58") (pin "1") (pinfunction "1_1") (pintype "passive"))
      (node (ref "IC15") (pin "20") (pinfunction "XIN_20") (pintype "bidirectional"))
      (node (ref "X1") (pin "1") (pinfunction "1_1") (pintype "passive"))
    )
    (net (code "203") (name "RP_XO") (class "Default")
      (node (ref "IC15") (pin "21") (pinfunction "XOUT_21") (pintype "bidirectional"))
      (node (ref "R16") (pin "2") (pinfunction "2_2") (pintype "passive"))
    )
    (net (code "204") (name "RUN") (class "Default")
      (node (ref "GDGC") (pin "2") (pinfunction "P$2_2") (pintype "bidirectional"))
      (node (ref "IC15") (pin "26") (pinfunction "RUN_26") (pintype "bidirectional"))
      (node (ref "R132") (pin "2") (pinfunction "2_2") (pintype "passive"))
      (node (ref "RESET") (pin "2") (pinfunction "P$2_2") (pintype "bidirectional"))
    )
    (net (code "205") (name "RX_RD_N") (class "Default")
      (node (ref "IC20") (pin "5") (pinfunction "RXN_5") (pintype "input"))
      (node (ref "R136") (pin "1") (pinfunction "1_1") (pintype "passive"))
    )
    (net (code "206") (name "RX_RD_P") (class "Default")
      (node (ref "IC20") (pin "6") (pinfunction "RXP_6") (pintype "input"))
      (node (ref "R135") (pin "1") (pinfunction "1_1") (pintype "passive"))
    )
    (net (code "207") (name "SH") (class "Default")
      (node (ref "C78") (pin "1") (pinfunction "1_1") (pintype "passive"))
      (node (ref "C83") (pin "2") (pinfunction "2_2") (pintype "passive"))
      (node (ref "ETH1") (pin "13") (pinfunction "SHIELD_13") (pintype "passive"))
      (node (ref "ETH1") (pin "14") (pinfunction "SHIELD_14") (pintype "passive"))
      (node (ref "R110") (pin "2") (pinfunction "2_2") (pintype "passive"))
      (node (ref "R131") (pin "1") (pinfunction "1_1") (pintype "passive"))
      (node (ref "USB1") (pin "SHLD1") (pinfunction "SHILED_SHLD1") (pintype "power_in"))
      (node (ref "USB1") (pin "SHLD2") (pinfunction "SHILED_SHLD2") (pintype "power_in"))
      (node (ref "USB1") (pin "SHLD3") (pinfunction "SHILED_SHLD3") (pintype "power_in"))
      (node (ref "USB1") (pin "SHLD4") (pinfunction "SHILED_SHLD4") (pintype "power_in"))
    )
    (net (code "208") (name "SRC1") (class "Default")
      (node (ref "C21") (pin "1") (pinfunction "1_1") (pintype "passive"))
      (node (ref "C22") (pin "1") (pinfunction "1_1") (pintype "passive"))
      (node (ref "C5") (pin "1") (pinfunction "1_1") (pintype "passive"))
      (node (ref "D11") (pin "C") (pinfunction "C_C") (pintype "passive"))
      (node (ref "IC13") (pin "3") (pinfunction "SRC2_3") (pintype "output"))
      (node (ref "IC13") (pin "4") (pinfunction "SRC_4") (pintype "output"))
      (node (ref "L3") (pin "1") (pinfunction "1_1") (pintype "passive"))
      (node (ref "R60") (pin "2") (pinfunction "2_2") (pintype "passive"))
    )
    (net (code "209") (name "SRC2") (class "Default")
      (node (ref "C46") (pin "1") (pinfunction "1_1") (pintype "passive"))
      (node (ref "C51") (pin "1") (pinfunction "1_1") (pintype "passive"))
      (node (ref "C52") (pin "1") (pinfunction "1_1") (pintype "passive"))
      (node (ref "D14") (pin "C") (pinfunction "C_C") (pintype "passive"))
      (node (ref "IC5") (pin "3") (pinfunction "SRC2_3") (pintype "output"))
      (node (ref "IC5") (pin "4") (pinfunction "SRC_4") (pintype "output"))
      (node (ref "L5") (pin "1") (pinfunction "1_1") (pintype "passive"))
      (node (ref "R107") (pin "2") (pinfunction "2_2") (pintype "passive"))
    )
    (net (code "210") (name "SWCLK") (class "Default")
      (node (ref "GDGC") (pin "1") (pinfunction "P$1_1") (pintype "bidirectional"))
      (node (ref "IC15") (pin "24") (pinfunction "SWCLK_24") (pintype "bidirectional"))
    )
    (net (code "211") (name "SWDIO") (class "Default")
      (node (ref "GDGC") (pin "3") (pinfunction "P$3_3") (pintype "bidirectional"))
      (node (ref "IC15") (pin "25") (pinfunction "SWDIO_25") (pintype "bidirectional"))
    )
    (net (code "212") (name "TCT") (class "Default")
      (node (ref "C80") (pin "1") (pinfunction "1_1") (pintype "passive"))
      (node (ref "ETH1") (pin "2") (pinfunction "P4/TCT_2") (pintype "passive"))
      (node (ref "R146") (pin "1") (pinfunction "1_1") (pintype "passive"))
    )
    (net (code "213") (name "TD_N") (class "Default")
      (node (ref "ETH1") (pin "3") (pinfunction "TD-_3") (pintype "passive"))
      (node (ref "R134") (pin "2") (pinfunction "2_2") (pintype "passive"))
      (node (ref "R140") (pin "1") (pinfunction "1_1") (pintype "passive"))
    )
    (net (code "214") (name "TD_P") (class "Default")
      (node (ref "ETH1") (pin "1") (pinfunction "TD+_1") (pintype "passive"))
      (node (ref "R133") (pin "2") (pinfunction "2_2") (pintype "passive"))
      (node (ref "R139") (pin "1") (pinfunction "1_1") (pintype "passive"))
    )
    (net (code "215") (name "TX_CH1") (class "Default")
      (node (ref "IC6") (pin "6") (pinfunction "TX_6") (pintype "bidirectional"))
      (node (ref "R155") (pin "1") (pinfunction "1_1") (pintype "passive"))
    )
    (net (code "216") (name "TX_CH2") (class "Default")
      (node (ref "IC8") (pin "6") (pinfunction "TX_6") (pintype "bidirectional"))
      (node (ref "R154") (pin "1") (pinfunction "1_1") (pintype "passive"))
    )
    (net (code "217") (name "TX_CH3") (class "Default")
      (node (ref "IC10") (pin "6") (pinfunction "TX_6") (pintype "bidirectional"))
      (node (ref "R153") (pin "1") (pinfunction "1_1") (pintype "passive"))
    )
    (net (code "218") (name "TX_CH4") (class "Default")
      (node (ref "IC12") (pin "6") (pinfunction "TX_6") (pintype "bidirectional"))
      (node (ref "R59") (pin "1") (pinfunction "1_1") (pintype "passive"))
    )
    (net (code "219") (name "TX_CH5") (class "Default")
      (node (ref "IC7") (pin "6") (pinfunction "TX_6") (pintype "bidirectional"))
      (node (ref "R159") (pin "1") (pinfunction "1_1") (pintype "passive"))
    )
    (net (code "220") (name "TX_CH6") (class "Default")
      (node (ref "IC11") (pin "6") (pinfunction "TX_6") (pintype "bidirectional"))
      (node (ref "R158") (pin "1") (pinfunction "1_1") (pintype "passive"))
    )
    (net (code "221") (name "TX_CH7") (class "Default")
      (node (ref "IC14") (pin "6") (pinfunction "TX_6") (pintype "bidirectional"))
      (node (ref "R157") (pin "1") (pinfunction "1_1") (pintype "passive"))
    )
    (net (code "222") (name "TX_CH8") (class "Default")
      (node (ref "IC16") (pin "6") (pinfunction "TX_6") (pintype "bidirectional"))
      (node (ref "R156") (pin "1") (pinfunction "1_1") (pintype "passive"))
    )
    (net (code "223") (name "TX_MUX1") (class "Default")
      (node (ref "IC9") (pin "4") (pinfunction "D0_4") (pintype "bidirectional"))
      (node (ref "OPT1") (pin "10") (pinfunction "10_10") (pintype "passive"))
      (node (ref "R89") (pin "D1") (pinfunction "4_D1") (pintype "passive"))
    )
    (net (code "224") (name "TX_MUX2") (class "Default")
      (node (ref "IC9") (pin "3") (pinfunction "D1_3") (pintype "bidirectional"))
      (node (ref "OPT1") (pin "12") (pinfunction "12_12") (pintype "passive"))
      (node (ref "R89") (pin "C1") (pinfunction "3_C1") (pintype "passive"))
    )
    (net (code "225") (name "TX_MUX3") (class "Default")
      (node (ref "IC9") (pin "2") (pinfunction "D2_2") (pintype "bidirectional"))
      (node (ref "OPT1") (pin "14") (pinfunction "14_14") (pintype "passive"))
      (node (ref "R89") (pin "B1") (pinfunction "2_B1") (pintype "passive"))
    )
    (net (code "226") (name "TX_MUX4") (class "Default")
      (node (ref "IC9") (pin "1") (pinfunction "D3_1") (pintype "bidirectional"))
      (node (ref "OPT1") (pin "16") (pinfunction "16_16") (pintype "passive"))
      (node (ref "R89") (pin "A1") (pinfunction "1_A1") (pintype "passive"))
    )
    (net (code "227") (name "TX_MUX5") (class "Default")
      (node (ref "IC9") (pin "15") (pinfunction "D4_15") (pintype "bidirectional"))
      (node (ref "OPT2") (pin "10") (pinfunction "10_10") (pintype "passive"))
      (node (ref "R90") (pin "A1") (pinfunction "1_A1") (pintype "passive"))
    )
    (net (code "228") (name "TX_MUX6") (class "Default")
      (node (ref "IC9") (pin "14") (pinfunction "D5_14") (pintype "bidirectional"))
      (node (ref "OPT2") (pin "12") (pinfunction "12_12") (pintype "passive"))
      (node (ref "R90") (pin "B1") (pinfunction "2_B1") (pintype "passive"))
    )
    (net (code "229") (name "TX_MUX7") (class "Default")
      (node (ref "IC9") (pin "13") (pinfunction "D6_13") (pintype "bidirectional"))
      (node (ref "OPT2") (pin "14") (pinfunction "14_14") (pintype "passive"))
      (node (ref "R90") (pin "C1") (pinfunction "3_C1") (pintype "passive"))
    )
    (net (code "230") (name "TX_MUX8") (class "Default")
      (node (ref "IC9") (pin "12") (pinfunction "D7_12") (pintype "bidirectional"))
      (node (ref "OPT2") (pin "16") (pinfunction "16_16") (pintype "passive"))
      (node (ref "R90") (pin "D1") (pinfunction "4_D1") (pintype "passive"))
    )
    (net (code "231") (name "TX_OUT") (class "Default")
      (node (ref "IC9") (pin "5") (pinfunction "Y_5") (pintype "bidirectional"))
      (node (ref "R91") (pin "1") (pinfunction "1_1") (pintype "passive"))
    )
    (net (code "232") (name "TX_TD_N") (class "Default")
      (node (ref "IC20") (pin "1") (pinfunction "TXN_1") (pintype "output"))
      (node (ref "R134") (pin "1") (pinfunction "1_1") (pintype "passive"))
    )
    (net (code "233") (name "TX_TD_P") (class "Default")
      (node (ref "IC20") (pin "2") (pinfunction "TXP_2") (pintype "output"))
      (node (ref "R133") (pin "1") (pinfunction "1_1") (pintype "passive"))
    )
    (net (code "234") (name "UART0_RX") (class "Default")
      (node (ref "IC15") (pin "2") (pinfunction "GPIO0_2") (pintype "bidirectional"))
      (node (ref "R58") (pin "2") (pinfunction "2_2") (pintype "passive"))
      (node (ref "RGTG") (pin "1") (pinfunction "P$1_1") (pintype "bidirectional"))
      (node (ref "RX0") (pin "TP") (pinfunction "P$1_TP") (pintype "bidirectional"))
    )
    (net (code "235") (name "UART0_TX") (class "Default")
      (node (ref "IC15") (pin "3") (pinfunction "GPIO1_3") (pintype "bidirectional"))
      (node (ref "R57") (pin "2") (pinfunction "2_2") (pintype "passive"))
      (node (ref "RGTG") (pin "3") (pinfunction "P$3_3") (pintype "bidirectional"))
      (node (ref "RX1") (pin "TP") (pinfunction "P$1_TP") (pintype "bidirectional"))
    )
    (net (code "236") (name "USB2_DP_N") (class "Default")
      (node (ref "ESD1") (pin "3") (pinfunction "C2_3") (pintype "bidirectional"))
      (node (ref "R15") (pin "1") (pinfunction "1_1") (pintype "passive"))
      (node (ref "USB1") (pin "A7") (pinfunction "D-_A7") (pintype "bidirectional"))
      (node (ref "USB1") (pin "B7") (pinfunction "D-_B7") (pintype "bidirectional"))
    )
    (net (code "237") (name "USB2_DP_P") (class "Default")
      (node (ref "ESD1") (pin "2") (pinfunction "C1_2") (pintype "bidirectional"))
      (node (ref "R160") (pin "1") (pinfunction "1_1") (pintype "passive"))
      (node (ref "USB1") (pin "A6") (pinfunction "D+_A6") (pintype "bidirectional"))
      (node (ref "USB1") (pin "B6") (pinfunction "D+_B6") (pintype "bidirectional"))
    )
    (net (code "238") (name "USB_BOOT") (class "Default")
      (node (ref "BOOT") (pin "1") (pinfunction "P$1_1") (pintype "bidirectional"))
      (node (ref "R112") (pin "1") (pinfunction "1_1") (pintype "passive"))
    )
    (net (code "239") (name "VBUS") (class "Default")
      (node (ref "C65") (pin "1") (pinfunction "1_1") (pintype "passive"))
      (node (ref "C66") (pin "1") (pinfunction "1_1") (pintype "passive"))
      (node (ref "C97") (pin "1") (pinfunction "1_1") (pintype "passive"))
      (node (ref "C98") (pin "1") (pinfunction "1_1") (pintype "passive"))
      (node (ref "D15") (pin "C") (pinfunction "C_C") (pintype "passive"))
      (node (ref "ESD1") (pin "4") (pinfunction "C3_4") (pintype "bidirectional"))
      (node (ref "IC21") (pin "1") (pinfunction "VIN_1") (pintype "bidirectional"))
      (node (ref "IC21") (pin "3") (pinfunction "EN_3") (pintype "bidirectional"))
      (node (ref "R121") (pin "1") (pinfunction "1_1") (pintype "passive"))
      (node (ref "R126") (pin "1") (pinfunction "1_1") (pintype "passive"))
      (node (ref "USB1") (pin "VBUS1") (pinfunction "VBUS_VBUS1") (pintype "power_in"))
      (node (ref "USB1") (pin "VBUS2") (pinfunction "VBUS_VBUS2") (pintype "power_in"))
      (node (ref "VBUS") (pin "TP") (pinfunction "P$1_TP") (pintype "bidirectional"))
    )
    (net (code "240") (name "VNI1") (class "Default")
      (node (ref "C21") (pin "2") (pinfunction "2_2") (pintype "passive"))
      (node (ref "IC13") (pin "1") (pinfunction "VCC_1") (pintype "output"))
      (node (ref "VNI1") (pin "TP") (pinfunction "P$1_TP") (pintype "bidirectional"))
    )
    (net (code "241") (name "VNI2") (class "Default")
      (node (ref "C46") (pin "2") (pinfunction "2_2") (pintype "passive"))
      (node (ref "IC5") (pin "1") (pinfunction "VCC_1") (pintype "output"))
      (node (ref "VNI2") (pin "TP") (pinfunction "P$1_TP") (pintype "bidirectional"))
    )
    (net (code "242") (name "W5500_MISO") (class "Default")
      (node (ref "IC15") (pin "27") (pinfunction "GPIO16_27") (pintype "bidirectional"))
      (node (ref "IC20") (pin "34") (pinfunction "MISO_34") (pintype "output"))
      (node (ref "MISO1") (pin "TP") (pinfunction "P$1_TP") (pintype "bidirectional"))
    )
    (net (code "243") (name "W5500_MOSI") (class "Default")
      (node (ref "IC15") (pin "30") (pinfunction "GPIO19_30") (pintype "bidirectional"))
      (node (ref "IC20") (pin "35") (pinfunction "MOSI_35") (pintype "input"))
      (node (ref "MOSI1") (pin "TP") (pinfunction "P$1_TP") (pintype "bidirectional"))
    )
    (net (code "244") (name "W5500_SCK") (class "Default")
      (node (ref "IC15") (pin "29") (pinfunction "GPIO18_29") (pintype "bidirectional"))
      (node (ref "IC20") (pin "33") (pinfunction "SCLK_33") (pintype "input"))
      (node (ref "SCLK1") (pin "TP") (pinfunction "P$1_TP") (pintype "bidirectional"))
    )
    (net (code "245") (name "unconnected-(IC4-INTA-Pad16)") (class "Default")
      (node (ref "IC4") (pin "16") (pinfunction "INTA_16") (pintype "bidirectional"))
    )
    (net (code "246") (name "unconnected-(IC4-INTB-Pad15)") (class "Default")
      (node (ref "IC4") (pin "15") (pinfunction "INTB_15") (pintype "bidirectional"))
    )
    (net (code "247") (name "unconnected-(IC4-IO2.4-Pad1)") (class "Default")
      (node (ref "IC4") (pin "1") (pinfunction "IO2.4_1") (pintype "bidirectional"))
    )
    (net (code "248") (name "unconnected-(IC4-IO2.5-Pad2)") (class "Default")
      (node (ref "IC4") (pin "2") (pinfunction "IO2.5_2") (pintype "bidirectional"))
    )
    (net (code "249") (name "unconnected-(IC4-IO2.6-Pad3)") (class "Default")
      (node (ref "IC4") (pin "3") (pinfunction "IO2.6_3") (pintype "bidirectional"))
    )
    (net (code "250") (name "unconnected-(IC4-IO2.7-Pad4)") (class "Default")
      (node (ref "IC4") (pin "4") (pinfunction "IO2.7_4") (pintype "bidirectional"))
    )
    (net (code "251") (name "unconnected-(IC6-PF-Pad7)") (class "Default")
      (node (ref "IC6") (pin "7") (pinfunction "PF_7") (pintype "bidirectional"))
    )
    (net (code "252") (name "unconnected-(IC6-RX-Pad8)") (class "Default")
      (node (ref "IC6") (pin "8") (pinfunction "RX_8") (pintype "bidirectional"))
    )
    (net (code "253") (name "unconnected-(IC7-PF-Pad7)") (class "Default")
      (node (ref "IC7") (pin "7") (pinfunction "PF_7") (pintype "bidirectional"))
    )
    (net (code "254") (name "unconnected-(IC7-RX-Pad8)") (class "Default")
      (node (ref "IC7") (pin "8") (pinfunction "RX_8") (pintype "bidirectional"))
    )
    (net (code "255") (name "unconnected-(IC8-PF-Pad7)") (class "Default")
      (node (ref "IC8") (pin "7") (pinfunction "PF_7") (pintype "bidirectional"))
    )
    (net (code "256") (name "unconnected-(IC8-RX-Pad8)") (class "Default")
      (node (ref "IC8") (pin "8") (pinfunction "RX_8") (pintype "bidirectional"))
    )
    (net (code "257") (name "unconnected-(IC10-PF-Pad7)") (class "Default")
      (node (ref "IC10") (pin "7") (pinfunction "PF_7") (pintype "bidirectional"))
    )
    (net (code "258") (name "unconnected-(IC10-RX-Pad8)") (class "Default")
      (node (ref "IC10") (pin "8") (pinfunction "RX_8") (pintype "bidirectional"))
    )
    (net (code "259") (name "unconnected-(IC11-PF-Pad7)") (class "Default")
      (node (ref "IC11") (pin "7") (pinfunction "PF_7") (pintype "bidirectional"))
    )
    (net (code "260") (name "unconnected-(IC11-RX-Pad8)") (class "Default")
      (node (ref "IC11") (pin "8") (pinfunction "RX_8") (pintype "bidirectional"))
    )
    (net (code "261") (name "unconnected-(IC12-PF-Pad7)") (class "Default")
      (node (ref "IC12") (pin "7") (pinfunction "PF_7") (pintype "bidirectional"))
    )
    (net (code "262") (name "unconnected-(IC12-RX-Pad8)") (class "Default")
      (node (ref "IC12") (pin "8") (pinfunction "RX_8") (pintype "bidirectional"))
    )
    (net (code "263") (name "unconnected-(IC14-PF-Pad7)") (class "Default")
      (node (ref "IC14") (pin "7") (pinfunction "PF_7") (pintype "bidirectional"))
    )
    (net (code "264") (name "unconnected-(IC14-RX-Pad8)") (class "Default")
      (node (ref "IC14") (pin "8") (pinfunction "RX_8") (pintype "bidirectional"))
    )
    (net (code "265") (name "unconnected-(IC16-PF-Pad7)") (class "Default")
      (node (ref "IC16") (pin "7") (pinfunction "PF_7") (pintype "bidirectional"))
    )
    (net (code "266") (name "unconnected-(IC16-RX-Pad8)") (class "Default")
      (node (ref "IC16") (pin "8") (pinfunction "RX_8") (pintype "bidirectional"))
    )
    (net (code "267") (name "unconnected-(IC20-DNC-Pad7)") (class "Default")
      (node (ref "IC20") (pin "7") (pinfunction "DNC_7") (pintype "bidirectional"))
    )
    (net (code "268") (name "unconnected-(IC20-DUPLED-Pad26)") (class "Default")
      (node (ref "IC20") (pin "26") (pinfunction "DUPLED_26") (pintype "output"))
    )
    (net (code "269") (name "unconnected-(IC20-RSVD1-Pad23)") (class "Default")
      (node (ref "IC20") (pin "23") (pinfunction "RSVD1_23") (pintype "input"))
    )
    (net (code "270") (name "unconnected-(IC20-RSVD2-Pad38)") (class "Default")
      (node (ref "IC20") (pin "38") (pinfunction "RSVD2_38") (pintype "input"))
    )
    (net (code "271") (name "unconnected-(IC20-RSVD3-Pad39)") (class "Default")
      (node (ref "IC20") (pin "39") (pinfunction "RSVD3_39") (pintype "input"))
    )
    (net (code "272") (name "unconnected-(IC20-RSVD4-Pad40)") (class "Default")
      (node (ref "IC20") (pin "40") (pinfunction "RSVD4_40") (pintype "input"))
    )
    (net (code "273") (name "unconnected-(IC20-RSVD5-Pad41)") (class "Default")
      (node (ref "IC20") (pin "41") (pinfunction "RSVD5_41") (pintype "input"))
    )
    (net (code "274") (name "unconnected-(IC20-RSVD6-Pad42)") (class "Default")
      (node (ref "IC20") (pin "42") (pinfunction "RSVD6_42") (pintype "input"))
    )
    (net (code "275") (name "unconnected-(IC20-SPDLED-Pad24)") (class "Default")
      (node (ref "IC20") (pin "24") (pinfunction "SPDLED_24") (pintype "output"))
    )
    (net (code "276") (name "unconnected-(IC20-VBG-Pad18)") (class "Default")
      (node (ref "IC20") (pin "18") (pinfunction "VBG_18") (pintype "output"))
    )
    (net (code "277") (name "unconnected-(IC21-NC-Pad4)") (class "Default")
      (node (ref "IC21") (pin "4") (pinfunction "NC_4") (pintype "bidirectional"))
    )
    (net (code "278") (name "unconnected-(R149-5-PadD2)") (class "Default")
      (node (ref "R149") (pin "D2") (pinfunction "5_D2") (pintype "passive"))
    )
    (net (code "279") (name "unconnected-(USB1-SBU1-PadA8)") (class "Default")
      (node (ref "USB1") (pin "A8") (pinfunction "SBU1_A8") (pintype "bidirectional"))
    )
    (net (code "280") (name "unconnected-(USB1-SBU2-PadB8)") (class "Default")
      (node (ref "USB1") (pin "B8") (pinfunction "SBU2_B8") (pintype "bidirectional"))
    )
    (net (code "281") (name "~{ACT}") (class "Default")
      (node (ref "IC20") (pin "27") (pinfunction "ACTLED_27") (pintype "output"))
      (node (ref "R142") (pin "1") (pinfunction "1_1") (pintype "passive"))
    )
    (net (code "282") (name "~{LINK}") (class "Default")
      (node (ref "IC20") (pin "25") (pinfunction "LINKLED_25") (pintype "output"))
      (node (ref "R141") (pin "1") (pinfunction "1_1") (pintype "passive"))
    )
    (net (code "283") (name "~{QSPI_SS}") (class "Default")
      (node (ref "IC15") (pin "56") (pinfunction "QSPI_SS_N_56") (pintype "bidirectional"))
      (node (ref "IC18") (pin "1") (pinfunction "~{CS}_1") (pintype "bidirectional"))
      (node (ref "R111") (pin "1") (pinfunction "1_1") (pintype "passive"))
      (node (ref "R112") (pin "2") (pinfunction "2_2") (pintype "passive"))
    )
    (net (code "284") (name "~{TX_OUT}") (class "Default")
      (node (ref "IC22") (pin "3") (pinfunction "+IN_3") (pintype "input"))
      (node (ref "IC9") (pin "6") (pinfunction "~{Y}_6") (pintype "bidirectional"))
      (node (ref "R92") (pin "1") (pinfunction "1_1") (pintype "passive"))
    )
    (net (code "285") (name "~{W5500_CS}") (class "Default")
      (node (ref "CS1") (pin "TP") (pinfunction "P$1_TP") (pintype "bidirectional"))
      (node (ref "IC15") (pin "28") (pinfunction "GPIO17_28") (pintype "bidirectional"))
      (node (ref "IC20") (pin "32") (pinfunction "~{SCSN}_32") (pintype "input"))
    )
    (net (code "286") (name "~{W5500_INT}") (class "Default")
      (node (ref "IC15") (pin "32") (pinfunction "GPIO21_32") (pintype "bidirectional"))
      (node (ref "IC20") (pin "36") (pinfunction "~{INTN}_36") (pintype "input"))
    )
    (net (code "287") (name "~{W5500_RST}") (class "Default")
      (node (ref "IC15") (pin "31") (pinfunction "GPIO20_31") (pintype "bidirectional"))
      (node (ref "IC20") (pin "37") (pinfunction "~{RSTN}_37") (pintype "input"))
      (node (ref "R145") (pin "1") (pinfunction "1_1") (pintype "passive"))
    )
  )
)
